# BuckConverters.net
KiCad netlist of a schematic drawn in Altium Designer
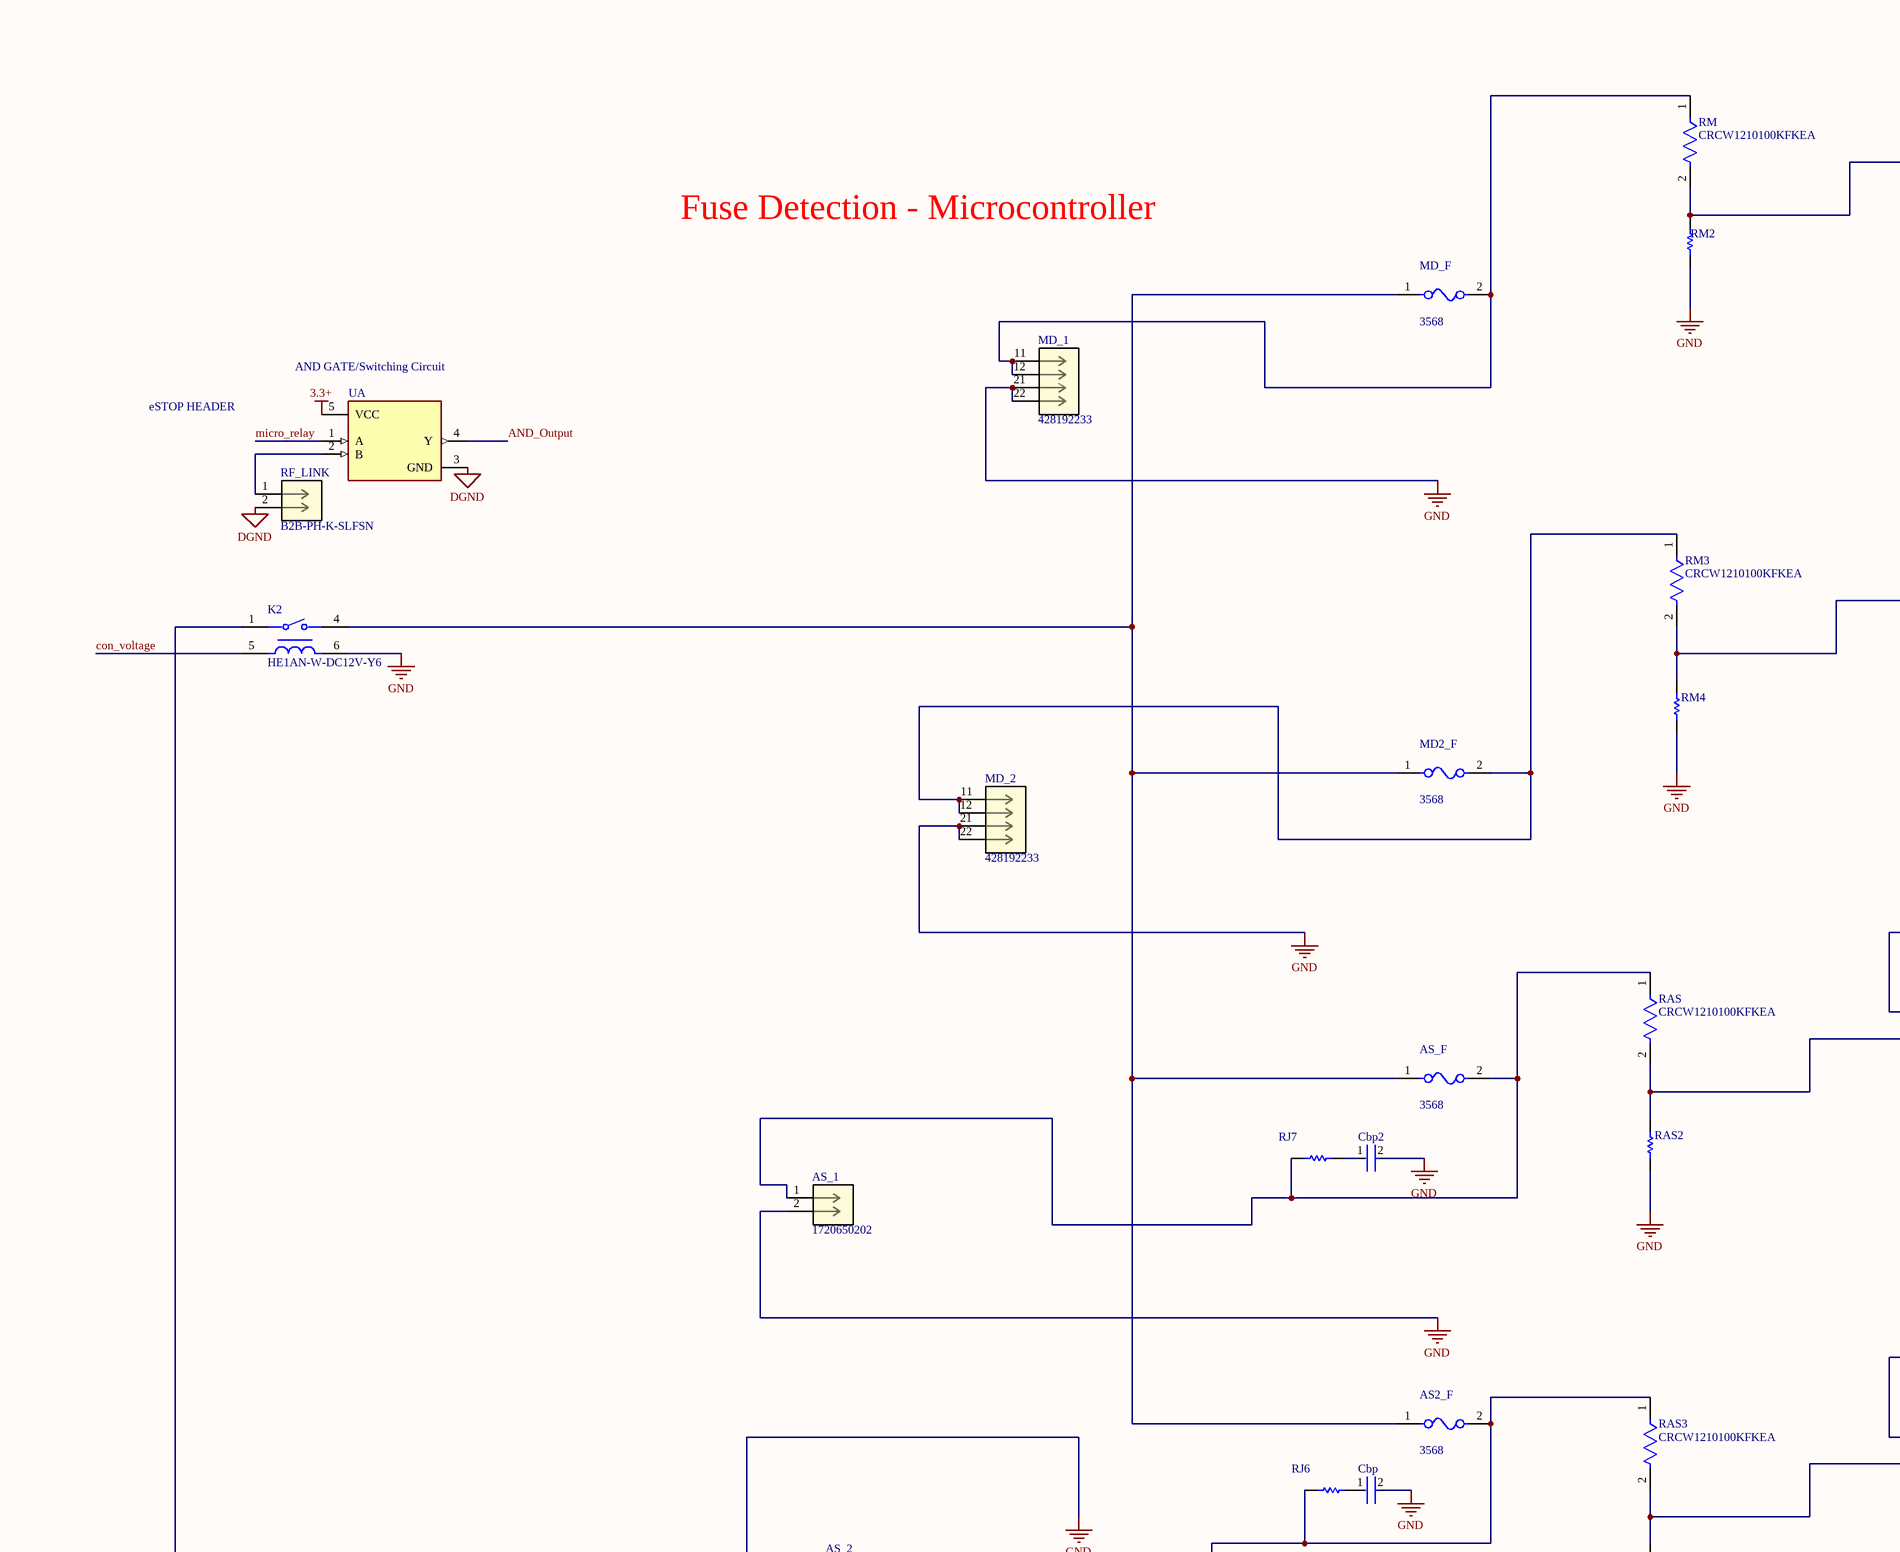
[diagram p0: BuckConverters.SchDoc, row 1 of 4 left]
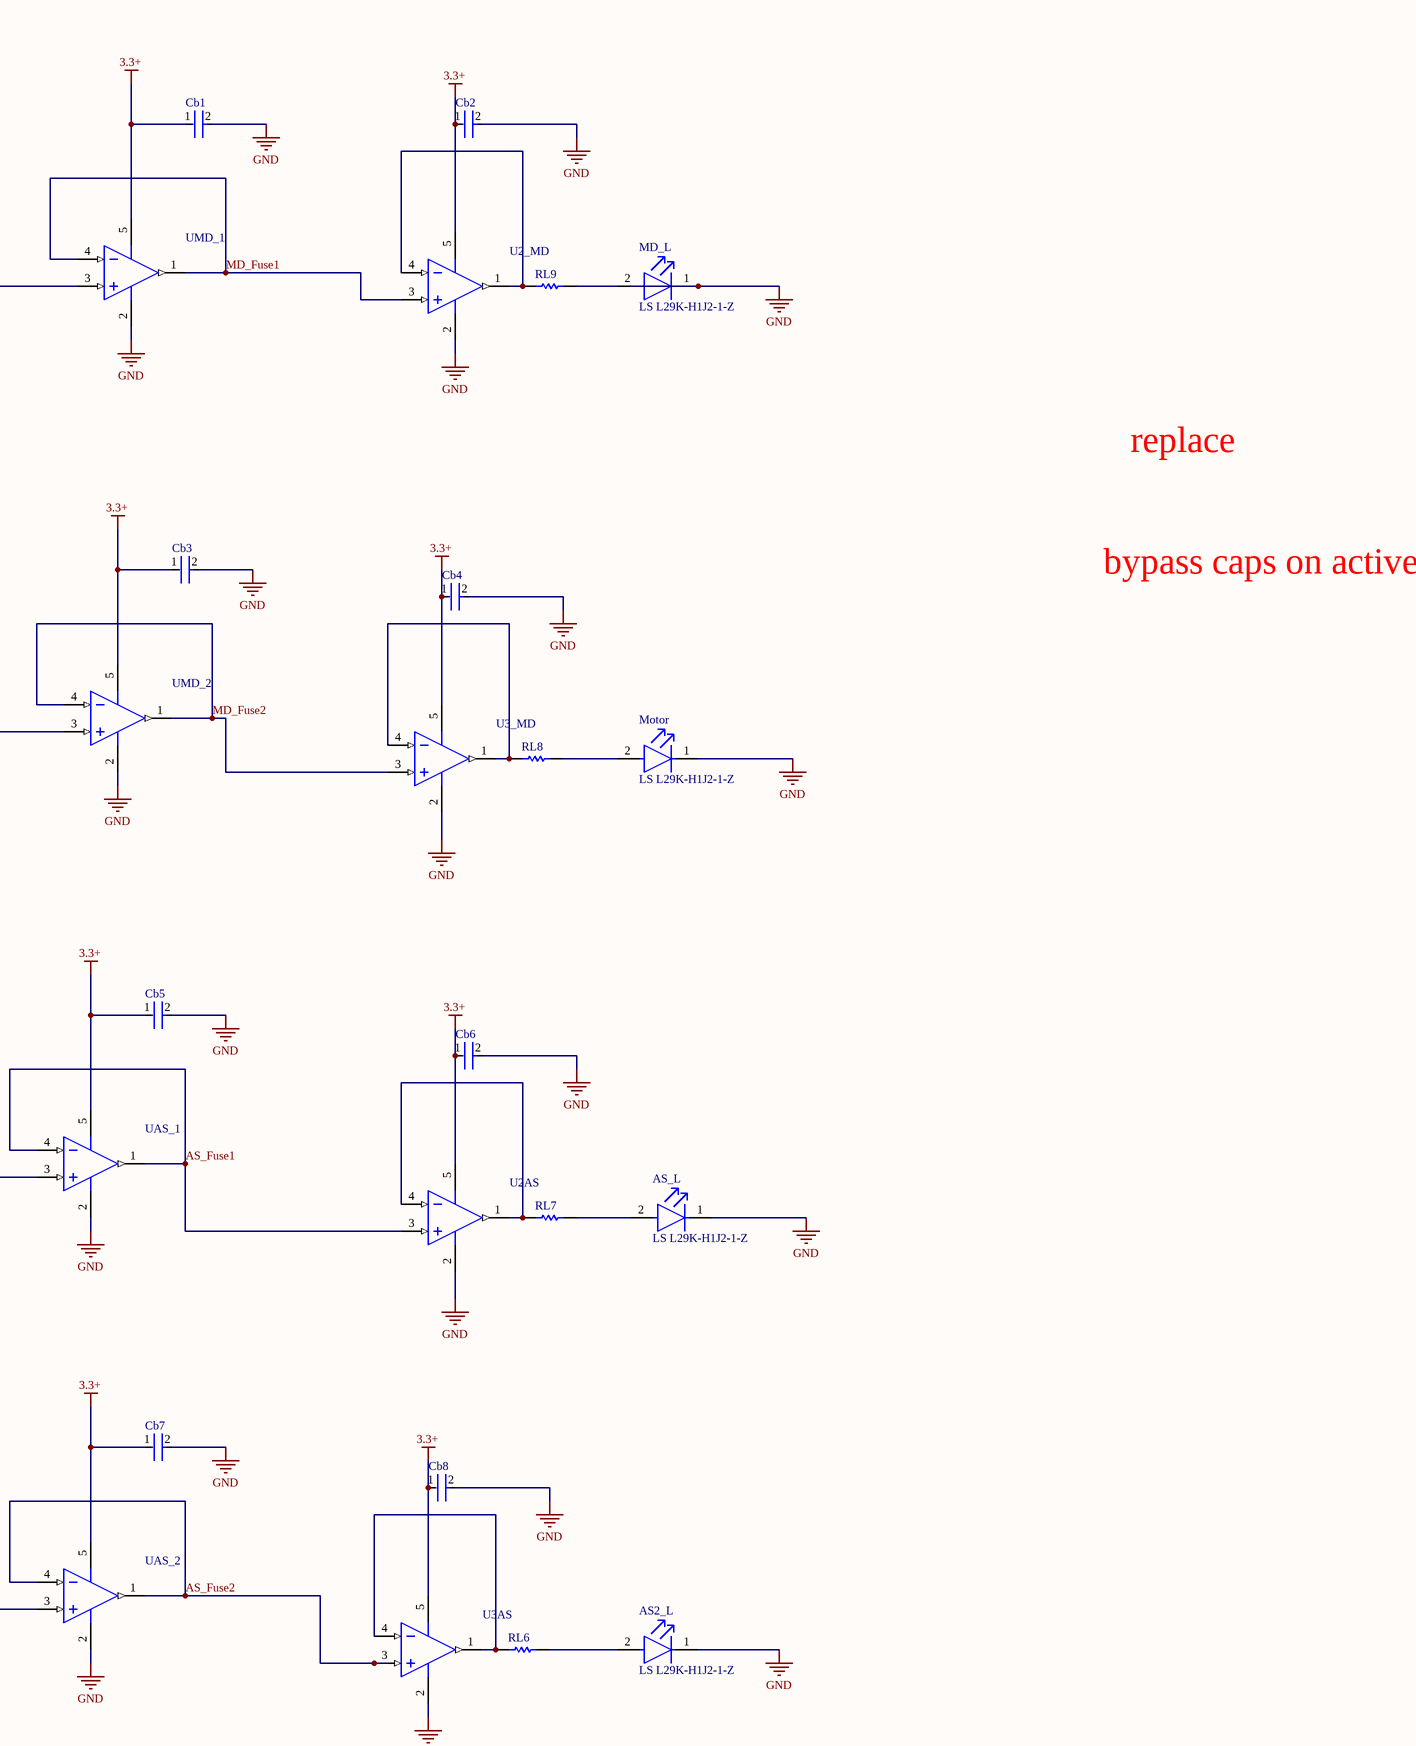
[diagram p1: BuckConverters.SchDoc, row 1 of 4 right]
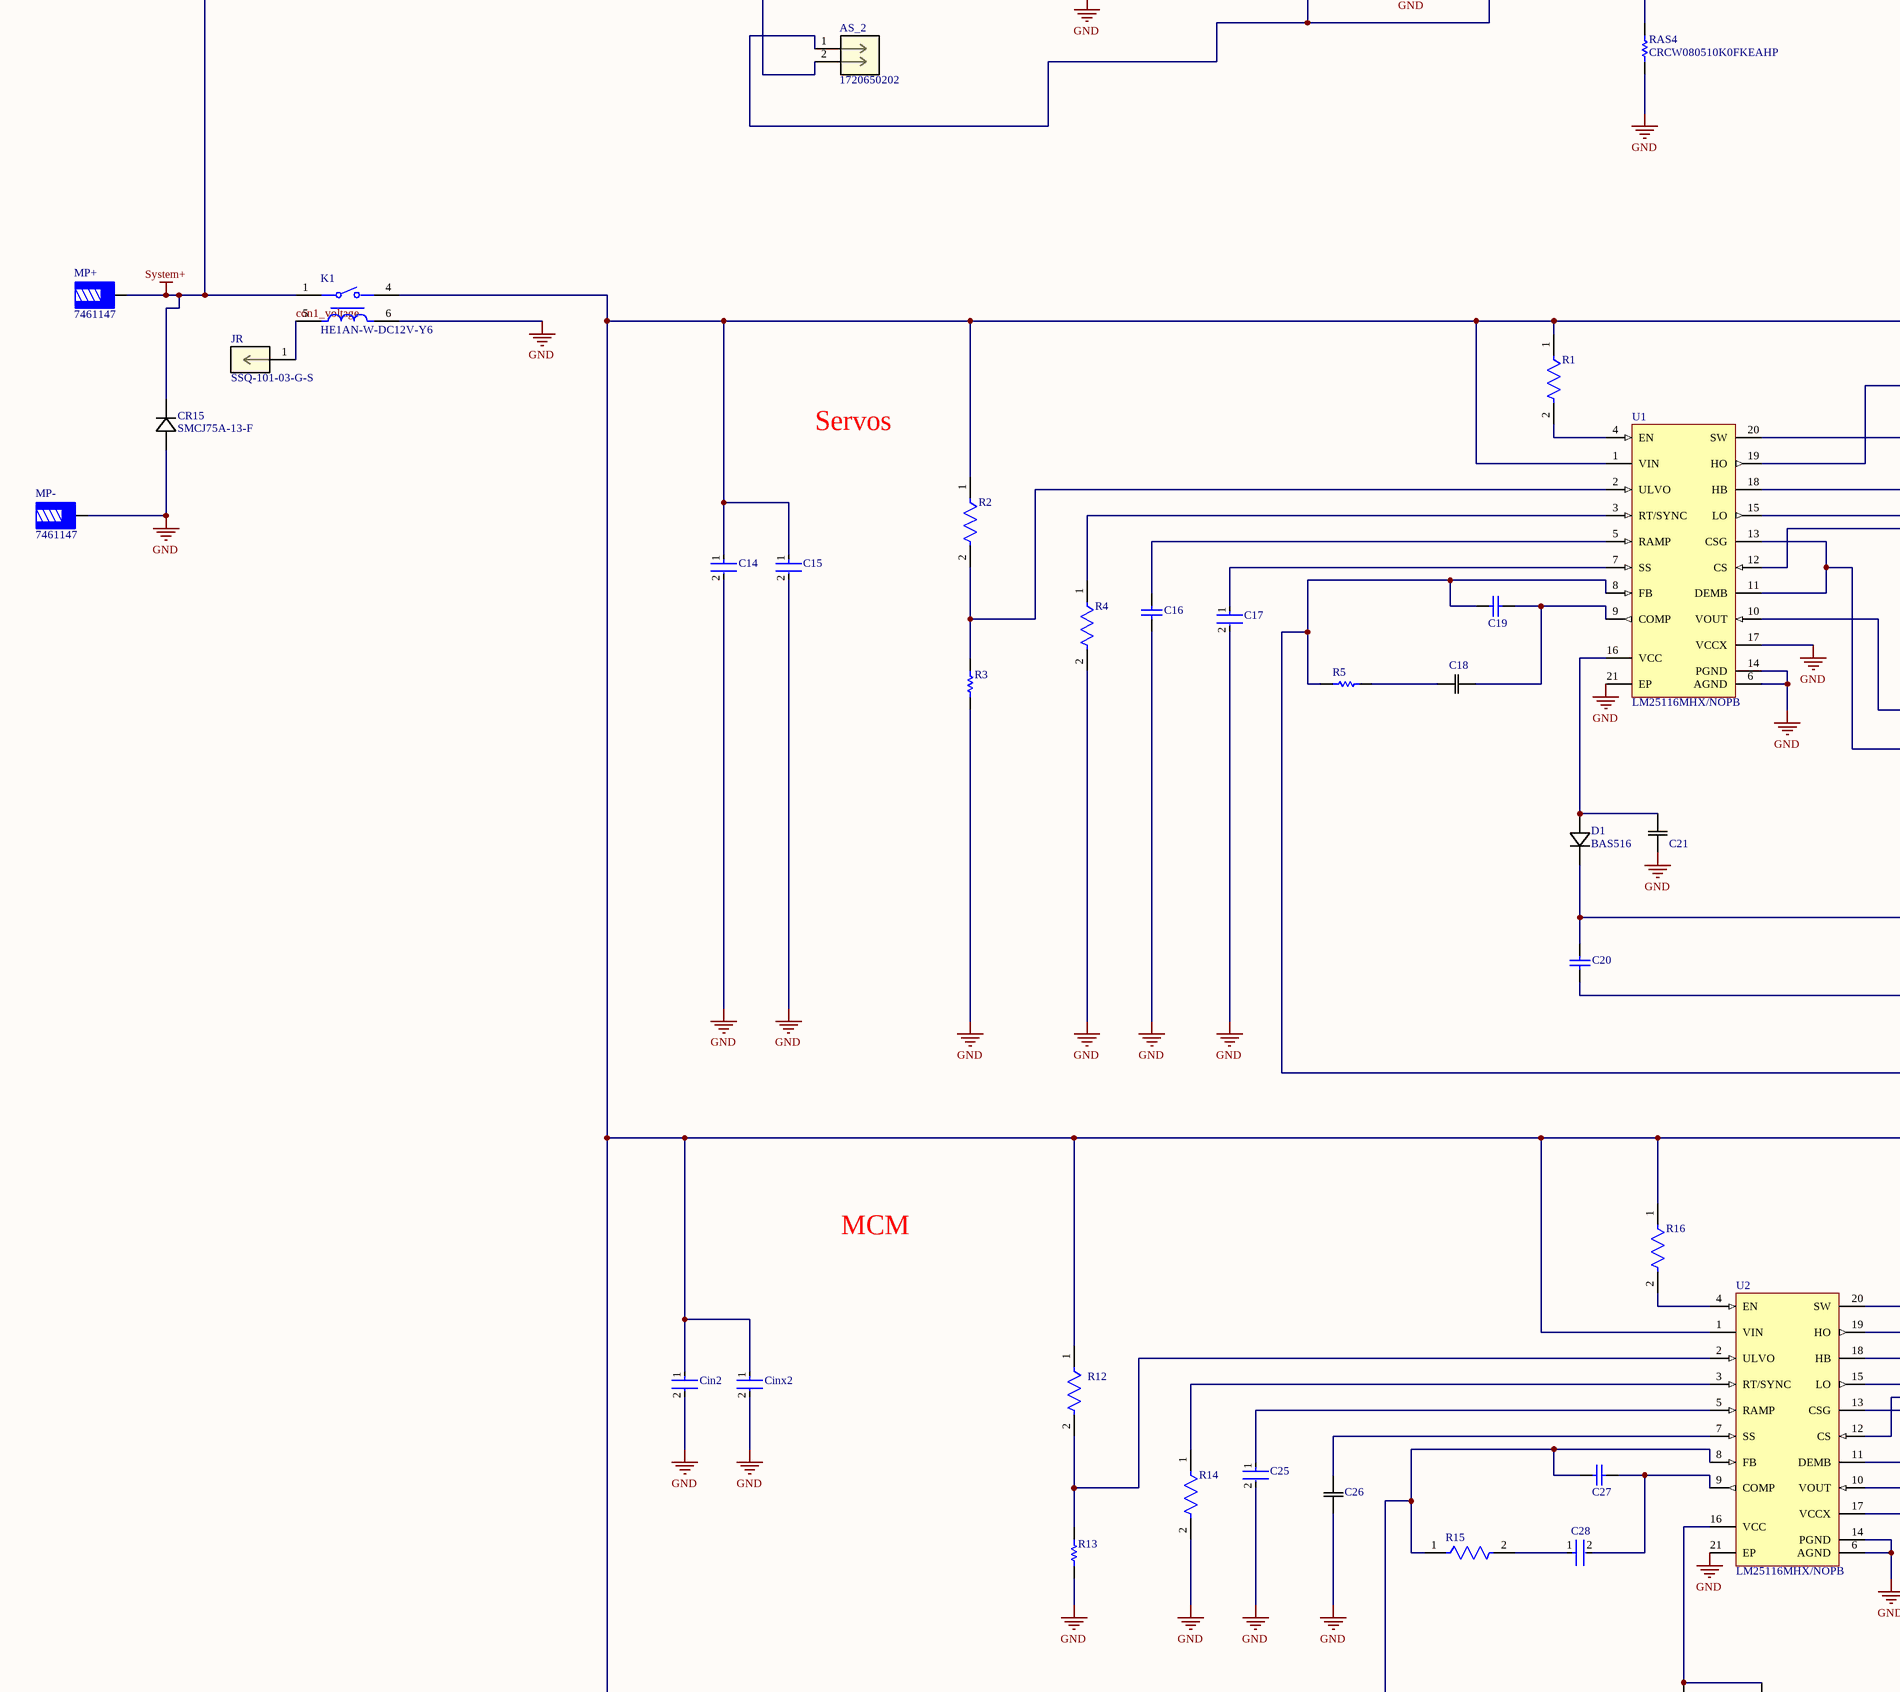
[diagram p2: BuckConverters.SchDoc, row 2 of 4 left]
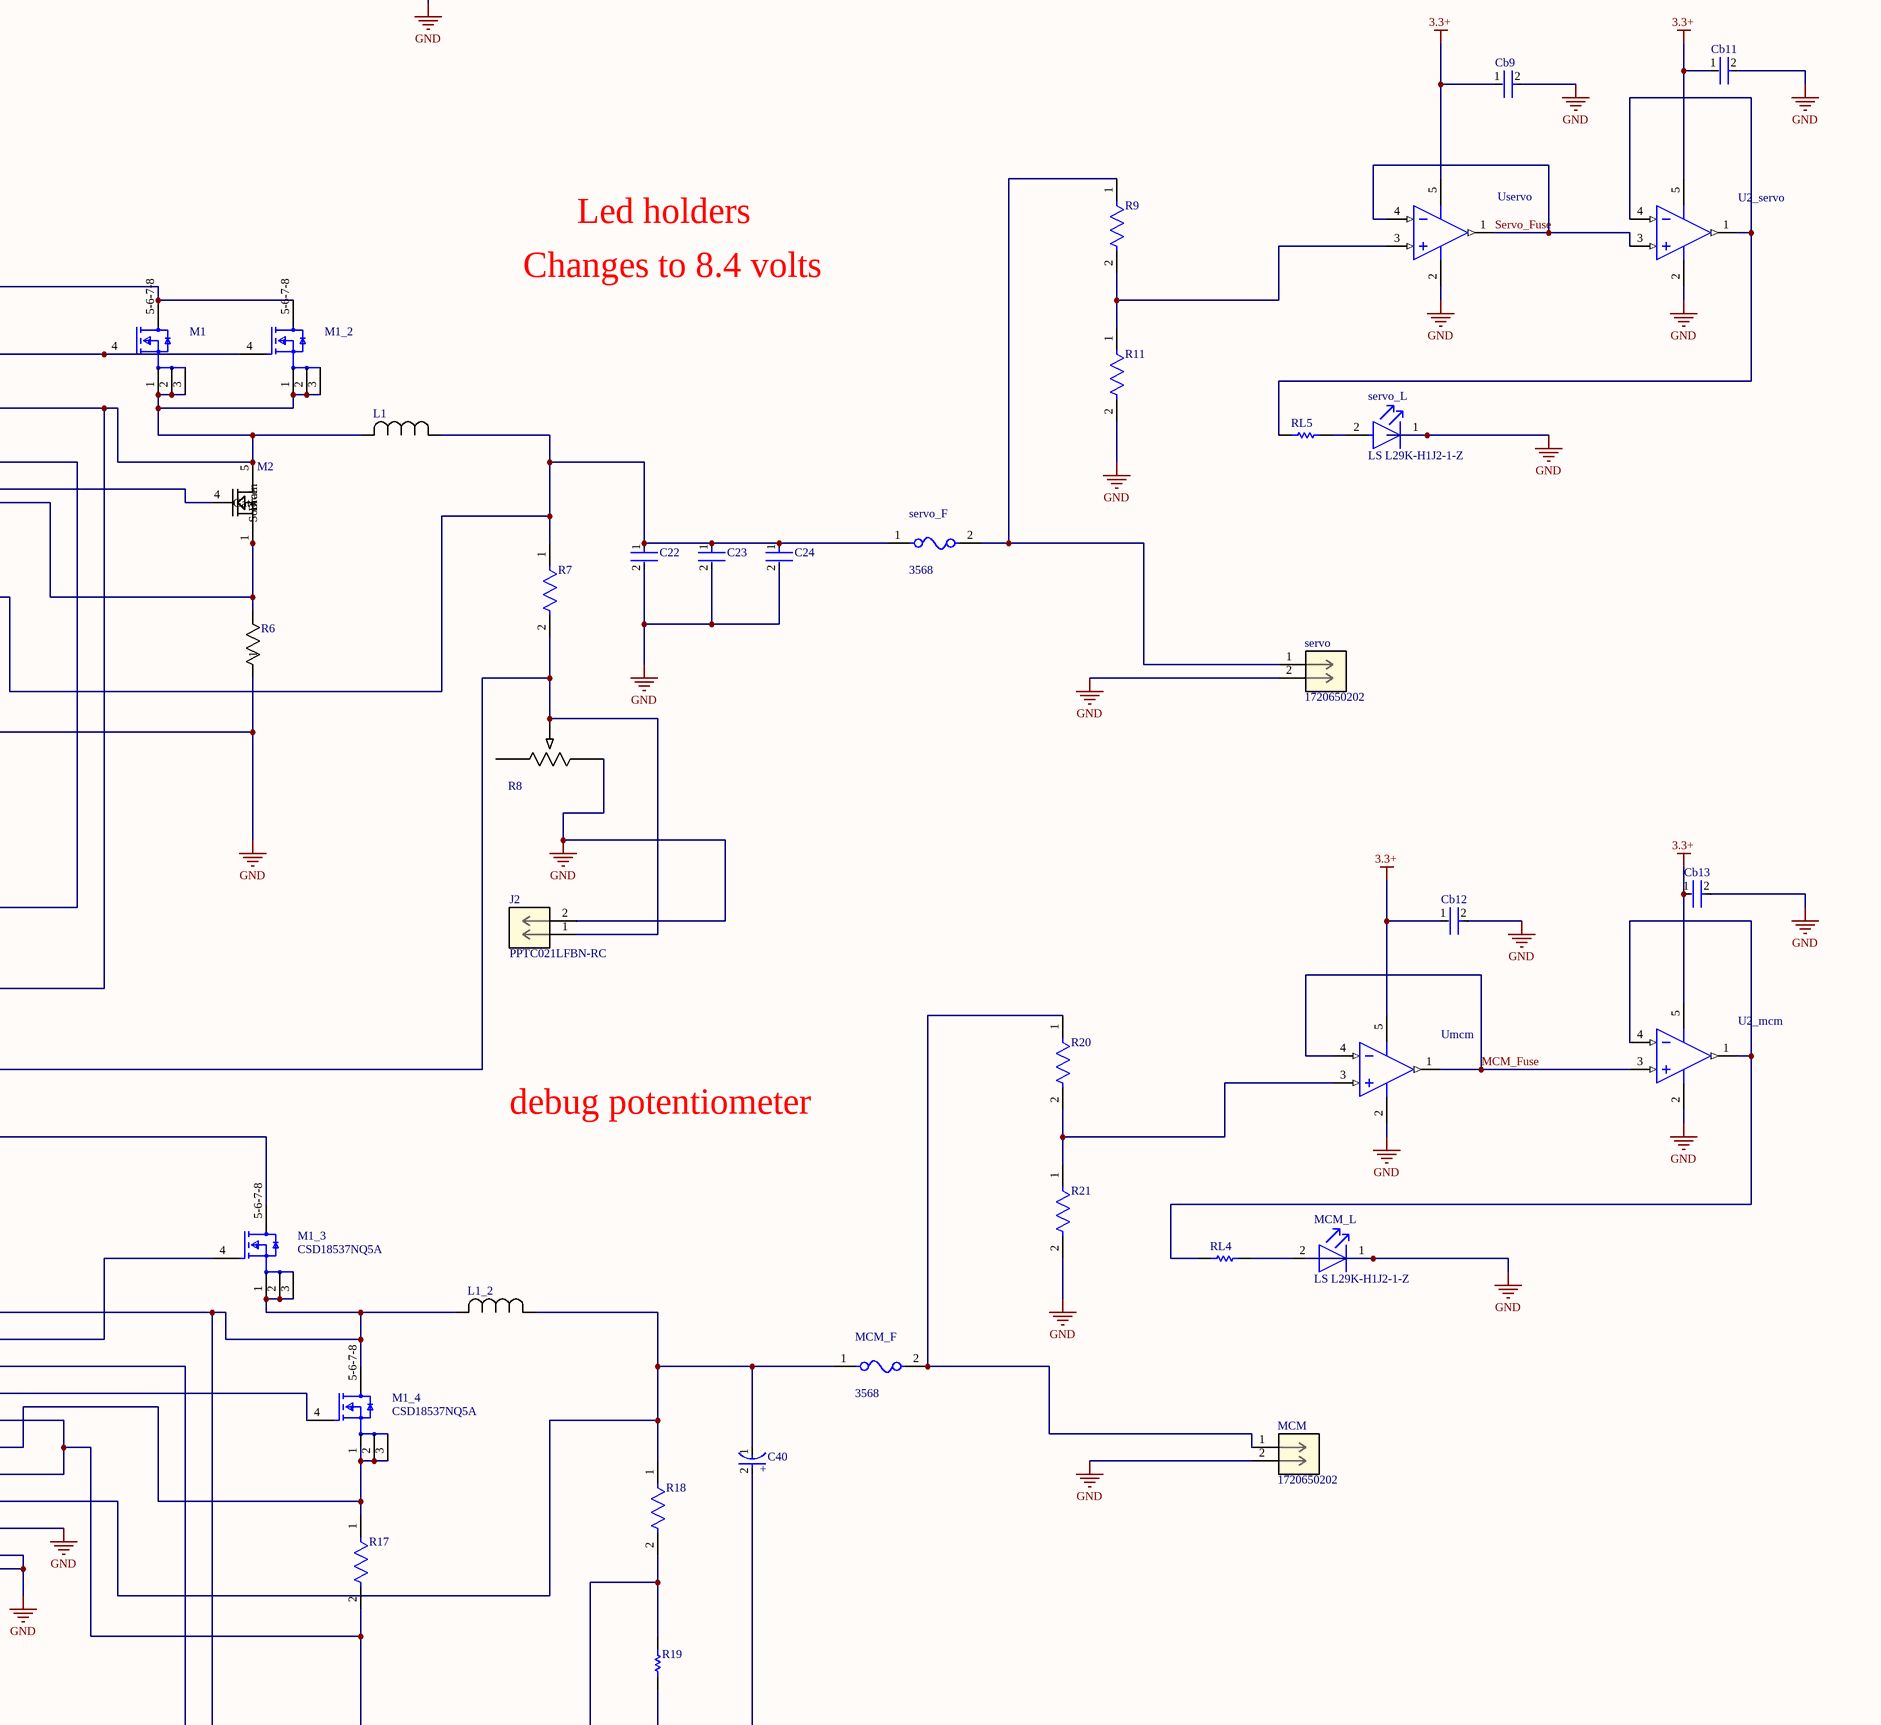
[diagram p3: BuckConverters.SchDoc, row 2 of 4 right]
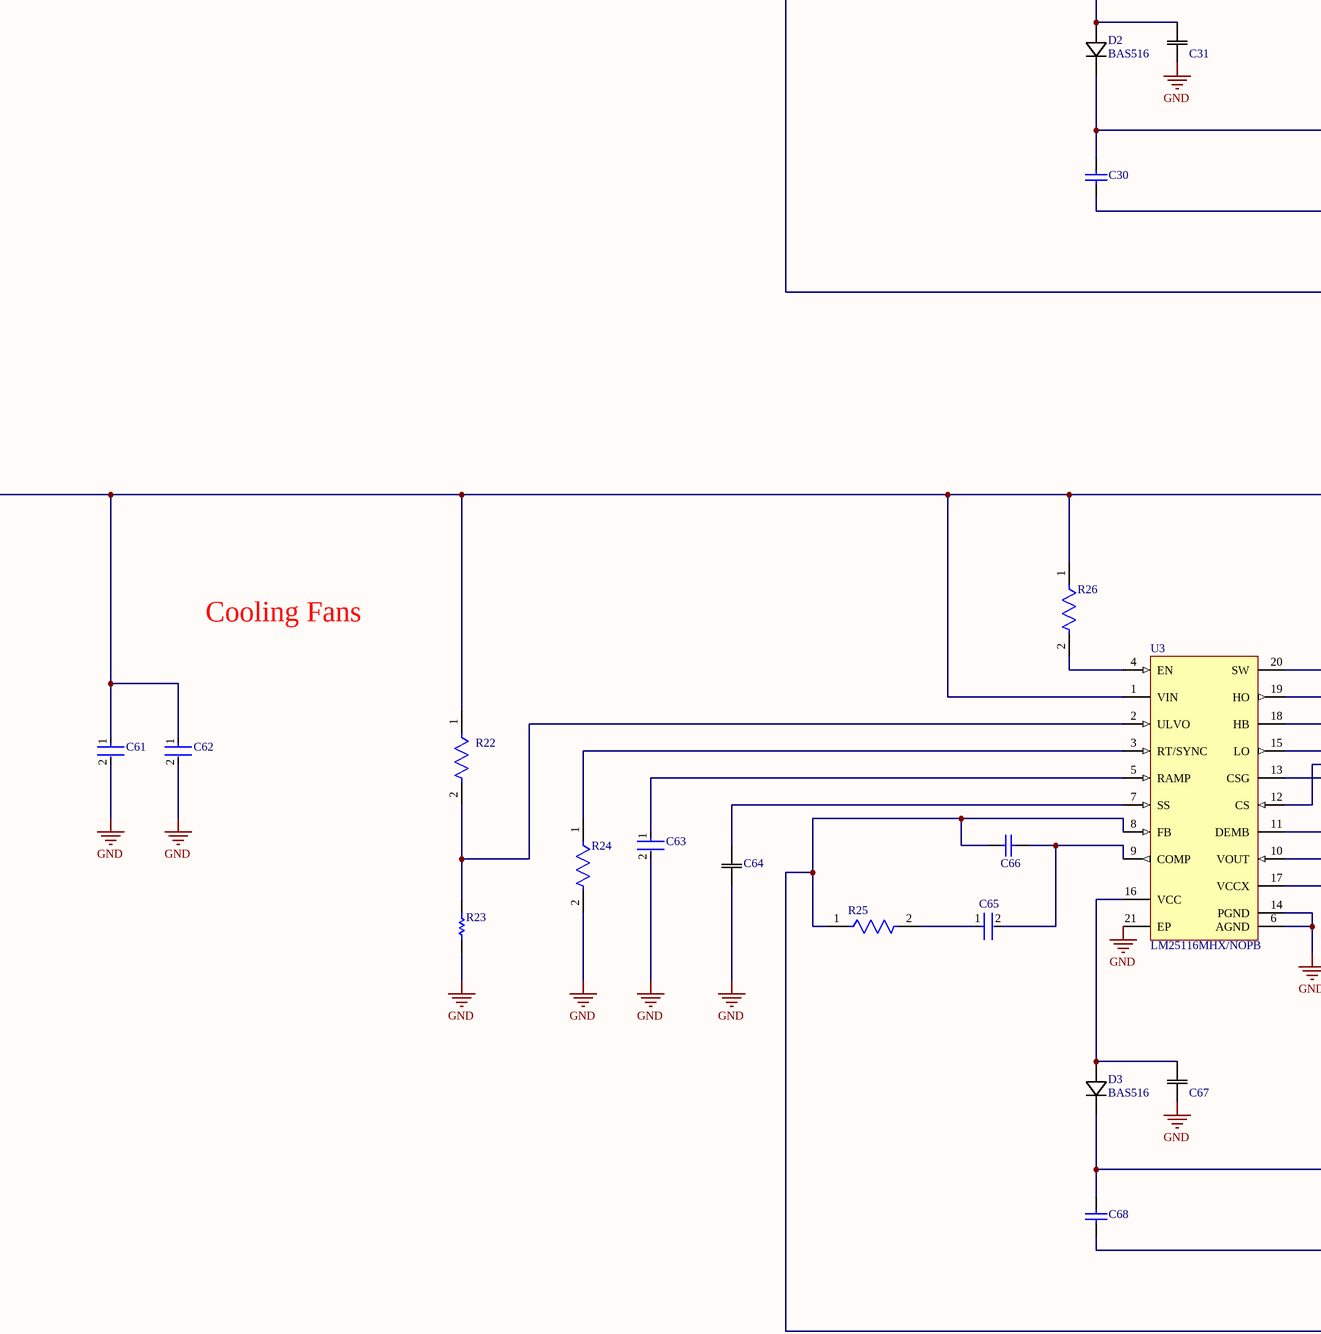
[diagram p4: BuckConverters.SchDoc, row 3 of 4 left]
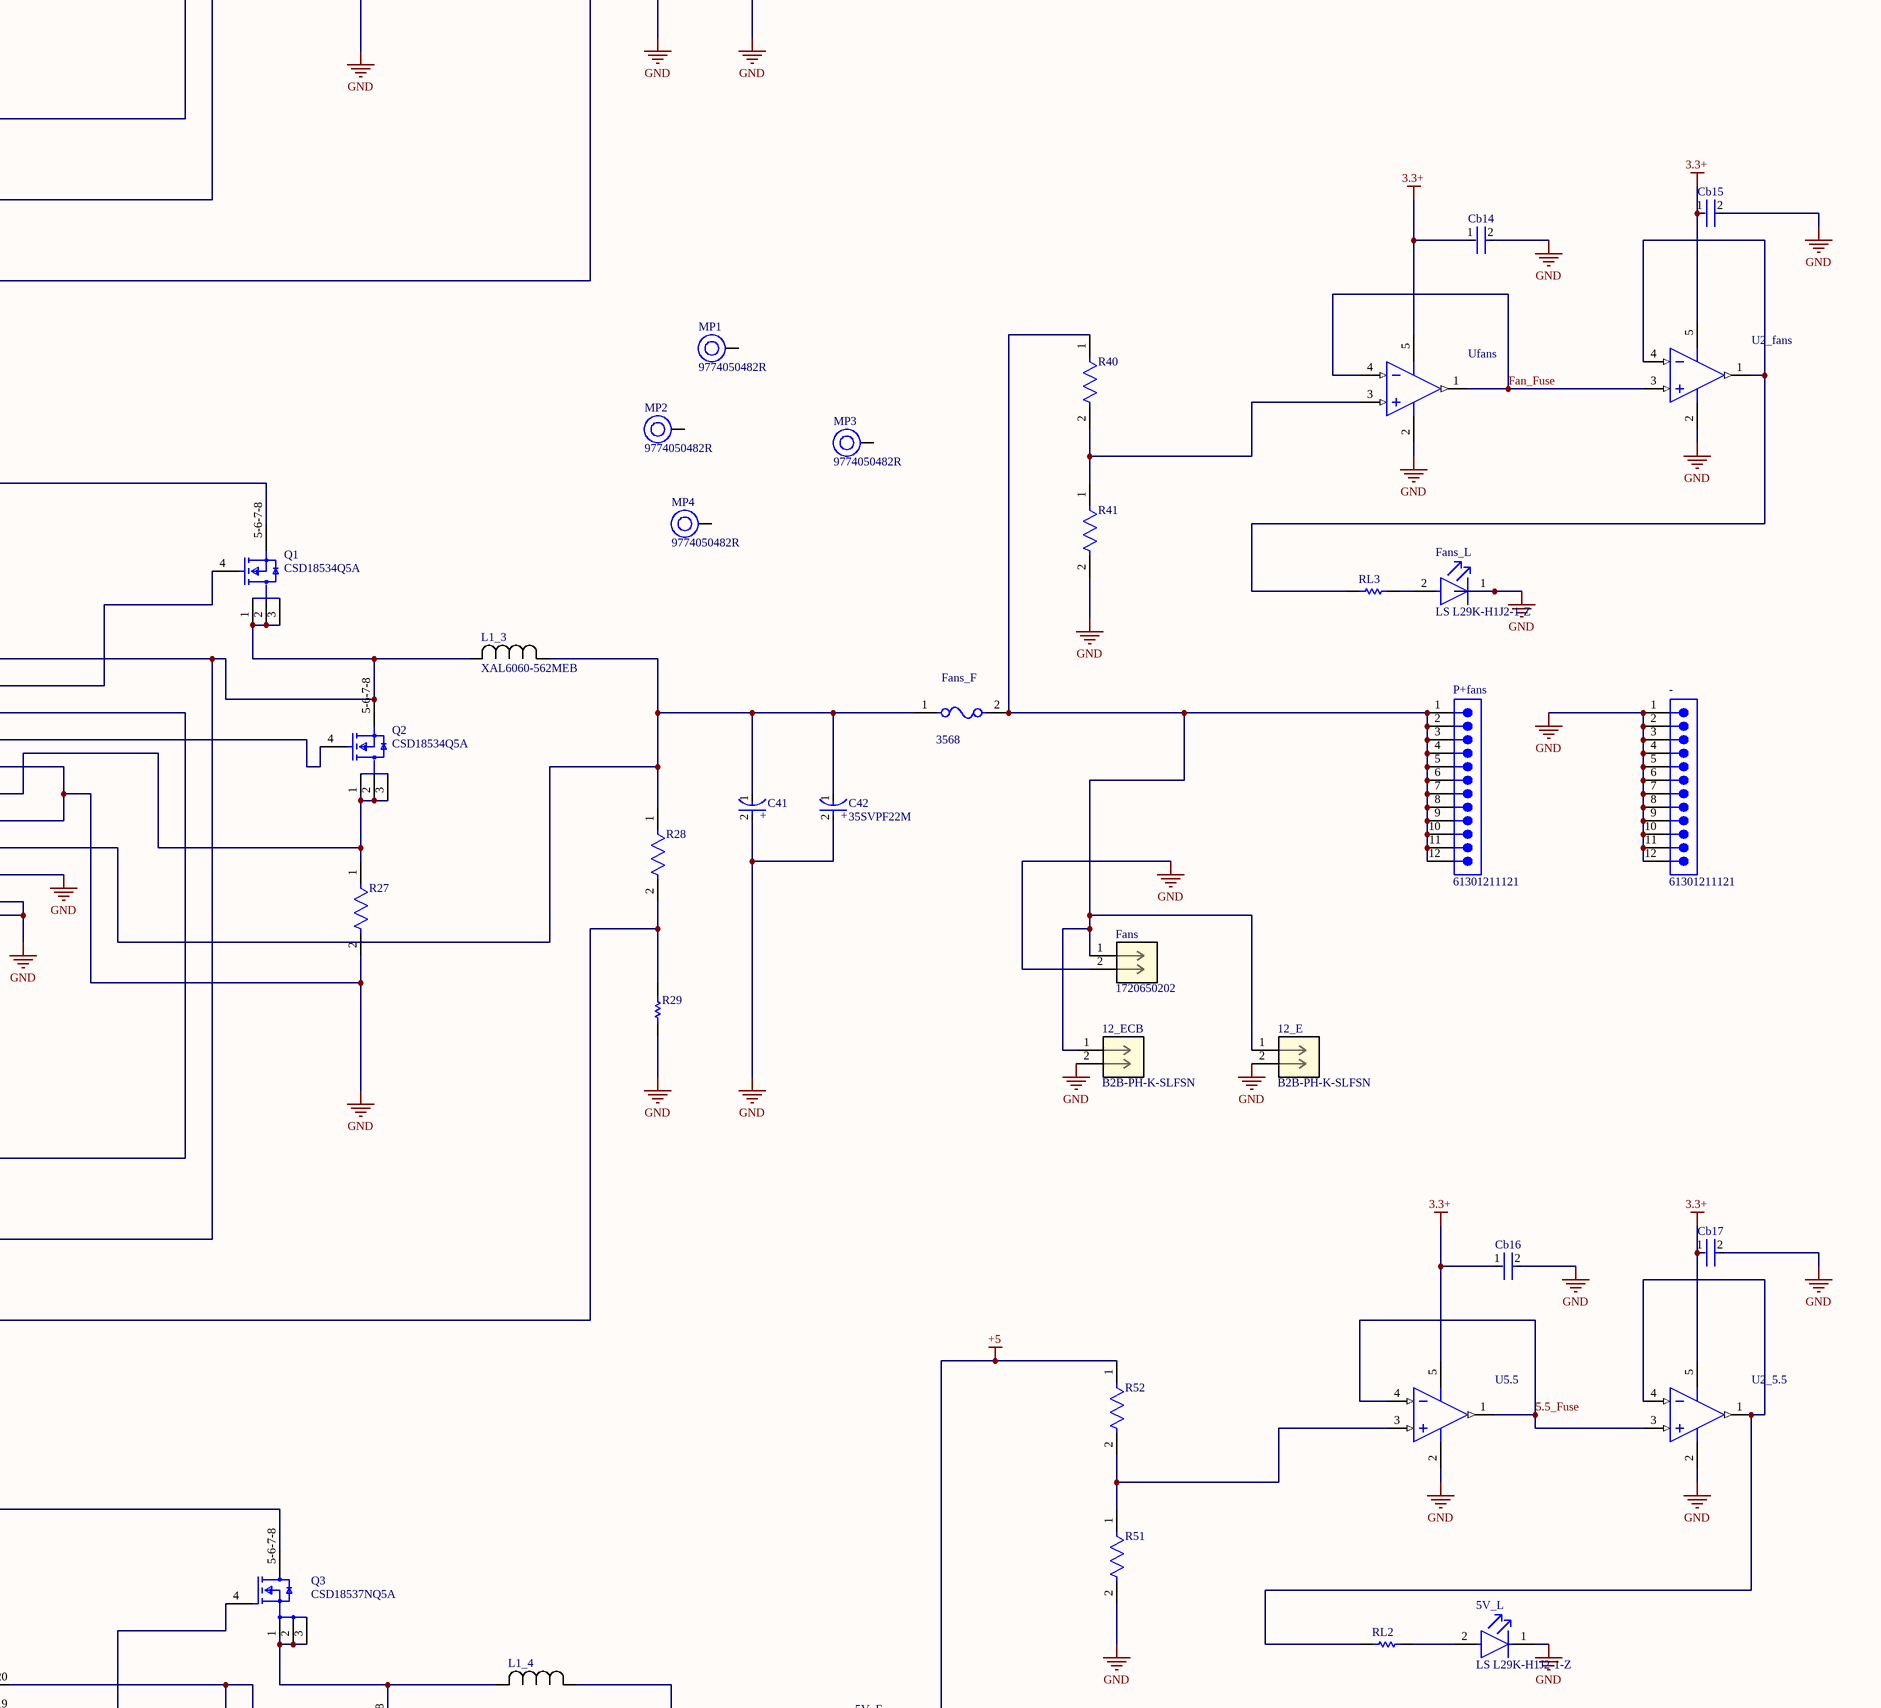
[diagram p5: BuckConverters.SchDoc, row 3 of 4 right]
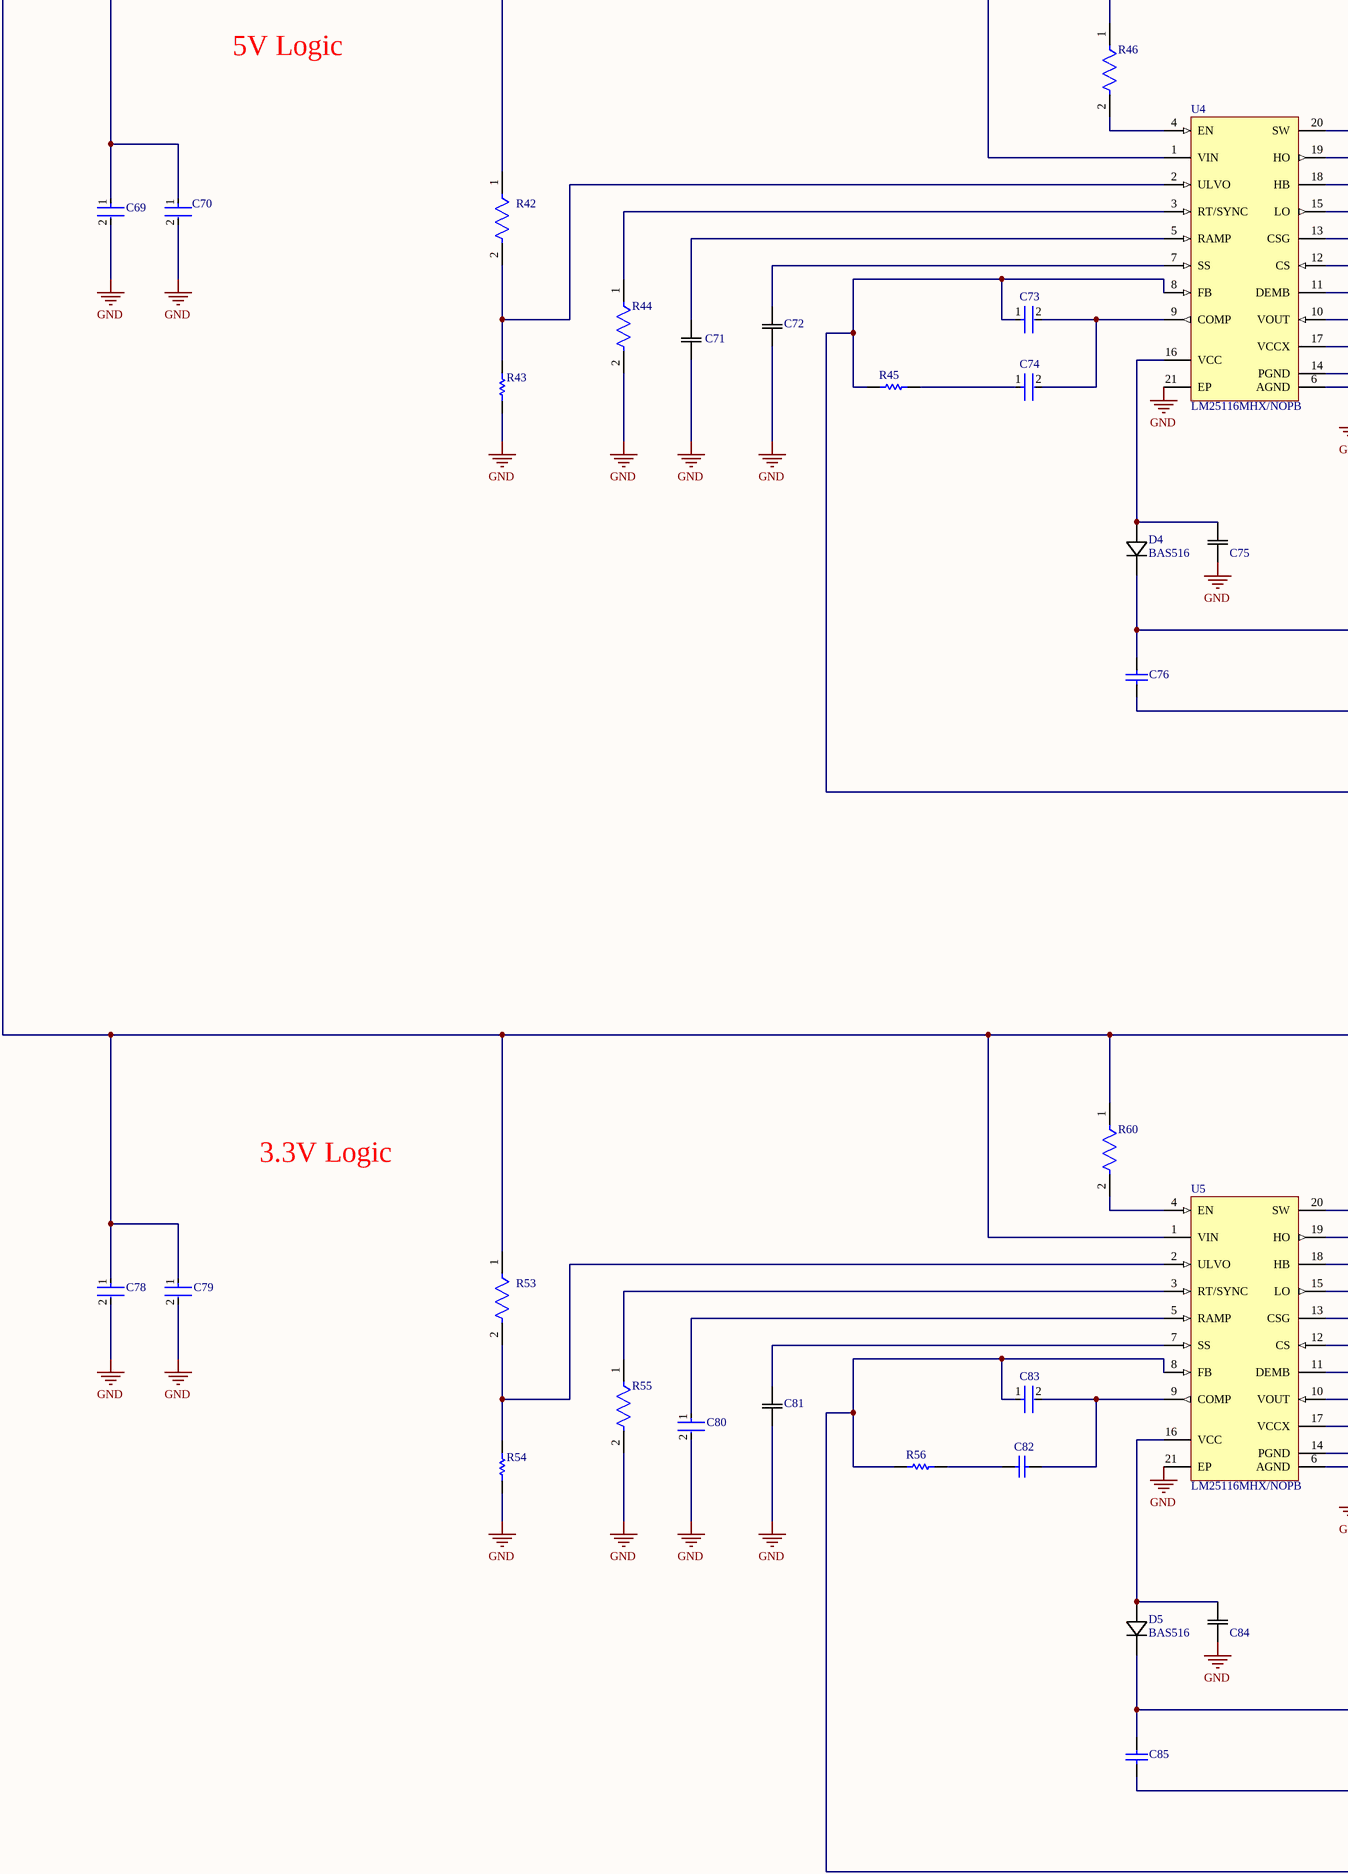
[diagram p6: BuckConverters.SchDoc, row 4 of 4 left]
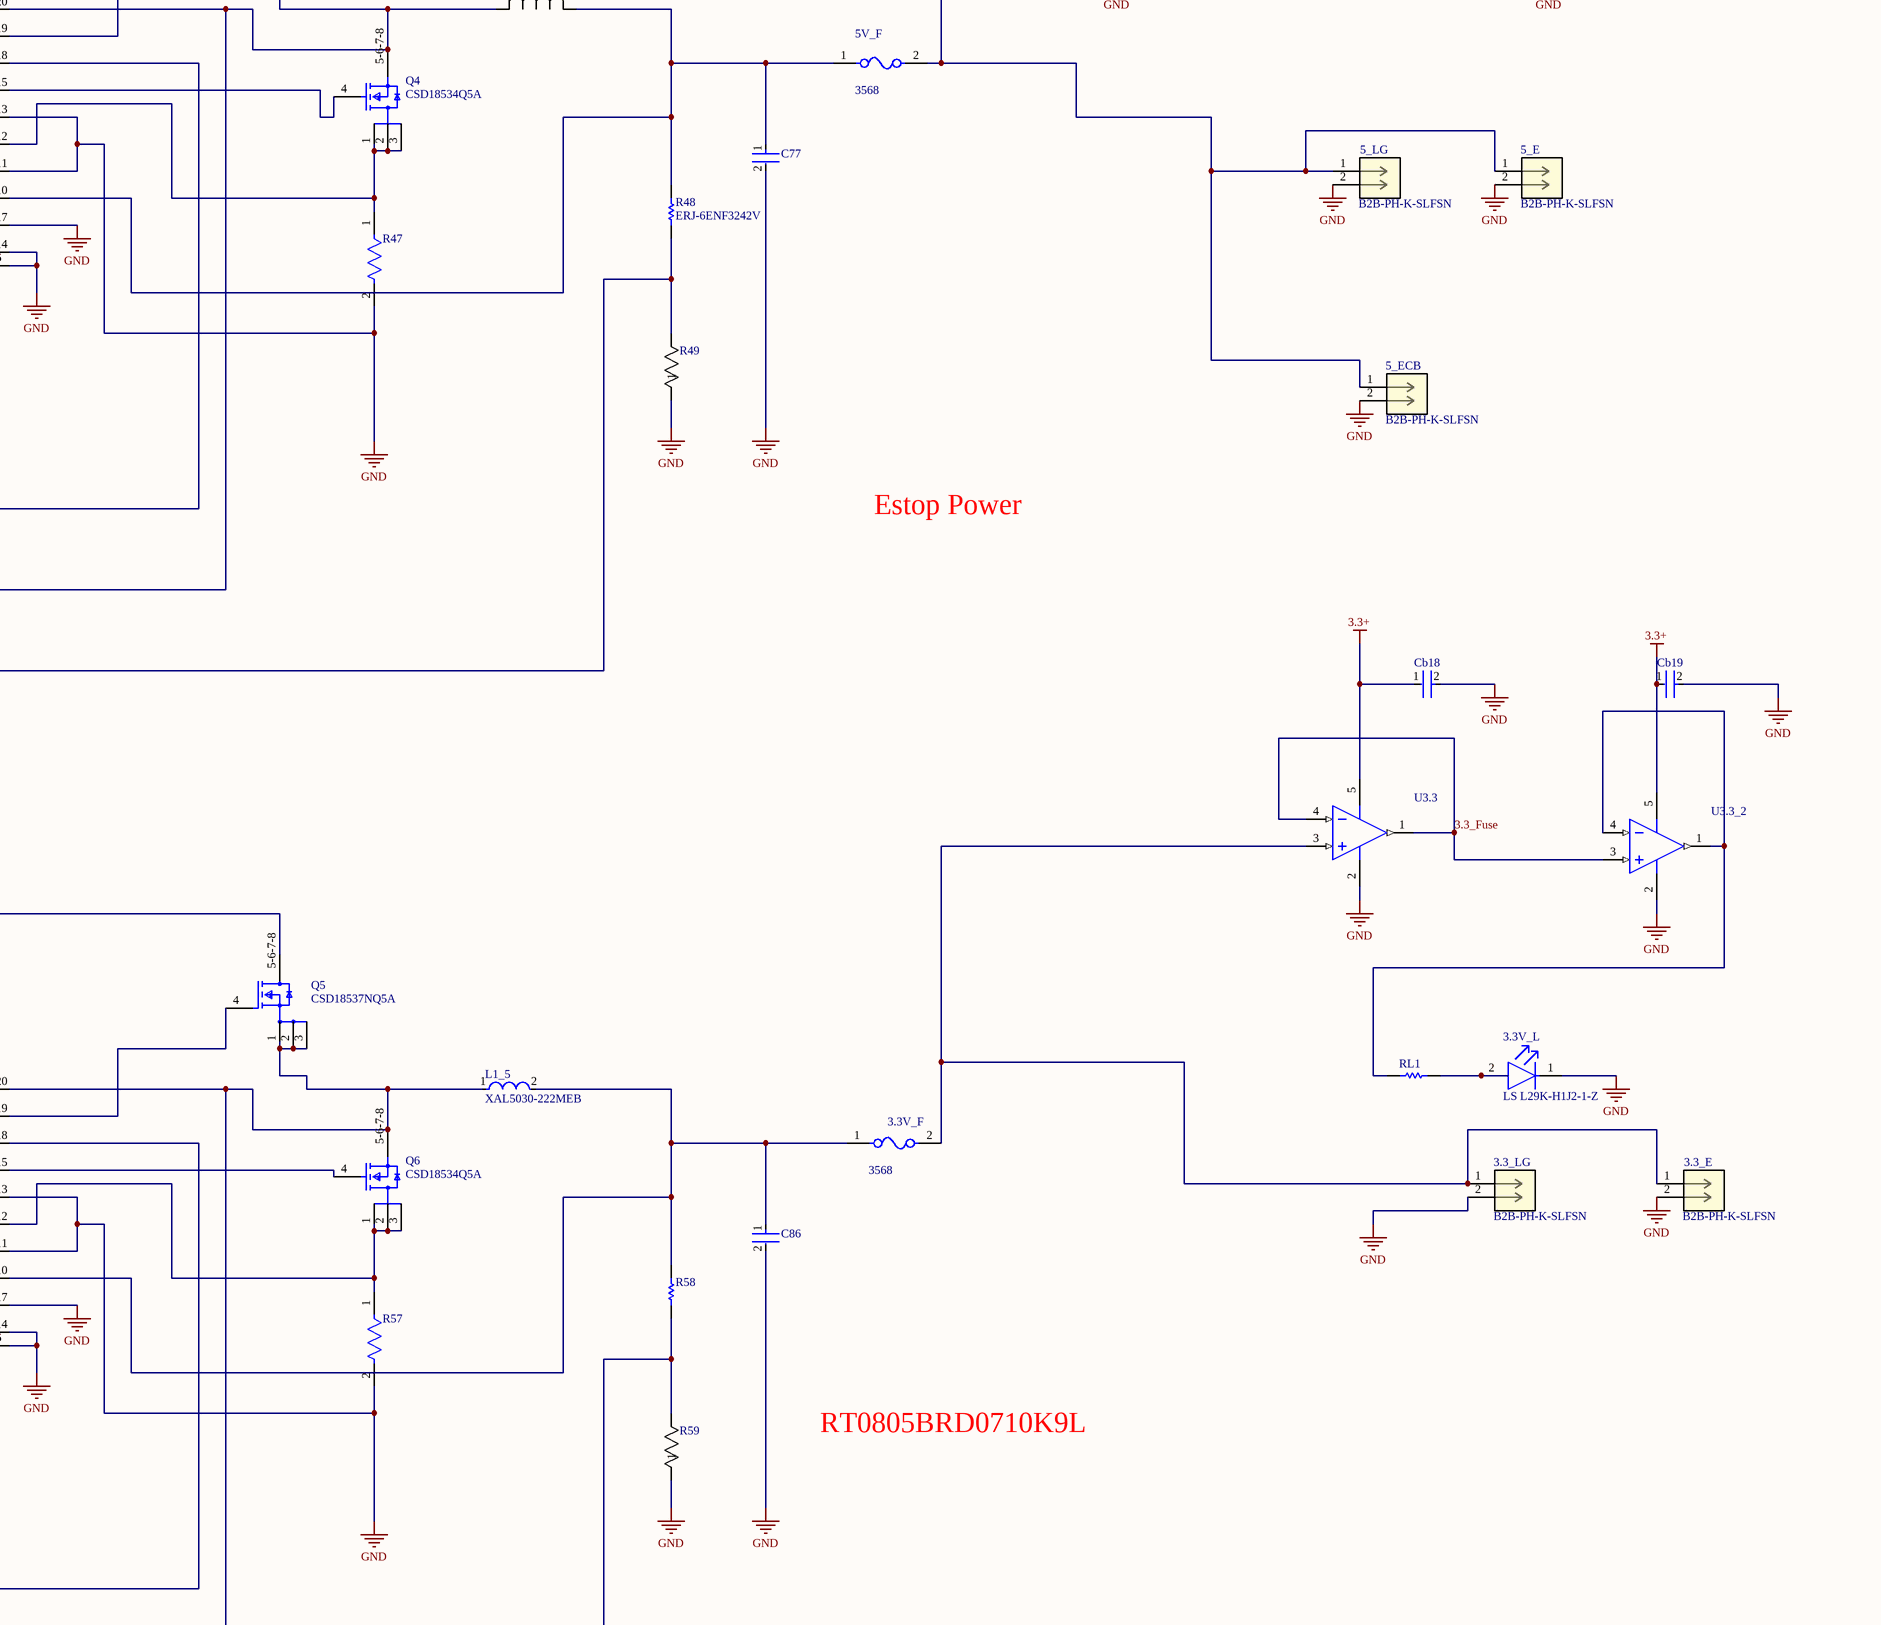
[diagram p7: BuckConverters.SchDoc, row 4 of 4 right]

(export (version "E")
  (design (tool "Eeschema 10.0.6"))
  (components
    (comp (ref "-")
      (value "61301211121")
      (footprint "61301211121")
      (libsource (lib "Altium Content Vault") (part "Header_Male_1R_12P"))
    )
    (comp (ref "3.3V_F")
      (value "3568")
      (footprint "FP-3568-MFG")
      (fields (field (name "VOLTAGE") "500V"))
      (libsource (lib "Altium Content Vault") (part "3568"))
    )
    (comp (ref "3.3V_L")
      (value "LS L29K-H1J2-1-Z")
      (footprint "FP-LS_L29K-MFG")
      (description "LED RED DIFFUSED 0603 SMD")
      (libsource (lib "Altium Content Vault") (part "8706943c75ba83719d021d2fdc84c58"))
    )
    (comp (ref "3.3_E")
      (value "B2B-PH-K-SLFSN")
      (footprint "CONN_B2B-PH-K-SLFSN_JST")
      (description "No Description Available")
      (libsource (lib "B2B-PH-K-SLFSN") (part "B2B-PH-K-SLFSN"))
    )
    (comp (ref "3.3_LG")
      (value "B2B-PH-K-SLFSN")
      (footprint "CONN_B2B-PH-K-SLFSN_JST")
      (description "No Description Available")
      (libsource (lib "B2B-PH-K-SLFSN") (part "B2B-PH-K-SLFSN"))
    )
    (comp (ref "5V_F")
      (value "3568")
      (footprint "FP-3568-MFG")
      (fields (field (name "VOLTAGE") "500V"))
      (libsource (lib "Altium Content Vault") (part "3568"))
    )
    (comp (ref "5V_L")
      (value "LS L29K-H1J2-1-Z")
      (footprint "FP-LS_L29K-MFG")
      (description "LED RED DIFFUSED 0603 SMD")
      (libsource (lib "Altium Content Vault") (part "8706943c75ba83719d021d2fdc84c58"))
    )
    (comp (ref "5_E")
      (value "B2B-PH-K-SLFSN")
      (footprint "CONN_B2B-PH-K-SLFSN_JST")
      (description "No Description Available")
      (libsource (lib "B2B-PH-K-SLFSN") (part "B2B-PH-K-SLFSN"))
    )
    (comp (ref "5_ECB")
      (value "B2B-PH-K-SLFSN")
      (footprint "CONN_B2B-PH-K-SLFSN_JST")
      (description "No Description Available")
      (libsource (lib "B2B-PH-K-SLFSN") (part "B2B-PH-K-SLFSN"))
    )
    (comp (ref "5_LG")
      (value "B2B-PH-K-SLFSN")
      (footprint "CONN_B2B-PH-K-SLFSN_JST")
      (description "No Description Available")
      (libsource (lib "B2B-PH-K-SLFSN") (part "B2B-PH-K-SLFSN"))
    )
    (comp (ref "12_E")
      (value "B2B-PH-K-SLFSN")
      (footprint "CONN_B2B-PH-K-SLFSN_JST")
      (description "No Description Available")
      (libsource (lib "B2B-PH-K-SLFSN") (part "B2B-PH-K-SLFSN"))
    )
    (comp (ref "12_ECB")
      (value "B2B-PH-K-SLFSN")
      (footprint "CONN_B2B-PH-K-SLFSN_JST")
      (description "No Description Available")
      (libsource (lib "B2B-PH-K-SLFSN") (part "B2B-PH-K-SLFSN"))
    )
    (comp (ref "AS2_F")
      (value "3568")
      (footprint "FP-3568-MFG")
      (fields (field (name "VOLTAGE") "500V"))
      (libsource (lib "Altium Content Vault") (part "3568"))
    )
    (comp (ref "AS2_L")
      (value "LS L29K-H1J2-1-Z")
      (footprint "FP-LS_L29K-MFG")
      (description "LED RED DIFFUSED 0603 SMD")
      (libsource (lib "Altium Content Vault") (part "8706943c75ba83719d021d2fdc84c58"))
    )
    (comp (ref "AS_1")
      (value "1720650202")
      (footprint "CONN_SD-768290002_02_MOL")
      (description "No Description Available")
      (libsource (lib "1720650202") (part "1720650202"))
    )
    (comp (ref "AS_2")
      (value "1720650202")
      (footprint "CONN_SD-768290002_02_MOL")
      (description "No Description Available")
      (libsource (lib "1720650202") (part "1720650202"))
    )
    (comp (ref "AS_F")
      (value "3568")
      (footprint "FP-3568-MFG")
      (fields (field (name "VOLTAGE") "500V"))
      (libsource (lib "Altium Content Vault") (part "3568"))
    )
    (comp (ref "AS_L")
      (value "LS L29K-H1J2-1-Z")
      (footprint "FP-LS_L29K-MFG")
      (description "LED RED DIFFUSED 0603 SMD")
      (libsource (lib "Altium Content Vault") (part "8706943c75ba83719d021d2fdc84c58"))
    )
    (comp (ref "C14")
      (value "GRM31CR71H475KA12L")
      (footprint "FP-GRM31C-0_2-e0_3_0_8-IPC_C")
      (description "Chip Multilayer Ceramic Capacitors for General Purpose, 1206, 4.7uF, X7R, 15%, 10%, 50V")
      (fields (field (name "VOLTAGE") "50V") (field (name "TOLERANCE") "10%"))
      (libsource (lib "Altium Content Vault") (part "02cd4be3c70576c341d710602a673aa"))
    )
    (comp (ref "C15")
      (value "C0805C104M5RACTU")
      (footprint "FP-C0805C-DN-MFG")
      (description "CAP CER 0.1UF 50V X7R 0805")
      (fields
        (field (name "TOLERANCE") "0.2")
        (field (name "OCTOPART") "https://octopart.com/c0805c104m5ractu-kemet-129379")
      )
      (libsource (lib "Altium Content Vault") (part "b4654b650e69147ec39a6b967a45e02"))
    )
    (comp (ref "C16")
      (value "GRM1555C1H301GA01D")
      (footprint "CAPC1005X55X25LL05T10")
      (fields (field (name "MANUFACTURER") "Murata"))
      (libsource (lib "Altium Content Vault") (part "CAP"))
    )
    (comp (ref "C17")
      (value "C1206C333J1GACTU")
      (footprint "FP-C1206C-EB-MFG")
      (description "C1206 33,000 pF C0G 5.00% 100 V")
      (fields
        (field (name "OCTOPART") "https://octopart.com/c1206c333j1gactu-kemet-47053096")
        (field (name "TOLERANCE") "0.05")
      )
      (libsource (lib "Altium Content Vault") (part "b4654b650e69147ec39a6b967a45e02"))
    )
    (comp (ref "C18")
      (value "UMK105CG181JV-F")
      (footprint "PcbLib1:cap_UMK105 CG080CV-F_TAY")
      (description "No Description Available")
      (libsource (lib "UMK105CG181JV-F") (part "UMK105CG181JV-F"))
    )
    (comp (ref "C19")
      (value "GRM1555C1E5R1CA01D")
      (footprint "CAPC1005X55X25LL05T10")
      (fields (field (name "MANUFACTURER") "Murata"))
      (libsource (lib "Altium Content Vault") (part "CAP"))
    )
    (comp (ref "C20")
      (value "08053C104K4T2A")
      (footprint "CAPC2013X140X50LL20T25")
      (fields (field (name "MANUFACTURER") "AVX Interconnect / Elco"))
      (libsource (lib "Altium Content Vault") (part "CAP"))
    )
    (comp (ref "C21")
      (value "TMK212BJ105KG-T")
      (footprint "CAP_TMK212BJ105KG-T_TAY")
      (description "No Description Available")
      (libsource (lib "TMK212BJ105KG-T") (part "TMK212BJ105KG-T"))
    )
    (comp (ref "C22")
      (value "CGA9N3X7R1C476M230KB")
      (footprint "FP-CGA9P-IPC_A")
      (description "Cap Ceramic 47uF 16V X7R 20% Pad SMD 2220 +125°C Automotive T/R")
      (fields (field (name "TOLERANCE") "20%"))
      (libsource (lib "Altium Content Vault") (part "b4654b650e69147ec39a6b967a45e02"))
    )
    (comp (ref "C23")
      (value "CGA9N3X7R1C476M230KB")
      (footprint "FP-CGA9P-IPC_A")
      (description "Cap Ceramic 47uF 16V X7R 20% Pad SMD 2220 +125°C Automotive T/R")
      (fields (field (name "TOLERANCE") "20%"))
      (libsource (lib "Altium Content Vault") (part "b4654b650e69147ec39a6b967a45e02"))
    )
    (comp (ref "C24")
      (value "CGA9N3X7R1C476M230KB")
      (footprint "FP-CGA9P-IPC_A")
      (description "Cap Ceramic 47uF 16V X7R 20% Pad SMD 2220 +125°C Automotive T/R")
      (fields (field (name "TOLERANCE") "20%"))
      (libsource (lib "Altium Content Vault") (part "b4654b650e69147ec39a6b967a45e02"))
    )
    (comp (ref "C25")
      (value "UMK105CG271JV-F")
      (footprint "FP-0402-L_1_0_0_05-W_0_5-IPC_B")
      (description "None")
      (fields (field (name "TOLERANCE") "5%"))
      (libsource (lib "Altium Content Vault") (part "b4654b650e69147ec39a6b967a45e02"))
    )
    (comp (ref "C26")
      (value "CGA4J2C0G1H333J125AA")
      (footprint "CAP_2012_TDK-M")
      (description "No Description Available")
      (libsource (lib "CGA4J2C0G1H333J125AA") (part "CGA4J2C0G1H333J125AA"))
    )
    (comp (ref "C27")
      (value "GRM1555C1E5R1CA01D")
      (footprint "CAPC1005X55X25LL05T10")
      (fields (field (name "MANUFACTURER") "Murata"))
      (libsource (lib "Altium Content Vault") (part "CAP"))
    )
    (comp (ref "C28")
      (value "GRM1555C1H101FA01D")
      (footprint "FP-GRM155-0_05-IPC_C")
      (description "CAP CER 100PF 50V C0G/NP0 0402")
      (fields (field (name "VOLTAGE") "50V") (field (name "TOLERANCE") "1%"))
      (libsource (lib "Altium Content Vault") (part "b4654b650e69147ec39a6b967a45e02"))
    )
    (comp (ref "C30")
      (value "08053C104K4T2A")
      (footprint "CAPC2013X140X50LL20T25")
      (fields (field (name "MANUFACTURER") "AVX Interconnect / Elco"))
      (libsource (lib "Altium Content Vault") (part "CAP"))
    )
    (comp (ref "C31")
      (value "TMK212BJ105KG-T")
      (footprint "CAP_TMK212BJ105KG-T_TAY")
      (description "No Description Available")
      (libsource (lib "TMK212BJ105KG-T") (part "TMK212BJ105KG-T"))
    )
    (comp (ref "C40")
      (value "25SVPF27MX")
      (footprint "FP-OS-CON-SMT-B6-MFG")
      (description "Conductive Polymer Aluminum Solid Capacitors (OS-CON) 27uF ±20% 25V")
      (fields (field (name "VOLTAGE") "25V") (field (name "TOLERANCE") "20%"))
      (libsource (lib "Altium Content Vault") (part "a00bbbee19879c290e62620ae7e47b1"))
    )
    (comp (ref "C41")
      (value "35SVPF22M")
      (footprint "FP-OS-CON-SMT-C6-MFG")
      (description "Conductive Polymer Aluminum Solid Capacitors (OS-CON) 22uF ±20% 35V")
      (fields (field (name "TOLERANCE") "20%") (field (name "VOLTAGE") "35V"))
      (libsource (lib "Altium Content Vault") (part "a00bbbee19879c290e62620ae7e47b1"))
    )
    (comp (ref "C42")
      (value "35SVPF22M")
      (footprint "FP-OS-CON-SMT-C6-MFG")
      (description "Conductive Polymer Aluminum Solid Capacitors (OS-CON) 22uF ±20% 35V")
      (fields (field (name "TOLERANCE") "20%") (field (name "VOLTAGE") "35V"))
      (libsource (lib "Altium Content Vault") (part "a00bbbee19879c290e62620ae7e47b1"))
    )
    (comp (ref "C61")
      (value "GRM31CR71H475KA12L")
      (footprint "FP-GRM31C-0_2-e0_3_0_8-IPC_C")
      (description "Chip Multilayer Ceramic Capacitors for General Purpose, 1206, 4.7uF, X7R, 15%, 10%, 50V")
      (fields (field (name "VOLTAGE") "50V") (field (name "TOLERANCE") "10%"))
      (libsource (lib "Altium Content Vault") (part "02cd4be3c70576c341d710602a673aa"))
    )
    (comp (ref "C62")
      (value "C0805C104M5RACTU")
      (footprint "FP-C0805C-DN-MFG")
      (description "CAP CER 0.1UF 50V X7R 0805")
      (fields
        (field (name "TOLERANCE") "0.2")
        (field (name "OCTOPART") "https://octopart.com/c0805c104m5ractu-kemet-129379")
      )
      (libsource (lib "Altium Content Vault") (part "b4654b650e69147ec39a6b967a45e02"))
    )
    (comp (ref "C63")
      (value "UMK105CG271JV-F")
      (footprint "FP-0402-L_1_0_0_05-W_0_5-IPC_B")
      (description "None")
      (fields (field (name "TOLERANCE") "5%"))
      (libsource (lib "Altium Content Vault") (part "b4654b650e69147ec39a6b967a45e02"))
    )
    (comp (ref "C64")
      (value "CGA4J2C0G1H333J125AA")
      (footprint "PcbLib1:CAP_2012_TDK-M")
      (description "No Description Available")
      (libsource (lib "CGA4J2C0G1H333J125AA") (part "CGA4J2C0G1H333J125AA"))
    )
    (comp (ref "C65")
      (value "GRM1555C1H101FA01D")
      (footprint "FP-GRM155-0_05-IPC_C")
      (description "CAP CER 100PF 50V C0G/NP0 0402")
      (fields (field (name "VOLTAGE") "50V") (field (name "TOLERANCE") "1%"))
      (libsource (lib "Altium Content Vault") (part "b4654b650e69147ec39a6b967a45e02"))
    )
    (comp (ref "C66")
      (value "GRM1555C1E5R1CA01D")
      (footprint "CAPC1005X55X25LL05T10")
      (fields (field (name "MANUFACTURER") "Murata"))
      (libsource (lib "Altium Content Vault") (part "CAP"))
    )
    (comp (ref "C67")
      (value "TMK212BJ105KG-T")
      (footprint "CAP_TMK212BJ105KG-T_TAY")
      (description "No Description Available")
      (libsource (lib "TMK212BJ105KG-T") (part "TMK212BJ105KG-T"))
    )
    (comp (ref "C68")
      (value "08053C104K4T2A")
      (footprint "CAPC2013X140X50LL20T25")
      (fields (field (name "MANUFACTURER") "AVX Interconnect / Elco"))
      (libsource (lib "Altium Content Vault") (part "CAP"))
    )
    (comp (ref "C69")
      (value "GRM31CR71H475KA12L")
      (footprint "FP-GRM31C-0_2-e0_3_0_8-IPC_C")
      (description "Chip Multilayer Ceramic Capacitors for General Purpose, 1206, 4.7uF, X7R, 15%, 10%, 50V")
      (fields (field (name "VOLTAGE") "50V") (field (name "TOLERANCE") "10%"))
      (libsource (lib "Altium Content Vault") (part "02cd4be3c70576c341d710602a673aa"))
    )
    (comp (ref "C70")
      (value "C0805C104M5RACTU")
      (footprint "FP-C0805C-DN-MFG")
      (description "CAP CER 0.1UF 50V X7R 0805")
      (fields
        (field (name "TOLERANCE") "0.2")
        (field (name "OCTOPART") "https://octopart.com/c0805c104m5ractu-kemet-129379")
      )
      (libsource (lib "Altium Content Vault") (part "b4654b650e69147ec39a6b967a45e02"))
    )
    (comp (ref "C71")
      (value "UMK105CG181JV-F")
      (footprint "PcbLib1:cap_UMK105 CG080CV-F_TAY")
      (description "No Description Available")
      (libsource (lib "UMK105CG181JV-F") (part "UMK105CG181JV-F"))
    )
    (comp (ref "C72")
      (value "CGA4J2C0G1H333J125AA")
      (footprint "CAP_2012_TDK-M")
      (description "No Description Available")
      (libsource (lib "CGA4J2C0G1H333J125AA") (part "CGA4J2C0G1H333J125AA"))
    )
    (comp (ref "C73")
      (value "C0805C100M4GACTU")
      (footprint "FP-C0805C-DN-MFG")
      (description "CAP CER 10PF 16V 20% NP0 0805")
      (fields
        (field (name "OCTOPART") "https://octopart.com/c0805c100m4gactu-kemet-16430157")
        (field (name "TOLERANCE") "0.2")
      )
      (libsource (lib "Altium Content Vault") (part "b4654b650e69147ec39a6b967a45e02"))
    )
    (comp (ref "C74")
      (value "UMK105CG271JV-F")
      (footprint "FP-0402-L_1_0_0_05-W_0_5-IPC_B")
      (description "None")
      (fields (field (name "TOLERANCE") "5%"))
      (libsource (lib "Altium Content Vault") (part "b4654b650e69147ec39a6b967a45e02"))
    )
    (comp (ref "C75")
      (value "TMK212BJ105KG-T")
      (footprint "CAP_TMK212BJ105KG-T_TAY")
      (description "No Description Available")
      (libsource (lib "TMK212BJ105KG-T") (part "TMK212BJ105KG-T"))
    )
    (comp (ref "C76")
      (value "08053C104K4T2A")
      (footprint "CAPC2013X140X50LL20T25")
      (fields (field (name "MANUFACTURER") "AVX Interconnect / Elco"))
      (libsource (lib "Altium Content Vault") (part "CAP"))
    )
    (comp (ref "C77")
      (value "GRM32ER61C476KE15L")
      (footprint "FP-GRM32E-0_3-0_2-IPC_C")
      (description "CAP CER 47UF 16V X5R 1210")
      (fields (field (name "VOLTAGE") "16V") (field (name "TOLERANCE") "10%"))
      (libsource (lib "Altium Content Vault") (part "b4654b650e69147ec39a6b967a45e02"))
    )
    (comp (ref "C78")
      (value "GRM31CR71H475KA12L")
      (footprint "FP-GRM31C-0_2-e0_3_0_8-IPC_C")
      (description "Chip Multilayer Ceramic Capacitors for General Purpose, 1206, 4.7uF, X7R, 15%, 10%, 50V")
      (fields (field (name "VOLTAGE") "50V") (field (name "TOLERANCE") "10%"))
      (libsource (lib "Altium Content Vault") (part "02cd4be3c70576c341d710602a673aa"))
    )
    (comp (ref "C79")
      (value "C0805C104M5RACTU")
      (footprint "FP-C0805C-DN-MFG")
      (description "CAP CER 0.1UF 50V X7R 0805")
      (fields
        (field (name "TOLERANCE") "0.2")
        (field (name "OCTOPART") "https://octopart.com/c0805c104m5ractu-kemet-129379")
      )
      (libsource (lib "Altium Content Vault") (part "b4654b650e69147ec39a6b967a45e02"))
    )
    (comp (ref "C80")
      (value "GRM1555C1H101FA01D")
      (footprint "FP-GRM155-0_05-IPC_C")
      (description "CAP CER 100PF 50V C0G/NP0 0402")
      (fields (field (name "VOLTAGE") "50V") (field (name "TOLERANCE") "1%"))
      (libsource (lib "Altium Content Vault") (part "b4654b650e69147ec39a6b967a45e02"))
    )
    (comp (ref "C81")
      (value "CGA4J2C0G1H333J125AA")
      (footprint "CAP_2012_TDK-M")
      (description "No Description Available")
      (libsource (lib "CGA4J2C0G1H333J125AA") (part "CGA4J2C0G1H333J125AA"))
    )
    (comp (ref "C82")
      (value "GRM1555C1E120JA01D")
      (footprint "CAPC1005X55X25LL05T10")
      (fields (field (name "MANUFACTURER") "Murata"))
      (libsource (lib "Altium Content Vault") (part "CAP"))
    )
    (comp (ref "C83")
      (value "GRM1555C1H391JA01J")
      (footprint "FP-GRM155-0_05-IPC_A")
      (description "Chip Multilayer Ceramic Capacitors for General Purpose, 0402, 390pF, C0G, 30ppm/°C, 5%, 50V")
      (fields (field (name "VOLTAGE") "50V") (field (name "TOLERANCE") "5%"))
      (libsource (lib "Altium Content Vault") (part "02cd4be3c70576c341d710602a673aa"))
    )
    (comp (ref "C84")
      (value "TMK212BJ105KG-T")
      (footprint "CAP_TMK212BJ105KG-T_TAY")
      (description "No Description Available")
      (libsource (lib "TMK212BJ105KG-T") (part "TMK212BJ105KG-T"))
    )
    (comp (ref "C85")
      (value "08053C104K4T2A")
      (footprint "CAPC2013X140X50LL20T25")
      (fields (field (name "MANUFACTURER") "AVX Interconnect / Elco"))
      (libsource (lib "Altium Content Vault") (part "CAP"))
    )
    (comp (ref "C86")
      (value "GRM32ER61C476KE15L")
      (footprint "FP-GRM32E-0_3-0_2-IPC_C")
      (description "CAP CER 47UF 16V X5R 1210")
      (fields (field (name "VOLTAGE") "16V") (field (name "TOLERANCE") "10%"))
      (libsource (lib "Altium Content Vault") (part "b4654b650e69147ec39a6b967a45e02"))
    )
    (comp (ref "Cb1")
      (value "GCJ188R72A104KA01D")
      (footprint "FP-GCJ188-0_2-IPC_A")
      (description "Cap Ceramic 0.1uF 100V X7R 10% Pad SMD 0603 Soft Termination +125°C Automotive T/R")
      (fields (field (name "TOLERANCE") "10%"))
      (libsource (lib "Altium Content Vault") (part "f23184f103b6ebe33a8c269c53dcba6"))
    )
    (comp (ref "Cb2")
      (value "GCJ188R72A104KA01D")
      (footprint "FP-GCJ188-0_2-IPC_A")
      (description "Cap Ceramic 0.1uF 100V X7R 10% Pad SMD 0603 Soft Termination +125°C Automotive T/R")
      (fields (field (name "TOLERANCE") "10%"))
      (libsource (lib "Altium Content Vault") (part "f23184f103b6ebe33a8c269c53dcba6"))
    )
    (comp (ref "Cb3")
      (value "GCJ188R72A104KA01D")
      (footprint "FP-GCJ188-0_2-IPC_A")
      (description "Cap Ceramic 0.1uF 100V X7R 10% Pad SMD 0603 Soft Termination +125°C Automotive T/R")
      (fields (field (name "TOLERANCE") "10%"))
      (libsource (lib "Altium Content Vault") (part "f23184f103b6ebe33a8c269c53dcba6"))
    )
    (comp (ref "Cb4")
      (value "GCJ188R72A104KA01D")
      (footprint "FP-GCJ188-0_2-IPC_A")
      (description "Cap Ceramic 0.1uF 100V X7R 10% Pad SMD 0603 Soft Termination +125°C Automotive T/R")
      (fields (field (name "TOLERANCE") "10%"))
      (libsource (lib "Altium Content Vault") (part "f23184f103b6ebe33a8c269c53dcba6"))
    )
    (comp (ref "Cb5")
      (value "GCJ188R72A104KA01D")
      (footprint "FP-GCJ188-0_2-IPC_A")
      (description "Cap Ceramic 0.1uF 100V X7R 10% Pad SMD 0603 Soft Termination +125°C Automotive T/R")
      (fields (field (name "TOLERANCE") "10%"))
      (libsource (lib "Altium Content Vault") (part "f23184f103b6ebe33a8c269c53dcba6"))
    )
    (comp (ref "Cb6")
      (value "GCJ188R72A104KA01D")
      (footprint "FP-GCJ188-0_2-IPC_A")
      (description "Cap Ceramic 0.1uF 100V X7R 10% Pad SMD 0603 Soft Termination +125°C Automotive T/R")
      (fields (field (name "TOLERANCE") "10%"))
      (libsource (lib "Altium Content Vault") (part "f23184f103b6ebe33a8c269c53dcba6"))
    )
    (comp (ref "Cb7")
      (value "GCJ188R72A104KA01D")
      (footprint "FP-GCJ188-0_2-IPC_A")
      (description "Cap Ceramic 0.1uF 100V X7R 10% Pad SMD 0603 Soft Termination +125°C Automotive T/R")
      (fields (field (name "TOLERANCE") "10%"))
      (libsource (lib "Altium Content Vault") (part "f23184f103b6ebe33a8c269c53dcba6"))
    )
    (comp (ref "Cb8")
      (value "GCJ188R72A104KA01D")
      (footprint "FP-GCJ188-0_2-IPC_A")
      (description "Cap Ceramic 0.1uF 100V X7R 10% Pad SMD 0603 Soft Termination +125°C Automotive T/R")
      (fields (field (name "TOLERANCE") "10%"))
      (libsource (lib "Altium Content Vault") (part "f23184f103b6ebe33a8c269c53dcba6"))
    )
    (comp (ref "Cb9")
      (value "GCJ188R72A104KA01D")
      (footprint "FP-GCJ188-0_2-IPC_A")
      (description "Cap Ceramic 0.1uF 100V X7R 10% Pad SMD 0603 Soft Termination +125°C Automotive T/R")
      (fields (field (name "TOLERANCE") "10%"))
      (libsource (lib "Altium Content Vault") (part "f23184f103b6ebe33a8c269c53dcba6"))
    )
    (comp (ref "Cb11")
      (value "GCJ188R72A104KA01D")
      (footprint "FP-GCJ188-0_2-IPC_A")
      (description "Cap Ceramic 0.1uF 100V X7R 10% Pad SMD 0603 Soft Termination +125°C Automotive T/R")
      (fields (field (name "TOLERANCE") "10%"))
      (libsource (lib "Altium Content Vault") (part "f23184f103b6ebe33a8c269c53dcba6"))
    )
    (comp (ref "Cb12")
      (value "GCJ188R72A104KA01D")
      (footprint "FP-GCJ188-0_2-IPC_A")
      (description "Cap Ceramic 0.1uF 100V X7R 10% Pad SMD 0603 Soft Termination +125°C Automotive T/R")
      (fields (field (name "TOLERANCE") "10%"))
      (libsource (lib "Altium Content Vault") (part "f23184f103b6ebe33a8c269c53dcba6"))
    )
    (comp (ref "Cb13")
      (value "GCJ188R72A104KA01D")
      (footprint "FP-GCJ188-0_2-IPC_A")
      (description "Cap Ceramic 0.1uF 100V X7R 10% Pad SMD 0603 Soft Termination +125°C Automotive T/R")
      (fields (field (name "TOLERANCE") "10%"))
      (libsource (lib "Altium Content Vault") (part "f23184f103b6ebe33a8c269c53dcba6"))
    )
    (comp (ref "Cb14")
      (value "GCJ188R72A104KA01D")
      (footprint "FP-GCJ188-0_2-IPC_A")
      (description "Cap Ceramic 0.1uF 100V X7R 10% Pad SMD 0603 Soft Termination +125°C Automotive T/R")
      (fields (field (name "TOLERANCE") "10%"))
      (libsource (lib "Altium Content Vault") (part "f23184f103b6ebe33a8c269c53dcba6"))
    )
    (comp (ref "Cb15")
      (value "GCJ188R72A104KA01D")
      (footprint "FP-GCJ188-0_2-IPC_A")
      (description "Cap Ceramic 0.1uF 100V X7R 10% Pad SMD 0603 Soft Termination +125°C Automotive T/R")
      (fields (field (name "TOLERANCE") "10%"))
      (libsource (lib "Altium Content Vault") (part "f23184f103b6ebe33a8c269c53dcba6"))
    )
    (comp (ref "Cb16")
      (value "GCJ188R72A104KA01D")
      (footprint "FP-GCJ188-0_2-IPC_A")
      (description "Cap Ceramic 0.1uF 100V X7R 10% Pad SMD 0603 Soft Termination +125°C Automotive T/R")
      (fields (field (name "TOLERANCE") "10%"))
      (libsource (lib "Altium Content Vault") (part "f23184f103b6ebe33a8c269c53dcba6"))
    )
    (comp (ref "Cb17")
      (value "GCJ188R72A104KA01D")
      (footprint "FP-GCJ188-0_2-IPC_A")
      (description "Cap Ceramic 0.1uF 100V X7R 10% Pad SMD 0603 Soft Termination +125°C Automotive T/R")
      (fields (field (name "TOLERANCE") "10%"))
      (libsource (lib "Altium Content Vault") (part "f23184f103b6ebe33a8c269c53dcba6"))
    )
    (comp (ref "Cb18")
      (value "GCJ188R72A104KA01D")
      (footprint "FP-GCJ188-0_2-IPC_A")
      (description "Cap Ceramic 0.1uF 100V X7R 10% Pad SMD 0603 Soft Termination +125°C Automotive T/R")
      (fields (field (name "TOLERANCE") "10%"))
      (libsource (lib "Altium Content Vault") (part "f23184f103b6ebe33a8c269c53dcba6"))
    )
    (comp (ref "Cb19")
      (value "GCJ188R72A104KA01D")
      (footprint "FP-GCJ188-0_2-IPC_A")
      (description "Cap Ceramic 0.1uF 100V X7R 10% Pad SMD 0603 Soft Termination +125°C Automotive T/R")
      (fields (field (name "TOLERANCE") "10%"))
      (libsource (lib "Altium Content Vault") (part "f23184f103b6ebe33a8c269c53dcba6"))
    )
    (comp (ref "Cbp")
      (value "GCJ188R72A104KA01D")
      (footprint "FP-GCJ188-0_2-IPC_A")
      (description "Cap Ceramic 0.1uF 100V X7R 10% Pad SMD 0603 Soft Termination +125°C Automotive T/R")
      (fields (field (name "TOLERANCE") "10%"))
      (libsource (lib "Altium Content Vault") (part "f23184f103b6ebe33a8c269c53dcba6"))
    )
    (comp (ref "Cbp2")
      (value "GCJ188R72A104KA01D")
      (footprint "FP-GCJ188-0_2-IPC_A")
      (description "Cap Ceramic 0.1uF 100V X7R 10% Pad SMD 0603 Soft Termination +125°C Automotive T/R")
      (fields (field (name "TOLERANCE") "10%"))
      (libsource (lib "Altium Content Vault") (part "f23184f103b6ebe33a8c269c53dcba6"))
    )
    (comp (ref "Cin2")
      (value "GRM31CR71H475KA12L")
      (footprint "FP-GRM31C-0_2-e0_3_0_8-IPC_C")
      (description "Chip Multilayer Ceramic Capacitors for General Purpose, 1206, 4.7uF, X7R, 15%, 10%, 50V")
      (fields (field (name "VOLTAGE") "50V") (field (name "TOLERANCE") "10%"))
      (libsource (lib "Altium Content Vault") (part "02cd4be3c70576c341d710602a673aa"))
    )
    (comp (ref "Cinx2")
      (value "C0805C104M5RACTU")
      (footprint "FP-C0805C-DN-MFG")
      (description "CAP CER 0.1UF 50V X7R 0805")
      (fields
        (field (name "TOLERANCE") "0.2")
        (field (name "OCTOPART") "https://octopart.com/c0805c104m5ractu-kemet-129379")
      )
      (libsource (lib "Altium Content Vault") (part "b4654b650e69147ec39a6b967a45e02"))
    )
    (comp (ref "CR15")
      (value "SMCJ75A-13-F")
      (footprint "SMC_DIO")
      (description "No Description Available")
      (libsource (lib "SMCJ75A-13-F") (part "SMCJ75A-13-F"))
    )
    (comp (ref "D1")
      (value "BAS516")
      (footprint "SOD523_NEX")
      (description "No Description Available")
      (libsource (lib "BAS516") (part "BAS516"))
    )
    (comp (ref "D2")
      (value "BAS516")
      (footprint "SOD523_NEX")
      (description "No Description Available")
      (libsource (lib "BAS516") (part "BAS516"))
    )
    (comp (ref "D3")
      (value "BAS516")
      (footprint "SOD523_NEX")
      (description "No Description Available")
      (libsource (lib "BAS516") (part "BAS516"))
    )
    (comp (ref "D4")
      (value "BAS516")
      (footprint "SOD523_NEX")
      (description "No Description Available")
      (libsource (lib "BAS516") (part "BAS516"))
    )
    (comp (ref "D5")
      (value "BAS516")
      (footprint "SOD523_NEX")
      (description "No Description Available")
      (libsource (lib "BAS516") (part "BAS516"))
    )
    (comp (ref "Fans")
      (value "1720650202")
      (footprint "CONN_SD-768290002_02_MOL")
      (description "No Description Available")
      (libsource (lib "1720650202") (part "1720650202"))
    )
    (comp (ref "Fans_F")
      (value "3568")
      (footprint "FP-3568-MFG")
      (fields (field (name "VOLTAGE") "500V"))
      (libsource (lib "Altium Content Vault") (part "3568"))
    )
    (comp (ref "Fans_L")
      (value "LS L29K-H1J2-1-Z")
      (footprint "FP-LS_L29K-MFG")
      (description "LED RED DIFFUSED 0603 SMD")
      (libsource (lib "Altium Content Vault") (part "8706943c75ba83719d021d2fdc84c58"))
    )
    (comp (ref "J2")
      (value "PPTC021LFBN-RC")
      (footprint "CONN2_LFBN-RC_SUL - duplicate")
      (description "No Description Available")
      (libsource (lib "PPTC021LFBN-RC") (part "PPTC021LFBN-RC"))
    )
    (comp (ref "JR")
      (value "SSQ-101-03-G-S")
      (footprint "CON1_1X1_TU_SSQ")
      (description "No Description Available")
      (libsource (lib "SSQ-101-03-G-S") (part "SSQ-101-03-G-S"))
    )
    (comp (ref "K1")
      (value "HE1AN-W-DC12V-Y6")
      (footprint "FP-HE1AN-W-DC12V-Y6-MFG")
      (description "HE1AN-W-DC12V-Y6 HE Series SPST 12 V 90 A PV Type Solar Inverter General Purpose Power Relay")
      (libsource (lib "Altium Content Vault") (part "f9dd24d2cbaee63af32e9eefbadd5b8"))
    )
    (comp (ref "K2")
      (value "HE1AN-W-DC12V-Y6")
      (footprint "FP-HE1AN-W-DC12V-Y6-MFG")
      (description "HE1AN-W-DC12V-Y6 HE Series SPST 12 V 90 A PV Type Solar Inverter General Purpose Power Relay")
      (libsource (lib "Altium Content Vault") (part "f9dd24d2cbaee63af32e9eefbadd5b8"))
    )
    (comp (ref "L1")
      (value "IHLP5050FDER1R8M01")
      (footprint "IND_IHLP_5050_FD_VIS")
      (description "No Description Available")
      (libsource (lib "IHLP5050FDER1R8M01") (part "IHLP5050FDER1R8M01"))
    )
    (comp (ref "L1_2")
      (value "MSS1038-123MLB")
      (footprint "IND_MSS1038_COC")
      (description "No Description Available")
      (libsource (lib "MSS1038-123MLB") (part "MSS1038-123MLB"))
    )
    (comp (ref "L1_3")
      (value "XAL6060-562MEB")
      (footprint "IND_XAL6060_COC")
      (description "No Description Available")
      (libsource (lib "XAL6060-562MEB") (part "XAL6060-562MEB"))
    )
    (comp (ref "L1_4")
      (value "SER1052-402MLB")
      (footprint "IND_SER1052_COC")
      (description "No Description Available")
      (libsource (lib "SER1052-402MLB") (part "SER1052-402MLB"))
    )
    (comp (ref "L1_5")
      (value "XAL5030-222MEB")
      (footprint "FP-XAL5030-222MEB-MFG")
      (description "Fixed Inductors 2.2uH 20% 9.7A 14.5mOhms")
      (fields (field (name "TOLERANCE") "20%"))
      (libsource (lib "Altium Content Vault") (part "725321dda6339637d4d059423bc1c3c"))
    )
    (comp (ref "M1")
      (value "CSD18537NQ5A")
      (footprint "FP-DQJ0008A-MFG")
      (description "MOSFET N-CH 60V 50A 8SON")
      (libsource (lib "Altium Content Vault") (part "7382af88e928fdc71488234cfaaf11c"))
    )
    (comp (ref "M1_2")
      (value "CSD18537NQ5A")
      (footprint "FP-DQJ0008A-MFG")
      (description "MOSFET N-CH 60V 50A 8SON")
      (libsource (lib "Altium Content Vault") (part "7382af88e928fdc71488234cfaaf11c"))
    )
    (comp (ref "M1_3")
      (value "CSD18537NQ5A")
      (footprint "FP-DQJ0008A-MFG")
      (description "MOSFET N-CH 60V 50A 8SON")
      (libsource (lib "Altium Content Vault") (part "7382af88e928fdc71488234cfaaf11c"))
    )
    (comp (ref "M1_4")
      (value "CSD18537NQ5A")
      (footprint "FP-DQJ0008A-MFG")
      (description "MOSFET N-CH 60V 50A 8SON")
      (libsource (lib "Altium Content Vault") (part "7382af88e928fdc71488234cfaaf11c"))
    )
    (comp (ref "M2")
      (value "CSD16556Q5B")
      (footprint "DNK0008A")
      (description "No Description Available")
      (libsource (lib "CSD16556Q5B") (part "CSD16556Q5B"))
    )
    (comp (ref "MCM")
      (value "1720650202")
      (footprint "CONN_SD-768290002_02_MOL")
      (description "No Description Available")
      (libsource (lib "1720650202") (part "1720650202"))
    )
    (comp (ref "MCM_F")
      (value "3568")
      (footprint "FP-3568-MFG")
      (fields (field (name "VOLTAGE") "500V"))
      (libsource (lib "Altium Content Vault") (part "3568"))
    )
    (comp (ref "MCM_L")
      (value "LS L29K-H1J2-1-Z")
      (footprint "FP-LS_L29K-MFG")
      (description "LED RED DIFFUSED 0603 SMD")
      (libsource (lib "Altium Content Vault") (part "8706943c75ba83719d021d2fdc84c58"))
    )
    (comp (ref "MD2_F")
      (value "3568")
      (footprint "FP-3568-MFG")
      (fields (field (name "VOLTAGE") "500V"))
      (libsource (lib "Altium Content Vault") (part "3568"))
    )
    (comp (ref "MD_1")
      (value "428192233")
      (footprint "CON_428192233")
      (description "No Description Available")
      (libsource (lib "428192233") (part "428192233"))
    )
    (comp (ref "MD_2")
      (value "428192233")
      (footprint "CON_428192233")
      (description "No Description Available")
      (libsource (lib "428192233") (part "428192233"))
    )
    (comp (ref "MD_F")
      (value "3568")
      (footprint "FP-3568-MFG")
      (fields (field (name "VOLTAGE") "500V"))
      (libsource (lib "Altium Content Vault") (part "3568"))
    )
    (comp (ref "MD_L")
      (value "LS L29K-H1J2-1-Z")
      (footprint "FP-LS_L29K-MFG")
      (description "LED RED DIFFUSED 0603 SMD")
      (libsource (lib "Altium Content Vault") (part "8706943c75ba83719d021d2fdc84c58"))
    )
    (comp (ref "Motor")
      (value "LS L29K-H1J2-1-Z")
      (footprint "FP-LS_L29K-MFG")
      (description "LED RED DIFFUSED 0603 SMD")
      (libsource (lib "Altium Content Vault") (part "8706943c75ba83719d021d2fdc84c58"))
    )
    (comp (ref "MP+")
      (value "7461147")
      (footprint "7461147_chemical surface")
      (description "7461147 REDCUBE Power Element Poles, 180A, Press-Fit, M5 Internal Thread, Vertical, WP-BUFU")
      (libsource (lib "BMS_FETs") (part "7461147"))
    )
    (comp (ref "MP-")
      (value "7461147")
      (footprint "7461147_chemical surface")
      (description "7461147 REDCUBE Power Element Poles, 180A, Press-Fit, M5 Internal Thread, Vertical, WP-BUFU")
      (libsource (lib "BMS_FETs") (part "7461147"))
    )
    (comp (ref "MP1")
      (value "9774050482R")
      (footprint "9774050482")
      (description "9774050482R WA-SMSI SMT Steel Spacer, M4 Internal non Stop")
      (libsource (lib "Altium Content Vault") (part "Spacer"))
    )
    (comp (ref "MP2")
      (value "9774050482R")
      (footprint "9774050482")
      (description "9774050482R WA-SMSI SMT Steel Spacer, M4 Internal non Stop")
      (libsource (lib "Altium Content Vault") (part "Spacer"))
    )
    (comp (ref "MP3")
      (value "9774050482R")
      (footprint "9774050482")
      (description "9774050482R WA-SMSI SMT Steel Spacer, M4 Internal non Stop")
      (libsource (lib "Altium Content Vault") (part "Spacer"))
    )
    (comp (ref "MP4")
      (value "9774050482R")
      (footprint "9774050482")
      (description "9774050482R WA-SMSI SMT Steel Spacer, M4 Internal non Stop")
      (libsource (lib "Altium Content Vault") (part "Spacer"))
    )
    (comp (ref "P+fans")
      (value "61301211121")
      (footprint "61301211121")
      (libsource (lib "Altium Content Vault") (part "Header_Male_1R_12P"))
    )
    (comp (ref "Q1")
      (value "CSD18534Q5A")
      (footprint "FP-DQJ0008A-MFG")
      (description "MOSFET N-CH 60V 8SON")
      (fields
        (field (name "OCTOPART") "https://octopart.com/csd18534q5a-texas+instruments-22791040")
        (field (name "MANUFACTURER") "Texas Instruments")
      )
      (libsource (lib "Altium Content Vault") (part "2b493a92fcdc54dddf28a3aa2503ef1"))
    )
    (comp (ref "Q2")
      (value "CSD18534Q5A")
      (footprint "FP-DQJ0008A-MFG")
      (description "MOSFET N-CH 60V 8SON")
      (fields
        (field (name "OCTOPART") "https://octopart.com/csd18534q5a-texas+instruments-22791040")
        (field (name "MANUFACTURER") "Texas Instruments")
      )
      (libsource (lib "Altium Content Vault") (part "2b493a92fcdc54dddf28a3aa2503ef1"))
    )
    (comp (ref "Q3")
      (value "CSD18537NQ5A")
      (footprint "FP-DQJ0008A-MFG")
      (description "MOSFET N-CH 60V 50A 8SON")
      (libsource (lib "Altium Content Vault") (part "7382af88e928fdc71488234cfaaf11c"))
    )
    (comp (ref "Q4")
      (value "CSD18534Q5A")
      (footprint "FP-DQJ0008A-MFG")
      (description "MOSFET N-CH 60V 8SON")
      (fields
        (field (name "OCTOPART") "https://octopart.com/csd18534q5a-texas+instruments-22791040")
        (field (name "MANUFACTURER") "Texas Instruments")
      )
      (libsource (lib "Altium Content Vault") (part "2b493a92fcdc54dddf28a3aa2503ef1"))
    )
    (comp (ref "Q5")
      (value "CSD18537NQ5A")
      (footprint "FP-DQJ0008A-MFG")
      (description "MOSFET N-CH 60V 50A 8SON")
      (libsource (lib "Altium Content Vault") (part "7382af88e928fdc71488234cfaaf11c"))
    )
    (comp (ref "Q6")
      (value "CSD18534Q5A")
      (footprint "FP-DQJ0008A-MFG")
      (description "MOSFET N-CH 60V 8SON")
      (fields
        (field (name "OCTOPART") "https://octopart.com/csd18534q5a-texas+instruments-22791040")
        (field (name "MANUFACTURER") "Texas Instruments")
      )
      (libsource (lib "Altium Content Vault") (part "2b493a92fcdc54dddf28a3aa2503ef1"))
    )
    (comp (ref "R1")
      (value "CRCW04021M00FKED")
      (footprint "FP-CRCW0402-e3-MFG")
      (description "RES Thick Film, 1MΩ, 1%, 0.063W, 100ppm/°C, 0402")
      (fields (field (name "TOLERANCE") "1%"))
      (libsource (lib "Altium Content Vault") (part "1029c3af85768c4190bb7ad29bc67b5"))
    )
    (comp (ref "R2")
      (value "CRCW080541K2FKEA")
      (footprint "Vishay_CRCW0805-e3_MFG")
      (fields (field (name "TOLERANCE") "1%"))
      (libsource (lib "Altium Content Vault") (part "CRCW080541K2FKEA"))
    )
    (comp (ref "R3")
      (value "ERJ-6ENF2491V")
      (footprint "RESC2013X70X40LL20T20")
      (fields (field (name "MANUFACTURER") "Panasonic"))
      (libsource (lib "Altium Content Vault") (part "RES"))
    )
    (comp (ref "R4")
      (value "CRCW04025K23FKED")
      (footprint "FP-CRCW0402-e3-IPC_C")
      (description "RES Thick Film, 5.23kΩ, 1%, 0.063W, 100ppm/°C, 0402")
      (fields (field (name "TOLERANCE") "1%"))
      (libsource (lib "Altium Content Vault") (part "1029c3af85768c4190bb7ad29bc67b5"))
    )
    (comp (ref "R5")
      (value "CRCW0402102KFKED")
      (footprint "RESC1005X40X25ML05T05")
      (fields (field (name "MANUFACTURER") "Vishay Dale"))
      (libsource (lib "Altium Content Vault") (part "RES"))
    )
    (comp (ref "R6")
      (value "CSNL1206FT3L00")
      (footprint "STA_CSNL1206_STP")
      (description "No Description Available")
      (libsource (lib "CSNL1206FT3L00") (part "CSNL1206FT3L00"))
    )
    (comp (ref "R7")
      (value "CRCW120656K0FKEA")
      (footprint "FP-CRCW1206-e3-IPC_C")
      (description "RES Thick Film, 56kΩ, 1%, 0.25W, 100ppm/°C, 1206")
      (fields (field (name "TOLERANCE") "1%"))
      (libsource (lib "Altium Content Vault") (part "1029c3af85768c4190bb7ad29bc67b5"))
    )
    (comp (ref "R8")
      (value "3296X-1-102LF")
      (footprint "PcbLib1:POT_3296X")
      (description "No Description Available")
      (libsource (lib "3296X-1-102LF") (part "3296X-1-102LF"))
    )
    (comp (ref "R9")
      (value "RC0603FR-0710KL")
      (footprint "FP-RC0603-0_55-IPC_C")
      (description "RES 10K OHM 1% 1/10W 0603")
      (fields (field (name "TOLERANCE") "1%"))
      (libsource (lib "Altium Content Vault") (part "1029c3af85768c4190bb7ad29bc67b5"))
    )
    (comp (ref "R11")
      (value "CRCW06035K10FKEA")
      (footprint "FP-CRCW0603-e3-IPC_C")
      (description "RES Thick Film, 5.1kΩ, 1%, 0.1W, 100ppm/°C, 0603")
      (fields (field (name "TOLERANCE") "1%"))
      (libsource (lib "Altium Content Vault") (part "1029c3af85768c4190bb7ad29bc67b5"))
    )
    (comp (ref "R12")
      (value "CRCW080541K2FKEA")
      (footprint "Vishay_CRCW0805-e3_MFG")
      (fields (field (name "TOLERANCE") "1%"))
      (libsource (lib "Altium Content Vault") (part "CRCW080541K2FKEA"))
    )
    (comp (ref "R13")
      (value "ERJ-6ENF2491V")
      (footprint "RESC2013X70X40LL20T20")
      (fields (field (name "MANUFACTURER") "Panasonic"))
      (libsource (lib "Altium Content Vault") (part "RES"))
    )
    (comp (ref "R14")
      (value "CRCW04025K23FKED")
      (footprint "FP-CRCW0402-e3-IPC_C")
      (description "RES Thick Film, 5.23kΩ, 1%, 0.063W, 100ppm/°C, 0402")
      (fields (field (name "TOLERANCE") "1%"))
      (libsource (lib "Altium Content Vault") (part "1029c3af85768c4190bb7ad29bc67b5"))
    )
    (comp (ref "R15")
      (value "CRCW0402191KFKED")
      (footprint "FP-CRCW0402-e3-IPC_C")
      (description "RES Thick Film, 191kΩ, 1%, 0.063W, 100ppm/°C, 0402")
      (fields (field (name "TOLERANCE") "1%"))
      (libsource (lib "Altium Content Vault") (part "1029c3af85768c4190bb7ad29bc67b5"))
    )
    (comp (ref "R16")
      (value "CRCW04021M00FKED")
      (footprint "FP-CRCW0402-e3-MFG")
      (description "RES Thick Film, 1MΩ, 1%, 0.063W, 100ppm/°C, 0402")
      (fields (field (name "TOLERANCE") "1%"))
      (libsource (lib "Altium Content Vault") (part "1029c3af85768c4190bb7ad29bc67b5"))
    )
    (comp (ref "R17")
      (value "CSR1206FK15L0")
      (footprint "FP-CSR1206-IPC_B")
      (description "General Purpose Thick Film Chip Resistor, 1206, 15mΩ, 1%, 0.5W")
      (fields (field (name "TOLERANCE") "1%"))
      (libsource (lib "Altium Content Vault") (part "1029c3af85768c4190bb7ad29bc67b5"))
    )
    (comp (ref "R18")
      (value "AC0402FR-0786K6L")
      (footprint "FP-AC0402-IPC_B")
      (description "RES 86.6kΩ ±1% 0.063W 0402")
      (fields (field (name "TOLERANCE") "1%"))
      (libsource (lib "Altium Content Vault") (part "1029c3af85768c4190bb7ad29bc67b5"))
    )
    (comp (ref "R19")
      (value "ERJ-6ENF9761V")
      (footprint "RESC2013X70X40ML20T20")
      (fields (field (name "MANUFACTURER") "Panasonic"))
      (libsource (lib "Altium Content Vault") (part "RES"))
    )
    (comp (ref "R20")
      (value "RC0603FR-0710KL")
      (footprint "FP-RC0603-0_55-IPC_C")
      (description "RES 10K OHM 1% 1/10W 0603")
      (fields (field (name "TOLERANCE") "1%"))
      (libsource (lib "Altium Content Vault") (part "1029c3af85768c4190bb7ad29bc67b5"))
    )
    (comp (ref "R21")
      (value "RC0603FR-073K3L")
      (footprint "FP-RC0603-0_55-MFG")
      (fields (field (name "TOLERANCE") "1%"))
      (libsource (lib "Altium Content Vault") (part "1029c3af85768c4190bb7ad29bc67b5"))
    )
    (comp (ref "R22")
      (value "CRCW080541K2FKEA")
      (footprint "Vishay_CRCW0805-e3_MFG")
      (fields (field (name "TOLERANCE") "1%"))
      (libsource (lib "Altium Content Vault") (part "CRCW080541K2FKEA"))
    )
    (comp (ref "R23")
      (value "ERJ-6ENF2491V")
      (footprint "RESC2013X70X40LL20T20")
      (fields (field (name "MANUFACTURER") "Panasonic"))
      (libsource (lib "Altium Content Vault") (part "RES"))
    )
    (comp (ref "R24")
      (value "CRCW04025K23FKED")
      (footprint "FP-CRCW0402-e3-IPC_C")
      (description "RES Thick Film, 5.23kΩ, 1%, 0.063W, 100ppm/°C, 0402")
      (fields (field (name "TOLERANCE") "1%"))
      (libsource (lib "Altium Content Vault") (part "1029c3af85768c4190bb7ad29bc67b5"))
    )
    (comp (ref "R25")
      (value "CRCW0402143KFKED")
      (footprint "FP-CRCW0402-e3-IPC_A")
      (description "RES Thick Film, 143kΩ, 1%, 0.063W, 100ppm/°C, 0402")
      (fields (field (name "TOLERANCE") "1%"))
      (libsource (lib "Altium Content Vault") (part "1029c3af85768c4190bb7ad29bc67b5"))
    )
    (comp (ref "R26")
      (value "CRCW04021M00FKED")
      (footprint "FP-CRCW0402-e3-MFG")
      (description "RES Thick Film, 1MΩ, 1%, 0.063W, 100ppm/°C, 0402")
      (fields (field (name "TOLERANCE") "1%"))
      (libsource (lib "Altium Content Vault") (part "1029c3af85768c4190bb7ad29bc67b5"))
    )
    (comp (ref "R27")
      (value "PRL1632-R007-F-T1")
      (footprint "FP-PRL1632-IPC_C")
      (description "7 mOhms ±1% 1W Chip Resistor Wide 0612 (1632 Metric), Current Sense Thin Film")
      (fields (field (name "TOLERANCE") "1%"))
      (libsource (lib "Altium Content Vault") (part "1029c3af85768c4190bb7ad29bc67b5"))
    )
    (comp (ref "R28")
      (value "AC0402FR-0786K6L")
      (footprint "FP-AC0402-IPC_B")
      (description "RES 86.6kΩ ±1% 0.063W 0402")
      (fields (field (name "TOLERANCE") "1%"))
      (libsource (lib "Altium Content Vault") (part "1029c3af85768c4190bb7ad29bc67b5"))
    )
    (comp (ref "R29")
      (value "ERJ-6ENF9761V")
      (footprint "RESC2013X70X40ML20T20")
      (fields (field (name "MANUFACTURER") "Panasonic"))
      (libsource (lib "Altium Content Vault") (part "RES"))
    )
    (comp (ref "R40")
      (value "RC0603FR-0710KL")
      (footprint "FP-RC0603-0_55-IPC_C")
      (description "RES 10K OHM 1% 1/10W 0603")
      (fields (field (name "TOLERANCE") "1%"))
      (libsource (lib "Altium Content Vault") (part "1029c3af85768c4190bb7ad29bc67b5"))
    )
    (comp (ref "R41")
      (value "RC0603FR-073K3L")
      (footprint "FP-RC0603-0_55-MFG")
      (fields (field (name "TOLERANCE") "1%"))
      (libsource (lib "Altium Content Vault") (part "1029c3af85768c4190bb7ad29bc67b5"))
    )
    (comp (ref "R42")
      (value "CRCW080541K2FKEA")
      (footprint "Vishay_CRCW0805-e3_MFG")
      (fields (field (name "TOLERANCE") "1%"))
      (libsource (lib "Altium Content Vault") (part "CRCW080541K2FKEA"))
    )
    (comp (ref "R43")
      (value "ERJ-6ENF2491V")
      (footprint "RESC2013X70X40LL20T20")
      (fields (field (name "MANUFACTURER") "Panasonic"))
      (libsource (lib "Altium Content Vault") (part "RES"))
    )
    (comp (ref "R44")
      (value "CRCW04025K23FKED")
      (footprint "FP-CRCW0402-e3-IPC_C")
      (description "RES Thick Film, 5.23kΩ, 1%, 0.063W, 100ppm/°C, 0402")
      (fields (field (name "TOLERANCE") "1%"))
      (libsource (lib "Altium Content Vault") (part "1029c3af85768c4190bb7ad29bc67b5"))
    )
    (comp (ref "R45")
      (value "CRCW040266K5FKED")
      (footprint "RESC1005X40X25ML05T05")
      (fields (field (name "MANUFACTURER") "Vishay Dale"))
      (libsource (lib "Altium Content Vault") (part "RES"))
    )
    (comp (ref "R46")
      (value "CRCW04021M00FKED")
      (footprint "FP-CRCW0402-e3-MFG")
      (description "RES Thick Film, 1MΩ, 1%, 0.063W, 100ppm/°C, 0402")
      (fields (field (name "TOLERANCE") "1%"))
      (libsource (lib "Altium Content Vault") (part "1029c3af85768c4190bb7ad29bc67b5"))
    )
    (comp (ref "R47")
      (value "CSR1206FK12L0")
      (footprint "FP-CSR1206-IPC_B")
      (description "General Purpose Thick Film Chip Resistor, 1206, 12mΩ, 1%, 0.5W")
      (fields (field (name "TOLERANCE") "1%"))
      (libsource (lib "Altium Content Vault") (part "1029c3af85768c4190bb7ad29bc67b5"))
    )
    (comp (ref "R48")
      (value "ERJ-6ENF3242V")
      (footprint "RESC2013X70X40ML20T20")
      (fields (field (name "MANUFACTURER") "Panasonic"))
      (libsource (lib "Altium Content Vault") (part "RES"))
    )
    (comp (ref "R49")
      (value "RNCF0805BTE10K4")
      (footprint "RES_RNCF0805_STP")
      (description "No Description Available")
      (libsource (lib "RNCF0805BTE10K4") (part "RNCF0805BTE10K4"))
    )
    (comp (ref "R51")
      (value "RC0603FR-0720KL")
      (footprint "FP-RC0603-0_55-IPC_C")
      (description "RES 20K OHM 1% 1/10W 0603")
      (fields (field (name "TOLERANCE") "1%"))
      (libsource (lib "Altium Content Vault") (part "1029c3af85768c4190bb7ad29bc67b5"))
    )
    (comp (ref "R52")
      (value "RC0603FR-0710KL")
      (footprint "FP-RC0603-0_55-IPC_C")
      (description "RES 10K OHM 1% 1/10W 0603")
      (fields (field (name "TOLERANCE") "1%"))
      (libsource (lib "Altium Content Vault") (part "1029c3af85768c4190bb7ad29bc67b5"))
    )
    (comp (ref "R53")
      (value "CRCW080541K2FKEA")
      (footprint "Vishay_CRCW0805-e3_MFG")
      (fields (field (name "TOLERANCE") "1%"))
      (libsource (lib "Altium Content Vault") (part "CRCW080541K2FKEA"))
    )
    (comp (ref "R54")
      (value "ERJ-6ENF2491V")
      (footprint "RESC2013X70X40LL20T20")
      (fields (field (name "MANUFACTURER") "Panasonic"))
      (libsource (lib "Altium Content Vault") (part "RES"))
    )
    (comp (ref "R55")
      (value "CRCW04025K23FKED")
      (footprint "FP-CRCW0402-e3-IPC_C")
      (description "RES Thick Film, 5.23kΩ, 1%, 0.063W, 100ppm/°C, 0402")
      (fields (field (name "TOLERANCE") "1%"))
      (libsource (lib "Altium Content Vault") (part "1029c3af85768c4190bb7ad29bc67b5"))
    )
    (comp (ref "R56")
      (value "CRCW040247K5FKED")
      (footprint "RESC1005X40X25ML05T05")
      (fields (field (name "MANUFACTURER") "Vishay Dale"))
      (libsource (lib "Altium Content Vault") (part "RES"))
    )
    (comp (ref "R57")
      (value "CSR1206FK12L0")
      (footprint "FP-CSR1206-IPC_B")
      (description "General Purpose Thick Film Chip Resistor, 1206, 12mΩ, 1%, 0.5W")
      (fields (field (name "TOLERANCE") "1%"))
      (libsource (lib "Altium Content Vault") (part "1029c3af85768c4190bb7ad29bc67b5"))
    )
    (comp (ref "R58")
      (value "ERJ-6ENF1872V")
      (footprint "RESC2013X70X40LL20T20")
      (fields (field (name "MANUFACTURER") "Panasonic"))
      (libsource (lib "Altium Content Vault") (part "RES"))
    )
    (comp (ref "R59")
      (value "RNCF0805BTE10K4")
      (footprint "RES_RNCF0805_STP")
      (description "No Description Available")
      (libsource (lib "RNCF0805BTE10K4") (part "RNCF0805BTE10K4"))
    )
    (comp (ref "R60")
      (value "CRCW04021M00FKED")
      (footprint "FP-CRCW0402-e3-MFG")
      (description "RES Thick Film, 1MΩ, 1%, 0.063W, 100ppm/°C, 0402")
      (fields (field (name "TOLERANCE") "1%"))
      (libsource (lib "Altium Content Vault") (part "1029c3af85768c4190bb7ad29bc67b5"))
    )
    (comp (ref "RAS")
      (value "CRCW1210100KFKEA")
      (footprint "FP-CRCW1210-e3-IPC_C")
      (description "RES SMD 205K OHM 1% 1/2W 1770")
      (fields (field (name "TOLERANCE") "1%"))
      (libsource (lib "Altium Content Vault") (part "1029c3af85768c4190bb7ad29bc67b5"))
    )
    (comp (ref "RAS2")
      (value "CRCW080510K0FKEAHP")
      (footprint "RESC2013X60X40NL15T20")
      (fields (field (name "MANUFACTURER") "Vishay Dale"))
      (libsource (lib "Altium Content Vault") (part "RES"))
    )
    (comp (ref "RAS3")
      (value "CRCW1210100KFKEA")
      (footprint "FP-CRCW1210-e3-IPC_C")
      (description "RES SMD 205K OHM 1% 1/2W 1770")
      (fields (field (name "TOLERANCE") "1%"))
      (libsource (lib "Altium Content Vault") (part "1029c3af85768c4190bb7ad29bc67b5"))
    )
    (comp (ref "RAS4")
      (value "CRCW080510K0FKEAHP")
      (footprint "RESC2013X60X40NL15T20")
      (fields (field (name "MANUFACTURER") "Vishay Dale"))
      (libsource (lib "Altium Content Vault") (part "RES"))
    )
    (comp (ref "RF_LINK")
      (value "B2B-PH-K-SLFSN")
      (footprint "CONN_B2B-PH-K-SLFSN_JST")
      (description "No Description Available")
      (libsource (lib "B2B-PH-K-SLFSN") (part "B2B-PH-K-SLFSN"))
    )
    (comp (ref "RJ6")
      (value "CRCW08050000Z0EA")
      (footprint "RESC2013X50X30LL20T20")
      (fields (field (name "MANUFACTURER") "Vishay Dale"))
      (libsource (lib "Altium Content Vault") (part "RES"))
    )
    (comp (ref "RJ7")
      (value "CRCW08050000Z0EA")
      (footprint "RESC2013X50X30LL20T20")
      (fields (field (name "MANUFACTURER") "Vishay Dale"))
      (libsource (lib "Altium Content Vault") (part "RES"))
    )
    (comp (ref "RL1")
      (value "CRCW0805750RFKEA")
      (footprint "RESC2013X50X30NL20T20")
      (fields (field (name "MANUFACTURER") "Vishay Dale"))
      (libsource (lib "Altium Content Vault") (part "RES"))
    )
    (comp (ref "RL2")
      (value "CRCW0805750RFKEA")
      (footprint "RESC2013X50X30NL20T20")
      (fields (field (name "MANUFACTURER") "Vishay Dale"))
      (libsource (lib "Altium Content Vault") (part "RES"))
    )
    (comp (ref "RL3")
      (value "CRCW0805750RFKEA")
      (footprint "RESC2013X50X30NL20T20")
      (fields (field (name "MANUFACTURER") "Vishay Dale"))
      (libsource (lib "Altium Content Vault") (part "RES"))
    )
    (comp (ref "RL4")
      (value "CRCW0805750RFKEA")
      (footprint "RESC2013X50X30NL20T20")
      (fields (field (name "MANUFACTURER") "Vishay Dale"))
      (libsource (lib "Altium Content Vault") (part "RES"))
    )
    (comp (ref "RL5")
      (value "CRCW0805750RFKEA")
      (footprint "RESC2013X50X30NL20T20")
      (fields (field (name "MANUFACTURER") "Vishay Dale"))
      (libsource (lib "Altium Content Vault") (part "RES"))
    )
    (comp (ref "RL6")
      (value "CRCW0805750RFKEA")
      (footprint "RESC2013X50X30NL20T20")
      (fields (field (name "MANUFACTURER") "Vishay Dale"))
      (libsource (lib "Altium Content Vault") (part "RES"))
    )
    (comp (ref "RL7")
      (value "CRCW0805750RFKEA")
      (footprint "RESC2013X50X30NL20T20")
      (fields (field (name "MANUFACTURER") "Vishay Dale"))
      (libsource (lib "Altium Content Vault") (part "RES"))
    )
    (comp (ref "RL8")
      (value "CRCW0805750RFKEA")
      (footprint "RESC2013X50X30NL20T20")
      (fields (field (name "MANUFACTURER") "Vishay Dale"))
      (libsource (lib "Altium Content Vault") (part "RES"))
    )
    (comp (ref "RL9")
      (value "CRCW0805750RFKEA")
      (footprint "RESC2013X50X30NL20T20")
      (fields (field (name "MANUFACTURER") "Vishay Dale"))
      (libsource (lib "Altium Content Vault") (part "RES"))
    )
    (comp (ref "RM")
      (value "CRCW1210100KFKEA")
      (footprint "FP-CRCW1210-e3-IPC_C")
      (description "RES SMD 205K OHM 1% 1/2W 1770")
      (fields (field (name "TOLERANCE") "1%"))
      (libsource (lib "Altium Content Vault") (part "1029c3af85768c4190bb7ad29bc67b5"))
    )
    (comp (ref "RM2")
      (value "CRCW080510K0FKEAHP")
      (footprint "RESC2013X60X40NL15T20")
      (fields (field (name "MANUFACTURER") "Vishay Dale"))
      (libsource (lib "Altium Content Vault") (part "RES"))
    )
    (comp (ref "RM3")
      (value "CRCW1210100KFKEA")
      (footprint "FP-CRCW1210-e3-IPC_C")
      (description "RES SMD 205K OHM 1% 1/2W 1770")
      (fields (field (name "TOLERANCE") "1%"))
      (libsource (lib "Altium Content Vault") (part "1029c3af85768c4190bb7ad29bc67b5"))
    )
    (comp (ref "RM4")
      (value "CRCW080510K0FKEAHP")
      (footprint "RESC2013X60X40NL15T20")
      (fields (field (name "MANUFACTURER") "Vishay Dale"))
      (libsource (lib "Altium Content Vault") (part "RES"))
    )
    (comp (ref "servo")
      (value "1720650202")
      (footprint "CONN_SD-768290002_02_MOL")
      (description "No Description Available")
      (libsource (lib "1720650202") (part "1720650202"))
    )
    (comp (ref "servo_F")
      (value "3568")
      (footprint "FP-3568-MFG")
      (fields (field (name "VOLTAGE") "500V"))
      (libsource (lib "Altium Content Vault") (part "3568"))
    )
    (comp (ref "servo_L")
      (value "LS L29K-H1J2-1-Z")
      (footprint "FP-LS_L29K-MFG")
      (description "LED RED DIFFUSED 0603 SMD")
      (libsource (lib "Altium Content Vault") (part "8706943c75ba83719d021d2fdc84c58"))
    )
    (comp (ref "U1")
      (value "LM25116MHX/NOPB")
      (footprint "PWP0020A_N")
      (description "Wide Range Synchronous Buck Controller, 20-pin TSSOP-EP, Pb-Free")
      (fields (field (name "MANUFACTURER") "Texas Instruments"))
      (libsource (lib "Altium Content Vault") (part "PM-REG-LM25116MH-21"))
    )
    (comp (ref "U2")
      (value "LM25116MHX/NOPB")
      (footprint "PWP0020A_N")
      (description "Wide Range Synchronous Buck Controller, 20-pin TSSOP-EP, Pb-Free")
      (fields (field (name "MANUFACTURER") "Texas Instruments"))
      (libsource (lib "Altium Content Vault") (part "PM-REG-LM25116MH-21"))
    )
    (comp (ref "U2AS")
      (value "TLV271IDBVR")
      (footprint "DBV0005A_M")
      (fields (field (name "MANUFACTURER") "Texas Instruments"))
      (libsource (lib "Altium Content Vault") (part "TI-TLV2XX1DBV5"))
    )
    (comp (ref "U2_5.5")
      (value "TLV271IDBVR")
      (footprint "DBV0005A_M")
      (fields (field (name "MANUFACTURER") "Texas Instruments"))
      (libsource (lib "Altium Content Vault") (part "TI-TLV2XX1DBV5"))
    )
    (comp (ref "U2_fans")
      (value "TLV271IDBVR")
      (footprint "DBV0005A_M")
      (fields (field (name "MANUFACTURER") "Texas Instruments"))
      (libsource (lib "Altium Content Vault") (part "TI-TLV2XX1DBV5"))
    )
    (comp (ref "U2_mcm")
      (value "TLV271IDBVR")
      (footprint "DBV0005A_M")
      (fields (field (name "MANUFACTURER") "Texas Instruments"))
      (libsource (lib "Altium Content Vault") (part "TI-TLV2XX1DBV5"))
    )
    (comp (ref "U2_MD")
      (value "TLV271IDBVR")
      (footprint "DBV0005A_M")
      (fields (field (name "MANUFACTURER") "Texas Instruments"))
      (libsource (lib "Altium Content Vault") (part "TI-TLV2XX1DBV5"))
    )
    (comp (ref "U2_servo")
      (value "TLV271IDBVR")
      (footprint "DBV0005A_M")
      (fields (field (name "MANUFACTURER") "Texas Instruments"))
      (libsource (lib "Altium Content Vault") (part "TI-TLV2XX1DBV5"))
    )
    (comp (ref "U3")
      (value "LM25116MHX/NOPB")
      (footprint "PWP0020A_N")
      (description "Wide Range Synchronous Buck Controller, 20-pin TSSOP-EP, Pb-Free")
      (fields (field (name "MANUFACTURER") "Texas Instruments"))
      (libsource (lib "Altium Content Vault") (part "PM-REG-LM25116MH-21"))
    )
    (comp (ref "U3.3")
      (value "TLV271IDBVR")
      (footprint "DBV0005A_M")
      (fields (field (name "MANUFACTURER") "Texas Instruments"))
      (libsource (lib "Altium Content Vault") (part "TI-TLV2XX1DBV5"))
    )
    (comp (ref "U3.3_2")
      (value "TLV271IDBVR")
      (footprint "DBV0005A_M")
      (fields (field (name "MANUFACTURER") "Texas Instruments"))
      (libsource (lib "Altium Content Vault") (part "TI-TLV2XX1DBV5"))
    )
    (comp (ref "U3AS")
      (value "TLV271IDBVR")
      (footprint "DBV0005A_M")
      (fields (field (name "MANUFACTURER") "Texas Instruments"))
      (libsource (lib "Altium Content Vault") (part "TI-TLV2XX1DBV5"))
    )
    (comp (ref "U3_MD")
      (value "TLV271IDBVR")
      (footprint "DBV0005A_M")
      (fields (field (name "MANUFACTURER") "Texas Instruments"))
      (libsource (lib "Altium Content Vault") (part "TI-TLV2XX1DBV5"))
    )
    (comp (ref "U4")
      (value "LM25116MHX/NOPB")
      (footprint "PWP0020A_N")
      (description "Wide Range Synchronous Buck Controller, 20-pin TSSOP-EP, Pb-Free")
      (fields (field (name "MANUFACTURER") "Texas Instruments"))
      (libsource (lib "Altium Content Vault") (part "PM-REG-LM25116MH-21"))
    )
    (comp (ref "U5")
      (value "LM25116MHX/NOPB")
      (footprint "PWP0020A_N")
      (description "Wide Range Synchronous Buck Controller, 20-pin TSSOP-EP, Pb-Free")
      (fields (field (name "MANUFACTURER") "Texas Instruments"))
      (libsource (lib "Altium Content Vault") (part "PM-REG-LM25116MH-21"))
    )
    (comp (ref "U5.5")
      (value "TLV271IDBVR")
      (footprint "DBV0005A_M")
      (fields (field (name "MANUFACTURER") "Texas Instruments"))
      (libsource (lib "Altium Content Vault") (part "TI-TLV2XX1DBV5"))
    )
    (comp (ref "UA")
      (value "SN74LVC1G08DBVRG4")
      (footprint "FP-DBV0005A-IPC_A")
      (description "IC GATE AND 1CH 2-INP SOT23-5")
      (libsource (lib "Altium Content Vault") (part "01e3b9c82a35461297afe00c4ca9311"))
    )
    (comp (ref "UAS_1")
      (value "TLV271IDBVR")
      (footprint "DBV0005A_M")
      (fields (field (name "MANUFACTURER") "Texas Instruments"))
      (libsource (lib "Altium Content Vault") (part "TI-TLV2XX1DBV5"))
    )
    (comp (ref "UAS_2")
      (value "TLV271IDBVR")
      (footprint "DBV0005A_M")
      (fields (field (name "MANUFACTURER") "Texas Instruments"))
      (libsource (lib "Altium Content Vault") (part "TI-TLV2XX1DBV5"))
    )
    (comp (ref "Ufans")
      (value "TLV271IDBVR")
      (footprint "DBV0005A_M")
      (fields (field (name "MANUFACTURER") "Texas Instruments"))
      (libsource (lib "Altium Content Vault") (part "TI-TLV2XX1DBV5"))
    )
    (comp (ref "Umcm")
      (value "TLV271IDBVR")
      (footprint "DBV0005A_M")
      (fields (field (name "MANUFACTURER") "Texas Instruments"))
      (libsource (lib "Altium Content Vault") (part "TI-TLV2XX1DBV5"))
    )
    (comp (ref "UMD_1")
      (value "TLV271IDBVR")
      (footprint "DBV0005A_M")
      (fields (field (name "MANUFACTURER") "Texas Instruments"))
      (libsource (lib "Altium Content Vault") (part "TI-TLV2XX1DBV5"))
    )
    (comp (ref "UMD_2")
      (value "TLV271IDBVR")
      (footprint "DBV0005A_M")
      (fields (field (name "MANUFACTURER") "Texas Instruments"))
      (libsource (lib "Altium Content Vault") (part "TI-TLV2XX1DBV5"))
    )
    (comp (ref "Uservo")
      (value "TLV271IDBVR")
      (footprint "DBV0005A_M")
      (fields (field (name "MANUFACTURER") "Texas Instruments"))
      (libsource (lib "Altium Content Vault") (part "TI-TLV2XX1DBV5"))
    )
  )
  (nets
    (net (code "1") (name "+5") (class "Default")
      (node (ref "5V_F") (pin "2") (pinfunction "2_2") (pintype "passive"))
      (node (ref "5_E") (pin "1") (pinfunction "1_1") (pintype "passive"))
      (node (ref "5_ECB") (pin "1") (pinfunction "1_1") (pintype "passive"))
      (node (ref "5_LG") (pin "1") (pinfunction "1_1") (pintype "passive"))
      (node (ref "R52") (pin "1") (pinfunction "1_1") (pintype "passive"))
    )
    (net (code "2") (name "/3.3_Fuse") (class "Default")
      (node (ref "U3.3") (pin "1") (pinfunction "OUT_1") (pintype "output"))
      (node (ref "U3.3") (pin "4") (pinfunction "IN-_4") (pintype "input"))
      (node (ref "U3.3_2") (pin "3") (pinfunction "IN+_3") (pintype "input"))
    )
    (net (code "3") (name "/5.5_Fuse") (class "Default")
      (node (ref "U2_5.5") (pin "3") (pinfunction "IN+_3") (pintype "input"))
      (node (ref "U5.5") (pin "1") (pinfunction "OUT_1") (pintype "output"))
      (node (ref "U5.5") (pin "4") (pinfunction "IN-_4") (pintype "input"))
    )
    (net (code "4") (name "/AND_Output") (class "Default")
      (node (ref "UA") (pin "4") (pinfunction "Y_4") (pintype "output"))
    )
    (net (code "5") (name "/AS_Fuse1") (class "Default")
      (node (ref "U2AS") (pin "3") (pinfunction "IN+_3") (pintype "input"))
      (node (ref "UAS_1") (pin "1") (pinfunction "OUT_1") (pintype "output"))
      (node (ref "UAS_1") (pin "4") (pinfunction "IN-_4") (pintype "input"))
    )
    (net (code "6") (name "/AS_Fuse2") (class "Default")
      (node (ref "U3AS") (pin "3") (pinfunction "IN+_3") (pintype "input"))
      (node (ref "UAS_2") (pin "1") (pinfunction "OUT_1") (pintype "output"))
      (node (ref "UAS_2") (pin "4") (pinfunction "IN-_4") (pintype "input"))
    )
    (net (code "7") (name "/Fan_Fuse") (class "Default")
      (node (ref "U2_fans") (pin "3") (pinfunction "IN+_3") (pintype "input"))
      (node (ref "Ufans") (pin "1") (pinfunction "OUT_1") (pintype "output"))
      (node (ref "Ufans") (pin "4") (pinfunction "IN-_4") (pintype "input"))
    )
    (net (code "8") (name "/MCM_Fuse") (class "Default")
      (node (ref "U2_mcm") (pin "3") (pinfunction "IN+_3") (pintype "input"))
      (node (ref "Umcm") (pin "1") (pinfunction "OUT_1") (pintype "output"))
      (node (ref "Umcm") (pin "4") (pinfunction "IN-_4") (pintype "input"))
    )
    (net (code "9") (name "/MD_Fuse1") (class "Default")
      (node (ref "U2_MD") (pin "3") (pinfunction "IN+_3") (pintype "input"))
      (node (ref "UMD_1") (pin "1") (pinfunction "OUT_1") (pintype "output"))
      (node (ref "UMD_1") (pin "4") (pinfunction "IN-_4") (pintype "input"))
    )
    (net (code "10") (name "/MD_Fuse2") (class "Default")
      (node (ref "U3_MD") (pin "3") (pinfunction "IN+_3") (pintype "input"))
      (node (ref "UMD_2") (pin "1") (pinfunction "OUT_1") (pintype "output"))
      (node (ref "UMD_2") (pin "4") (pinfunction "IN-_4") (pintype "input"))
    )
    (net (code "11") (name "/Servo_Fuse") (class "Default")
      (node (ref "U2_servo") (pin "3") (pinfunction "IN+_3") (pintype "input"))
      (node (ref "Uservo") (pin "1") (pinfunction "OUT_1") (pintype "output"))
      (node (ref "Uservo") (pin "4") (pinfunction "IN-_4") (pintype "input"))
    )
    (net (code "12") (name "/con1_voltage") (class "Default")
      (node (ref "JR") (pin "1") (pinfunction "1_1") (pintype "passive"))
      (node (ref "K1") (pin "5") (pinfunction "5_5") (pintype "passive"))
    )
    (net (code "13") (name "/con_voltage") (class "Default")
      (node (ref "K2") (pin "5") (pinfunction "5_5") (pintype "passive"))
    )
    (net (code "14") (name "/micro_relay") (class "Default")
      (node (ref "UA") (pin "1") (pinfunction "A_1") (pintype "input"))
    )
    (net (code "15") (name "3.3+") (class "Default")
      (node (ref "Cb1") (pin "1") (pinfunction "1_1") (pintype "passive"))
      (node (ref "Cb11") (pin "1") (pinfunction "1_1") (pintype "passive"))
      (node (ref "Cb12") (pin "1") (pinfunction "1_1") (pintype "passive"))
      (node (ref "Cb13") (pin "1") (pinfunction "1_1") (pintype "passive"))
      (node (ref "Cb14") (pin "1") (pinfunction "1_1") (pintype "passive"))
      (node (ref "Cb15") (pin "1") (pinfunction "1_1") (pintype "passive"))
      (node (ref "Cb16") (pin "1") (pinfunction "1_1") (pintype "passive"))
      (node (ref "Cb17") (pin "1") (pinfunction "1_1") (pintype "passive"))
      (node (ref "Cb18") (pin "1") (pinfunction "1_1") (pintype "passive"))
      (node (ref "Cb19") (pin "1") (pinfunction "1_1") (pintype "passive"))
      (node (ref "Cb2") (pin "1") (pinfunction "1_1") (pintype "passive"))
      (node (ref "Cb3") (pin "1") (pinfunction "1_1") (pintype "passive"))
      (node (ref "Cb4") (pin "1") (pinfunction "1_1") (pintype "passive"))
      (node (ref "Cb5") (pin "1") (pinfunction "1_1") (pintype "passive"))
      (node (ref "Cb6") (pin "1") (pinfunction "1_1") (pintype "passive"))
      (node (ref "Cb7") (pin "1") (pinfunction "1_1") (pintype "passive"))
      (node (ref "Cb8") (pin "1") (pinfunction "1_1") (pintype "passive"))
      (node (ref "Cb9") (pin "1") (pinfunction "1_1") (pintype "passive"))
      (node (ref "U2AS") (pin "5") (pinfunction "VDD_5") (pintype "power_in"))
      (node (ref "U2_5.5") (pin "5") (pinfunction "VDD_5") (pintype "power_in"))
      (node (ref "U2_MD") (pin "5") (pinfunction "VDD_5") (pintype "power_in"))
      (node (ref "U2_fans") (pin "5") (pinfunction "VDD_5") (pintype "power_in"))
      (node (ref "U2_mcm") (pin "5") (pinfunction "VDD_5") (pintype "power_in"))
      (node (ref "U2_servo") (pin "5") (pinfunction "VDD_5") (pintype "power_in"))
      (node (ref "U3.3") (pin "5") (pinfunction "VDD_5") (pintype "power_in"))
      (node (ref "U3.3_2") (pin "5") (pinfunction "VDD_5") (pintype "power_in"))
      (node (ref "U3AS") (pin "5") (pinfunction "VDD_5") (pintype "power_in"))
      (node (ref "U3_MD") (pin "5") (pinfunction "VDD_5") (pintype "power_in"))
      (node (ref "U5.5") (pin "5") (pinfunction "VDD_5") (pintype "power_in"))
      (node (ref "UA") (pin "5") (pinfunction "VCC_5") (pintype "power_in"))
      (node (ref "UAS_1") (pin "5") (pinfunction "VDD_5") (pintype "power_in"))
      (node (ref "UAS_2") (pin "5") (pinfunction "VDD_5") (pintype "power_in"))
      (node (ref "UMD_1") (pin "5") (pinfunction "VDD_5") (pintype "power_in"))
      (node (ref "UMD_2") (pin "5") (pinfunction "VDD_5") (pintype "power_in"))
      (node (ref "Ufans") (pin "5") (pinfunction "VDD_5") (pintype "power_in"))
      (node (ref "Umcm") (pin "5") (pinfunction "VDD_5") (pintype "power_in"))
      (node (ref "Uservo") (pin "5") (pinfunction "VDD_5") (pintype "power_in"))
    )
    (net (code "16") (name "DGND") (class "Default")
      (node (ref "RF_LINK") (pin "2") (pinfunction "2_2") (pintype "passive"))
      (node (ref "UA") (pin "3") (pinfunction "GND_3") (pintype "power_in"))
    )
    (net (code "17") (name "GND") (class "Default")
      (node (ref "-") (pin "1") (pinfunction "1_1") (pintype "passive"))
      (node (ref "-") (pin "10") (pinfunction "10_10") (pintype "passive"))
      (node (ref "-") (pin "11") (pinfunction "11_11") (pintype "passive"))
      (node (ref "-") (pin "12") (pinfunction "12_12") (pintype "passive"))
      (node (ref "-") (pin "2") (pinfunction "2_2") (pintype "passive"))
      (node (ref "-") (pin "3") (pinfunction "3_3") (pintype "passive"))
      (node (ref "-") (pin "4") (pinfunction "4_4") (pintype "passive"))
      (node (ref "-") (pin "5") (pinfunction "5_5") (pintype "passive"))
      (node (ref "-") (pin "6") (pinfunction "6_6") (pintype "passive"))
      (node (ref "-") (pin "7") (pinfunction "7_7") (pintype "passive"))
      (node (ref "-") (pin "8") (pinfunction "8_8") (pintype "passive"))
      (node (ref "-") (pin "9") (pinfunction "9_9") (pintype "passive"))
      (node (ref "12_E") (pin "2") (pinfunction "2_2") (pintype "passive"))
      (node (ref "12_ECB") (pin "2") (pinfunction "2_2") (pintype "passive"))
      (node (ref "3.3V_L") (pin "1") (pinfunction "C_1") (pintype "passive"))
      (node (ref "3.3_E") (pin "2") (pinfunction "2_2") (pintype "passive"))
      (node (ref "3.3_LG") (pin "2") (pinfunction "2_2") (pintype "passive"))
      (node (ref "5V_L") (pin "1") (pinfunction "C_1") (pintype "passive"))
      (node (ref "5_E") (pin "2") (pinfunction "2_2") (pintype "passive"))
      (node (ref "5_ECB") (pin "2") (pinfunction "2_2") (pintype "passive"))
      (node (ref "5_LG") (pin "2") (pinfunction "2_2") (pintype "passive"))
      (node (ref "AS2_L") (pin "1") (pinfunction "C_1") (pintype "passive"))
      (node (ref "AS_1") (pin "2") (pinfunction "2_2") (pintype "passive"))
      (node (ref "AS_2") (pin "2") (pinfunction "2_2") (pintype "passive"))
      (node (ref "AS_L") (pin "1") (pinfunction "C_1") (pintype "passive"))
      (node (ref "C14") (pin "2") (pinfunction "2_2") (pintype "passive"))
      (node (ref "C15") (pin "2") (pinfunction "2_2") (pintype "passive"))
      (node (ref "C16") (pin "1") (pinfunction "1_1") (pintype "passive"))
      (node (ref "C17") (pin "2") (pinfunction "2_2") (pintype "passive"))
      (node (ref "C21") (pin "1") (pinfunction "1_1") (pintype "passive"))
      (node (ref "C22") (pin "2") (pinfunction "2_2") (pintype "passive"))
      (node (ref "C23") (pin "2") (pinfunction "2_2") (pintype "passive"))
      (node (ref "C24") (pin "2") (pinfunction "2_2") (pintype "passive"))
      (node (ref "C25") (pin "2") (pinfunction "2_2") (pintype "passive"))
      (node (ref "C26") (pin "1") (pinfunction "1_1") (pintype "passive"))
      (node (ref "C31") (pin "1") (pinfunction "1_1") (pintype "passive"))
      (node (ref "C40") (pin "2") (pinfunction "A_2") (pintype "passive"))
      (node (ref "C41") (pin "2") (pinfunction "A_2") (pintype "passive"))
      (node (ref "C42") (pin "2") (pinfunction "A_2") (pintype "passive"))
      (node (ref "C61") (pin "2") (pinfunction "2_2") (pintype "passive"))
      (node (ref "C62") (pin "2") (pinfunction "2_2") (pintype "passive"))
      (node (ref "C63") (pin "2") (pinfunction "2_2") (pintype "passive"))
      (node (ref "C64") (pin "1") (pinfunction "1_1") (pintype "passive"))
      (node (ref "C67") (pin "1") (pinfunction "1_1") (pintype "passive"))
      (node (ref "C69") (pin "2") (pinfunction "2_2") (pintype "passive"))
      (node (ref "C70") (pin "2") (pinfunction "2_2") (pintype "passive"))
      (node (ref "C71") (pin "1") (pinfunction "1_1") (pintype "passive"))
      (node (ref "C72") (pin "1") (pinfunction "1_1") (pintype "passive"))
      (node (ref "C75") (pin "1") (pinfunction "1_1") (pintype "passive"))
      (node (ref "C77") (pin "2") (pinfunction "2_2") (pintype "passive"))
      (node (ref "C78") (pin "2") (pinfunction "2_2") (pintype "passive"))
      (node (ref "C79") (pin "2") (pinfunction "2_2") (pintype "passive"))
      (node (ref "C80") (pin "2") (pinfunction "2_2") (pintype "passive"))
      (node (ref "C81") (pin "1") (pinfunction "1_1") (pintype "passive"))
      (node (ref "C84") (pin "1") (pinfunction "1_1") (pintype "passive"))
      (node (ref "C86") (pin "2") (pinfunction "2_2") (pintype "passive"))
      (node (ref "CR15") (pin "2") (pinfunction "2_2") (pintype "passive"))
      (node (ref "Cb1") (pin "2") (pinfunction "2_2") (pintype "passive"))
      (node (ref "Cb11") (pin "2") (pinfunction "2_2") (pintype "passive"))
      (node (ref "Cb12") (pin "2") (pinfunction "2_2") (pintype "passive"))
      (node (ref "Cb13") (pin "2") (pinfunction "2_2") (pintype "passive"))
      (node (ref "Cb14") (pin "2") (pinfunction "2_2") (pintype "passive"))
      (node (ref "Cb15") (pin "2") (pinfunction "2_2") (pintype "passive"))
      (node (ref "Cb16") (pin "2") (pinfunction "2_2") (pintype "passive"))
      (node (ref "Cb17") (pin "2") (pinfunction "2_2") (pintype "passive"))
      (node (ref "Cb18") (pin "2") (pinfunction "2_2") (pintype "passive"))
      (node (ref "Cb19") (pin "2") (pinfunction "2_2") (pintype "passive"))
      (node (ref "Cb2") (pin "2") (pinfunction "2_2") (pintype "passive"))
      (node (ref "Cb3") (pin "2") (pinfunction "2_2") (pintype "passive"))
      (node (ref "Cb4") (pin "2") (pinfunction "2_2") (pintype "passive"))
      (node (ref "Cb5") (pin "2") (pinfunction "2_2") (pintype "passive"))
      (node (ref "Cb6") (pin "2") (pinfunction "2_2") (pintype "passive"))
      (node (ref "Cb7") (pin "2") (pinfunction "2_2") (pintype "passive"))
      (node (ref "Cb8") (pin "2") (pinfunction "2_2") (pintype "passive"))
      (node (ref "Cb9") (pin "2") (pinfunction "2_2") (pintype "passive"))
      (node (ref "Cbp") (pin "2") (pinfunction "2_2") (pintype "passive"))
      (node (ref "Cbp2") (pin "2") (pinfunction "2_2") (pintype "passive"))
      (node (ref "Cin2") (pin "2") (pinfunction "2_2") (pintype "passive"))
      (node (ref "Cinx2") (pin "2") (pinfunction "2_2") (pintype "passive"))
      (node (ref "Fans") (pin "2") (pinfunction "2_2") (pintype "passive"))
      (node (ref "Fans_L") (pin "1") (pinfunction "C_1") (pintype "passive"))
      (node (ref "J2") (pin "2") (pinfunction "2_2") (pintype "passive"))
      (node (ref "K1") (pin "6") (pinfunction "6_6") (pintype "passive"))
      (node (ref "K2") (pin "6") (pinfunction "6_6") (pintype "passive"))
      (node (ref "MCM") (pin "2") (pinfunction "2_2") (pintype "passive"))
      (node (ref "MCM_L") (pin "1") (pinfunction "C_1") (pintype "passive"))
      (node (ref "MD_1") (pin "21") (pinfunction "21_21") (pintype "passive"))
      (node (ref "MD_1") (pin "22") (pinfunction "22_22") (pintype "passive"))
      (node (ref "MD_2") (pin "21") (pinfunction "21_21") (pintype "passive"))
      (node (ref "MD_2") (pin "22") (pinfunction "22_22") (pintype "passive"))
      (node (ref "MD_L") (pin "1") (pinfunction "C_1") (pintype "passive"))
      (node (ref "MP-") (pin "1") (pinfunction "1_1") (pintype "passive"))
      (node (ref "Motor") (pin "1") (pinfunction "C_1") (pintype "passive"))
      (node (ref "R11") (pin "2") (pinfunction "2_2") (pintype "passive"))
      (node (ref "R13") (pin "1") (pinfunction "1_1") (pintype "passive"))
      (node (ref "R14") (pin "2") (pinfunction "2_2") (pintype "passive"))
      (node (ref "R17") (pin "2") (pinfunction "2_2") (pintype "passive"))
      (node (ref "R19") (pin "1") (pinfunction "1_1") (pintype "passive"))
      (node (ref "R21") (pin "2") (pinfunction "2_2") (pintype "passive"))
      (node (ref "R23") (pin "1") (pinfunction "1_1") (pintype "passive"))
      (node (ref "R24") (pin "2") (pinfunction "2_2") (pintype "passive"))
      (node (ref "R27") (pin "2") (pinfunction "2_2") (pintype "passive"))
      (node (ref "R29") (pin "1") (pinfunction "1_1") (pintype "passive"))
      (node (ref "R3") (pin "1") (pinfunction "1_1") (pintype "passive"))
      (node (ref "R4") (pin "2") (pinfunction "2_2") (pintype "passive"))
      (node (ref "R41") (pin "2") (pinfunction "2_2") (pintype "passive"))
      (node (ref "R43") (pin "1") (pinfunction "1_1") (pintype "passive"))
      (node (ref "R44") (pin "2") (pinfunction "2_2") (pintype "passive"))
      (node (ref "R47") (pin "2") (pinfunction "2_2") (pintype "passive"))
      (node (ref "R49") (pin "1") (pinfunction "1_1") (pintype "passive"))
      (node (ref "R51") (pin "2") (pinfunction "2_2") (pintype "passive"))
      (node (ref "R54") (pin "1") (pinfunction "1_1") (pintype "passive"))
      (node (ref "R55") (pin "2") (pinfunction "2_2") (pintype "passive"))
      (node (ref "R57") (pin "2") (pinfunction "2_2") (pintype "passive"))
      (node (ref "R59") (pin "1") (pinfunction "1_1") (pintype "passive"))
      (node (ref "R6") (pin "1") (pinfunction "1_1") (pintype "passive"))
      (node (ref "R8") (pin "3") (pinfunction "3_3") (pintype "passive"))
      (node (ref "RAS2") (pin "1") (pinfunction "1_1") (pintype "passive"))
      (node (ref "RAS4") (pin "1") (pinfunction "1_1") (pintype "passive"))
      (node (ref "RM2") (pin "1") (pinfunction "1_1") (pintype "passive"))
      (node (ref "RM4") (pin "1") (pinfunction "1_1") (pintype "passive"))
      (node (ref "U1") (pin "11") (pinfunction "DEMB_11") (pintype "passive"))
      (node (ref "U1") (pin "13") (pinfunction "CSG_13") (pintype "passive"))
      (node (ref "U1") (pin "14") (pinfunction "PGND_14") (pintype "power_in"))
      (node (ref "U1") (pin "17") (pinfunction "VCCX_17") (pintype "power_in"))
      (node (ref "U1") (pin "21") (pinfunction "EP_21") (pintype "power_in"))
      (node (ref "U1") (pin "6") (pinfunction "AGND_6") (pintype "power_in"))
      (node (ref "U2") (pin "11") (pinfunction "DEMB_11") (pintype "passive"))
      (node (ref "U2") (pin "13") (pinfunction "CSG_13") (pintype "passive"))
      (node (ref "U2") (pin "14") (pinfunction "PGND_14") (pintype "power_in"))
      (node (ref "U2") (pin "17") (pinfunction "VCCX_17") (pintype "power_in"))
      (node (ref "U2") (pin "21") (pinfunction "EP_21") (pintype "power_in"))
      (node (ref "U2") (pin "6") (pinfunction "AGND_6") (pintype "power_in"))
      (node (ref "U2AS") (pin "2") (pinfunction "GND_2") (pintype "power_in"))
      (node (ref "U2_5.5") (pin "2") (pinfunction "GND_2") (pintype "power_in"))
      (node (ref "U2_MD") (pin "2") (pinfunction "GND_2") (pintype "power_in"))
      (node (ref "U2_fans") (pin "2") (pinfunction "GND_2") (pintype "power_in"))
      (node (ref "U2_mcm") (pin "2") (pinfunction "GND_2") (pintype "power_in"))
      (node (ref "U2_servo") (pin "2") (pinfunction "GND_2") (pintype "power_in"))
      (node (ref "U3") (pin "11") (pinfunction "DEMB_11") (pintype "passive"))
      (node (ref "U3") (pin "13") (pinfunction "CSG_13") (pintype "passive"))
      (node (ref "U3") (pin "14") (pinfunction "PGND_14") (pintype "power_in"))
      (node (ref "U3") (pin "17") (pinfunction "VCCX_17") (pintype "power_in"))
      (node (ref "U3") (pin "21") (pinfunction "EP_21") (pintype "power_in"))
      (node (ref "U3") (pin "6") (pinfunction "AGND_6") (pintype "power_in"))
      (node (ref "U3.3") (pin "2") (pinfunction "GND_2") (pintype "power_in"))
      (node (ref "U3.3_2") (pin "2") (pinfunction "GND_2") (pintype "power_in"))
      (node (ref "U3AS") (pin "2") (pinfunction "GND_2") (pintype "power_in"))
      (node (ref "U3_MD") (pin "2") (pinfunction "GND_2") (pintype "power_in"))
      (node (ref "U4") (pin "11") (pinfunction "DEMB_11") (pintype "passive"))
      (node (ref "U4") (pin "13") (pinfunction "CSG_13") (pintype "passive"))
      (node (ref "U4") (pin "14") (pinfunction "PGND_14") (pintype "power_in"))
      (node (ref "U4") (pin "17") (pinfunction "VCCX_17") (pintype "power_in"))
      (node (ref "U4") (pin "21") (pinfunction "EP_21") (pintype "power_in"))
      (node (ref "U4") (pin "6") (pinfunction "AGND_6") (pintype "power_in"))
      (node (ref "U5") (pin "11") (pinfunction "DEMB_11") (pintype "passive"))
      (node (ref "U5") (pin "13") (pinfunction "CSG_13") (pintype "passive"))
      (node (ref "U5") (pin "14") (pinfunction "PGND_14") (pintype "power_in"))
      (node (ref "U5") (pin "17") (pinfunction "VCCX_17") (pintype "power_in"))
      (node (ref "U5") (pin "21") (pinfunction "EP_21") (pintype "power_in"))
      (node (ref "U5") (pin "6") (pinfunction "AGND_6") (pintype "power_in"))
      (node (ref "U5.5") (pin "2") (pinfunction "GND_2") (pintype "power_in"))
      (node (ref "UAS_1") (pin "2") (pinfunction "GND_2") (pintype "power_in"))
      (node (ref "UAS_2") (pin "2") (pinfunction "GND_2") (pintype "power_in"))
      (node (ref "UMD_1") (pin "2") (pinfunction "GND_2") (pintype "power_in"))
      (node (ref "UMD_2") (pin "2") (pinfunction "GND_2") (pintype "power_in"))
      (node (ref "Ufans") (pin "2") (pinfunction "GND_2") (pintype "power_in"))
      (node (ref "Umcm") (pin "2") (pinfunction "GND_2") (pintype "power_in"))
      (node (ref "Uservo") (pin "2") (pinfunction "GND_2") (pintype "power_in"))
      (node (ref "servo") (pin "2") (pinfunction "2_2") (pintype "passive"))
      (node (ref "servo_L") (pin "1") (pinfunction "C_1") (pintype "passive"))
    )
    (net (code "18") (name "Net-(3.3V_L-A)") (class "Default")
      (node (ref "3.3V_L") (pin "2") (pinfunction "A_2") (pintype "passive"))
      (node (ref "RL1") (pin "2") (pinfunction "2_2") (pintype "passive"))
    )
    (net (code "19") (name "Net-(5V_L-A)") (class "Default")
      (node (ref "5V_L") (pin "2") (pinfunction "A_2") (pintype "passive"))
      (node (ref "RL2") (pin "2") (pinfunction "2_2") (pintype "passive"))
    )
    (net (code "20") (name "Net-(12_E-Pad1)") (class "Default")
      (node (ref "12_E") (pin "1") (pinfunction "1_1") (pintype "passive"))
      (node (ref "12_ECB") (pin "1") (pinfunction "1_1") (pintype "passive"))
      (node (ref "Fans") (pin "1") (pinfunction "1_1") (pintype "passive"))
      (node (ref "Fans_F") (pin "2") (pinfunction "2_2") (pintype "passive"))
      (node (ref "P+fans") (pin "1") (pinfunction "1_1") (pintype "passive"))
      (node (ref "P+fans") (pin "10") (pinfunction "10_10") (pintype "passive"))
      (node (ref "P+fans") (pin "11") (pinfunction "11_11") (pintype "passive"))
      (node (ref "P+fans") (pin "12") (pinfunction "12_12") (pintype "passive"))
      (node (ref "P+fans") (pin "2") (pinfunction "2_2") (pintype "passive"))
      (node (ref "P+fans") (pin "3") (pinfunction "3_3") (pintype "passive"))
      (node (ref "P+fans") (pin "4") (pinfunction "4_4") (pintype "passive"))
      (node (ref "P+fans") (pin "5") (pinfunction "5_5") (pintype "passive"))
      (node (ref "P+fans") (pin "6") (pinfunction "6_6") (pintype "passive"))
      (node (ref "P+fans") (pin "7") (pinfunction "7_7") (pintype "passive"))
      (node (ref "P+fans") (pin "8") (pinfunction "8_8") (pintype "passive"))
      (node (ref "P+fans") (pin "9") (pinfunction "9_9") (pintype "passive"))
      (node (ref "R40") (pin "1") (pinfunction "1_1") (pintype "passive"))
    )
    (net (code "21") (name "Net-(AS2_F-Pad1)") (class "Default")
      (node (ref "AS2_F") (pin "1") (pinfunction "1_1") (pintype "passive"))
      (node (ref "AS_F") (pin "1") (pinfunction "1_1") (pintype "passive"))
      (node (ref "K2") (pin "4") (pinfunction "4_4") (pintype "passive"))
      (node (ref "MD2_F") (pin "1") (pinfunction "1_1") (pintype "passive"))
      (node (ref "MD_F") (pin "1") (pinfunction "1_1") (pintype "passive"))
    )
    (net (code "22") (name "Net-(AS2_F-Pad2)") (class "Default")
      (node (ref "AS2_F") (pin "2") (pinfunction "2_2") (pintype "passive"))
      (node (ref "AS_2") (pin "1") (pinfunction "1_1") (pintype "passive"))
      (node (ref "RAS3") (pin "1") (pinfunction "1_1") (pintype "passive"))
      (node (ref "RJ6") (pin "1") (pinfunction "1_1") (pintype "passive"))
    )
    (net (code "23") (name "Net-(AS2_L-A)") (class "Default")
      (node (ref "AS2_L") (pin "2") (pinfunction "A_2") (pintype "passive"))
      (node (ref "RL6") (pin "2") (pinfunction "2_2") (pintype "passive"))
    )
    (net (code "24") (name "Net-(AS_1-Pad1)") (class "Default")
      (node (ref "AS_1") (pin "1") (pinfunction "1_1") (pintype "passive"))
      (node (ref "AS_F") (pin "2") (pinfunction "2_2") (pintype "passive"))
      (node (ref "RAS") (pin "1") (pinfunction "1_1") (pintype "passive"))
      (node (ref "RJ7") (pin "1") (pinfunction "1_1") (pintype "passive"))
    )
    (net (code "25") (name "Net-(AS_L-A)") (class "Default")
      (node (ref "AS_L") (pin "2") (pinfunction "A_2") (pintype "passive"))
      (node (ref "RL7") (pin "2") (pinfunction "2_2") (pintype "passive"))
    )
    (net (code "26") (name "Net-(C18-Pad1)") (class "Default")
      (node (ref "C18") (pin "1") (pinfunction "1_1") (pintype "passive"))
      (node (ref "R5") (pin "2") (pinfunction "2_2") (pintype "passive"))
    )
    (net (code "27") (name "Net-(C28-Pad1)") (class "Default")
      (node (ref "C28") (pin "1") (pinfunction "1_1") (pintype "passive"))
      (node (ref "R15") (pin "2") (pinfunction "2_2") (pintype "passive"))
    )
    (net (code "28") (name "Net-(C40-C)") (class "Default")
      (node (ref "C40") (pin "1") (pinfunction "C_1") (pintype "passive"))
      (node (ref "L1_2") (pin "1") (pinfunction "1_1") (pintype "passive"))
      (node (ref "MCM_F") (pin "1") (pinfunction "1_1") (pintype "passive"))
      (node (ref "R18") (pin "1") (pinfunction "1_1") (pintype "passive"))
      (node (ref "U2") (pin "10") (pinfunction "VOUT_10") (pintype "input"))
    )
    (net (code "29") (name "Net-(C41-C)") (class "Default")
      (node (ref "C41") (pin "1") (pinfunction "C_1") (pintype "passive"))
      (node (ref "C42") (pin "1") (pinfunction "C_1") (pintype "passive"))
      (node (ref "Fans_F") (pin "1") (pinfunction "1_1") (pintype "passive"))
      (node (ref "L1_3") (pin "1") (pinfunction "1_1") (pintype "passive"))
      (node (ref "R28") (pin "1") (pinfunction "1_1") (pintype "passive"))
      (node (ref "U3") (pin "10") (pinfunction "VOUT_10") (pintype "input"))
    )
    (net (code "30") (name "Net-(C65-Pad1)") (class "Default")
      (node (ref "C65") (pin "1") (pinfunction "1_1") (pintype "passive"))
      (node (ref "R25") (pin "2") (pinfunction "2_2") (pintype "passive"))
    )
    (net (code "31") (name "Net-(C74-Pad1)") (class "Default")
      (node (ref "C74") (pin "1") (pinfunction "1_1") (pintype "passive"))
      (node (ref "R45") (pin "2") (pinfunction "2_2") (pintype "passive"))
    )
    (net (code "32") (name "Net-(C82-Pad1)") (class "Default")
      (node (ref "C82") (pin "1") (pinfunction "1_1") (pintype "passive"))
      (node (ref "R56") (pin "2") (pinfunction "2_2") (pintype "passive"))
    )
    (net (code "33") (name "Net-(Cbp-Pad1)") (class "Default")
      (node (ref "Cbp") (pin "1") (pinfunction "1_1") (pintype "passive"))
      (node (ref "RJ6") (pin "2") (pinfunction "2_2") (pintype "passive"))
    )
    (net (code "34") (name "Net-(Cbp2-Pad1)") (class "Default")
      (node (ref "Cbp2") (pin "1") (pinfunction "1_1") (pintype "passive"))
      (node (ref "RJ7") (pin "2") (pinfunction "2_2") (pintype "passive"))
    )
    (net (code "35") (name "Net-(Fans_L-A)") (class "Default")
      (node (ref "Fans_L") (pin "2") (pinfunction "A_2") (pintype "passive"))
      (node (ref "RL3") (pin "2") (pinfunction "2_2") (pintype "passive"))
    )
    (net (code "36") (name "Net-(M1-D)") (class "Default")
      (node (ref "C14") (pin "1") (pinfunction "1_1") (pintype "passive"))
      (node (ref "C15") (pin "1") (pinfunction "1_1") (pintype "passive"))
      (node (ref "C61") (pin "1") (pinfunction "1_1") (pintype "passive"))
      (node (ref "C62") (pin "1") (pinfunction "1_1") (pintype "passive"))
      (node (ref "C69") (pin "1") (pinfunction "1_1") (pintype "passive"))
      (node (ref "C70") (pin "1") (pinfunction "1_1") (pintype "passive"))
      (node (ref "C78") (pin "1") (pinfunction "1_1") (pintype "passive"))
      (node (ref "C79") (pin "1") (pinfunction "1_1") (pintype "passive"))
      (node (ref "Cin2") (pin "1") (pinfunction "1_1") (pintype "passive"))
      (node (ref "Cinx2") (pin "1") (pinfunction "1_1") (pintype "passive"))
      (node (ref "K1") (pin "4") (pinfunction "4_4") (pintype "passive"))
      (node (ref "M1") (pin "5-6-7-8") (pinfunction "D_5-6-7-8") (pintype "passive"))
      (node (ref "M1_2") (pin "5-6-7-8") (pinfunction "D_5-6-7-8") (pintype "passive"))
      (node (ref "M1_3") (pin "5-6-7-8") (pinfunction "D_5-6-7-8") (pintype "passive"))
      (node (ref "Q1") (pin "5-6-7-8") (pinfunction "D_5-6-7-8") (pintype "passive"))
      (node (ref "Q3") (pin "5-6-7-8") (pinfunction "D_5-6-7-8") (pintype "passive"))
      (node (ref "Q5") (pin "5-6-7-8") (pinfunction "D_5-6-7-8") (pintype "passive"))
      (node (ref "R1") (pin "1") (pinfunction "1_1") (pintype "passive"))
      (node (ref "R12") (pin "1") (pinfunction "1_1") (pintype "passive"))
      (node (ref "R16") (pin "1") (pinfunction "1_1") (pintype "passive"))
      (node (ref "R2") (pin "1") (pinfunction "1_1") (pintype "passive"))
      (node (ref "R22") (pin "1") (pinfunction "1_1") (pintype "passive"))
      (node (ref "R26") (pin "1") (pinfunction "1_1") (pintype "passive"))
      (node (ref "R42") (pin "1") (pinfunction "1_1") (pintype "passive"))
      (node (ref "R46") (pin "1") (pinfunction "1_1") (pintype "passive"))
      (node (ref "R53") (pin "1") (pinfunction "1_1") (pintype "passive"))
      (node (ref "R60") (pin "1") (pinfunction "1_1") (pintype "passive"))
      (node (ref "U1") (pin "1") (pinfunction "VIN_1") (pintype "power_in"))
      (node (ref "U2") (pin "1") (pinfunction "VIN_1") (pintype "power_in"))
      (node (ref "U3") (pin "1") (pinfunction "VIN_1") (pintype "power_in"))
      (node (ref "U4") (pin "1") (pinfunction "VIN_1") (pintype "power_in"))
      (node (ref "U5") (pin "1") (pinfunction "VIN_1") (pintype "power_in"))
    )
    (net (code "37") (name "Net-(M1-G)") (class "Default")
      (node (ref "M1") (pin "4") (pinfunction "G_4") (pintype "passive"))
      (node (ref "M1_2") (pin "4") (pinfunction "G_4") (pintype "passive"))
      (node (ref "U1") (pin "19") (pinfunction "HO_19") (pintype "output"))
    )
    (net (code "38") (name "Net-(M1_3-G)") (class "Default")
      (node (ref "M1_3") (pin "4") (pinfunction "G_4") (pintype "passive"))
      (node (ref "U2") (pin "19") (pinfunction "HO_19") (pintype "output"))
    )
    (net (code "39") (name "Net-(M1_4-D)") (class "Default")
      (node (ref "C30") (pin "1") (pinfunction "1_1") (pintype "passive"))
      (node (ref "L1_2") (pin "2") (pinfunction "2_2") (pintype "passive"))
      (node (ref "M1_3") (pin "1") (pinfunction "S_1") (pintype "passive"))
      (node (ref "M1_3") (pin "2") (pinfunction "S_2") (pintype "passive"))
      (node (ref "M1_3") (pin "3") (pinfunction "S_3") (pintype "passive"))
      (node (ref "M1_4") (pin "5-6-7-8") (pinfunction "D_5-6-7-8") (pintype "passive"))
      (node (ref "U2") (pin "20") (pinfunction "SW_20") (pintype "power_in"))
    )
    (net (code "40") (name "Net-(M1_4-G)") (class "Default")
      (node (ref "M1_4") (pin "4") (pinfunction "G_4") (pintype "passive"))
      (node (ref "U2") (pin "15") (pinfunction "LO_15") (pintype "output"))
    )
    (net (code "41") (name "Net-(M2-Gate)") (class "Default")
      (node (ref "M2") (pin "4") (pinfunction "Gate_4") (pintype "passive"))
      (node (ref "U1") (pin "15") (pinfunction "LO_15") (pintype "output"))
    )
    (net (code "42") (name "Net-(MCM-Pad1)") (class "Default")
      (node (ref "MCM") (pin "1") (pinfunction "1_1") (pintype "passive"))
      (node (ref "MCM_F") (pin "2") (pinfunction "2_2") (pintype "passive"))
      (node (ref "R20") (pin "1") (pinfunction "1_1") (pintype "passive"))
    )
    (net (code "43") (name "Net-(MCM_L-A)") (class "Default")
      (node (ref "MCM_L") (pin "2") (pinfunction "A_2") (pintype "passive"))
      (node (ref "RL4") (pin "2") (pinfunction "2_2") (pintype "passive"))
    )
    (net (code "44") (name "Net-(MD2_F-Pad2)") (class "Default")
      (node (ref "MD2_F") (pin "2") (pinfunction "2_2") (pintype "passive"))
      (node (ref "MD_2") (pin "11") (pinfunction "11_11") (pintype "passive"))
      (node (ref "MD_2") (pin "12") (pinfunction "12_12") (pintype "passive"))
      (node (ref "RM3") (pin "1") (pinfunction "1_1") (pintype "passive"))
    )
    (net (code "45") (name "Net-(MD_1-Pad11)") (class "Default")
      (node (ref "MD_1") (pin "11") (pinfunction "11_11") (pintype "passive"))
      (node (ref "MD_1") (pin "12") (pinfunction "12_12") (pintype "passive"))
      (node (ref "MD_F") (pin "2") (pinfunction "2_2") (pintype "passive"))
      (node (ref "RM") (pin "1") (pinfunction "1_1") (pintype "passive"))
    )
    (net (code "46") (name "Net-(MD_L-A)") (class "Default")
      (node (ref "MD_L") (pin "2") (pinfunction "A_2") (pintype "passive"))
      (node (ref "RL9") (pin "2") (pinfunction "2_2") (pintype "passive"))
    )
    (net (code "47") (name "Net-(Motor-A)") (class "Default")
      (node (ref "Motor") (pin "2") (pinfunction "A_2") (pintype "passive"))
      (node (ref "RL8") (pin "2") (pinfunction "2_2") (pintype "passive"))
    )
    (net (code "48") (name "Net-(Q1-G)") (class "Default")
      (node (ref "Q1") (pin "4") (pinfunction "G_4") (pintype "passive"))
      (node (ref "U3") (pin "19") (pinfunction "HO_19") (pintype "output"))
    )
    (net (code "49") (name "Net-(Q2-D)") (class "Default")
      (node (ref "C68") (pin "1") (pinfunction "1_1") (pintype "passive"))
      (node (ref "L1_3") (pin "2") (pinfunction "2_2") (pintype "passive"))
      (node (ref "Q1") (pin "1") (pinfunction "S_1") (pintype "passive"))
      (node (ref "Q1") (pin "2") (pinfunction "S_2") (pintype "passive"))
      (node (ref "Q1") (pin "3") (pinfunction "S_3") (pintype "passive"))
      (node (ref "Q2") (pin "5-6-7-8") (pinfunction "D_5-6-7-8") (pintype "passive"))
      (node (ref "U3") (pin "20") (pinfunction "SW_20") (pintype "power_in"))
    )
    (net (code "50") (name "Net-(Q2-G)") (class "Default")
      (node (ref "Q2") (pin "4") (pinfunction "G_4") (pintype "passive"))
      (node (ref "U3") (pin "15") (pinfunction "LO_15") (pintype "output"))
    )
    (net (code "51") (name "Net-(Q3-G)") (class "Default")
      (node (ref "Q3") (pin "4") (pinfunction "G_4") (pintype "passive"))
      (node (ref "U4") (pin "19") (pinfunction "HO_19") (pintype "output"))
    )
    (net (code "52") (name "Net-(Q4-D)") (class "Default")
      (node (ref "C76") (pin "1") (pinfunction "1_1") (pintype "passive"))
      (node (ref "L1_4") (pin "2") (pinfunction "2_2") (pintype "passive"))
      (node (ref "Q3") (pin "1") (pinfunction "S_1") (pintype "passive"))
      (node (ref "Q3") (pin "2") (pinfunction "S_2") (pintype "passive"))
      (node (ref "Q3") (pin "3") (pinfunction "S_3") (pintype "passive"))
      (node (ref "Q4") (pin "5-6-7-8") (pinfunction "D_5-6-7-8") (pintype "passive"))
      (node (ref "U4") (pin "20") (pinfunction "SW_20") (pintype "power_in"))
    )
    (net (code "53") (name "Net-(Q4-G)") (class "Default")
      (node (ref "Q4") (pin "4") (pinfunction "G_4") (pintype "passive"))
      (node (ref "U4") (pin "15") (pinfunction "LO_15") (pintype "output"))
    )
    (net (code "54") (name "Net-(Q5-G)") (class "Default")
      (node (ref "Q5") (pin "4") (pinfunction "G_4") (pintype "passive"))
      (node (ref "U5") (pin "19") (pinfunction "HO_19") (pintype "output"))
    )
    (net (code "55") (name "Net-(Q6-D)") (class "Default")
      (node (ref "C85") (pin "1") (pinfunction "1_1") (pintype "passive"))
      (node (ref "L1_5") (pin "1") (pinfunction "1_1") (pintype "passive"))
      (node (ref "Q5") (pin "1") (pinfunction "S_1") (pintype "passive"))
      (node (ref "Q5") (pin "2") (pinfunction "S_2") (pintype "passive"))
      (node (ref "Q5") (pin "3") (pinfunction "S_3") (pintype "passive"))
      (node (ref "Q6") (pin "5-6-7-8") (pinfunction "D_5-6-7-8") (pintype "passive"))
      (node (ref "U5") (pin "20") (pinfunction "SW_20") (pintype "power_in"))
    )
    (net (code "56") (name "Net-(Q6-G)") (class "Default")
      (node (ref "Q6") (pin "4") (pinfunction "G_4") (pintype "passive"))
      (node (ref "U5") (pin "15") (pinfunction "LO_15") (pintype "output"))
    )
    (net (code "57") (name "Net-(R9-Pad1)") (class "Default")
      (node (ref "R9") (pin "1") (pinfunction "1_1") (pintype "passive"))
      (node (ref "servo") (pin "1") (pinfunction "1_1") (pintype "passive"))
      (node (ref "servo_F") (pin "2") (pinfunction "2_2") (pintype "passive"))
    )
    (net (code "58") (name "Net-(U1-COMP)") (class "Default")
      (node (ref "C18") (pin "2") (pinfunction "2_2") (pintype "passive"))
      (node (ref "C19") (pin "1") (pinfunction "1_1") (pintype "passive"))
      (node (ref "U1") (pin "9") (pinfunction "COMP_9") (pintype "output"))
    )
    (net (code "59") (name "Net-(U1-CS)") (class "Default")
      (node (ref "M2") (pin "1") (pinfunction "Source_1") (pintype "passive"))
      (node (ref "M2") (pin "2") (pinfunction "Source_2") (pintype "passive"))
      (node (ref "M2") (pin "3") (pinfunction "Source_3") (pintype "passive"))
      (node (ref "R6") (pin "2") (pinfunction "2_2") (pintype "passive"))
      (node (ref "U1") (pin "12") (pinfunction "CS_12") (pintype "input"))
    )
    (net (code "60") (name "Net-(U1-EN)") (class "Default")
      (node (ref "R1") (pin "2") (pinfunction "2_2") (pintype "passive"))
      (node (ref "U1") (pin "4") (pinfunction "EN_4") (pintype "input"))
    )
    (net (code "61") (name "Net-(U1-FB)") (class "Default")
      (node (ref "C19") (pin "2") (pinfunction "2_2") (pintype "passive"))
      (node (ref "J2") (pin "1") (pinfunction "1_1") (pintype "passive"))
      (node (ref "R5") (pin "1") (pinfunction "1_1") (pintype "passive"))
      (node (ref "R7") (pin "2") (pinfunction "2_2") (pintype "passive"))
      (node (ref "R8") (pin "2") (pinfunction "2_2") (pintype "passive"))
      (node (ref "U1") (pin "8") (pinfunction "FB_8") (pintype "input"))
    )
    (net (code "62") (name "Net-(U1-HB)") (class "Default")
      (node (ref "C20") (pin "2") (pinfunction "2_2") (pintype "passive"))
      (node (ref "D1") (pin "1") (pinfunction "1_1") (pintype "passive"))
      (node (ref "U1") (pin "18") (pinfunction "HB_18") (pintype "passive"))
    )
    (net (code "63") (name "Net-(U1-RAMP)") (class "Default")
      (node (ref "C16") (pin "2") (pinfunction "2_2") (pintype "passive"))
      (node (ref "U1") (pin "5") (pinfunction "RAMP_5") (pintype "input"))
    )
    (net (code "64") (name "Net-(U1-RT{slash}SYNC)") (class "Default")
      (node (ref "R4") (pin "1") (pinfunction "1_1") (pintype "passive"))
      (node (ref "U1") (pin "3") (pinfunction "RT/SYNC_3") (pintype "input"))
    )
    (net (code "65") (name "Net-(U1-SS)") (class "Default")
      (node (ref "C17") (pin "1") (pinfunction "1_1") (pintype "passive"))
      (node (ref "U1") (pin "7") (pinfunction "SS_7") (pintype "input"))
    )
    (net (code "66") (name "Net-(U1-SW)") (class "Default")
      (node (ref "C20") (pin "1") (pinfunction "1_1") (pintype "passive"))
      (node (ref "L1") (pin "2") (pinfunction "2_2") (pintype "passive"))
      (node (ref "M1") (pin "1") (pinfunction "S_1") (pintype "passive"))
      (node (ref "M1") (pin "2") (pinfunction "S_2") (pintype "passive"))
      (node (ref "M1") (pin "3") (pinfunction "S_3") (pintype "passive"))
      (node (ref "M1_2") (pin "1") (pinfunction "S_1") (pintype "passive"))
      (node (ref "M1_2") (pin "2") (pinfunction "S_2") (pintype "passive"))
      (node (ref "M1_2") (pin "3") (pinfunction "S_3") (pintype "passive"))
      (node (ref "M2") (pin "5") (pinfunction "Drain_5") (pintype "passive"))
      (node (ref "M2") (pin "6") (pinfunction "Drain_6") (pintype "passive"))
      (node (ref "M2") (pin "7") (pinfunction "Drain_7") (pintype "passive"))
      (node (ref "M2") (pin "8") (pinfunction "Drain_8") (pintype "passive"))
      (node (ref "M2") (pin "9") (pinfunction "Drain_9") (pintype "passive"))
      (node (ref "U1") (pin "20") (pinfunction "SW_20") (pintype "power_in"))
    )
    (net (code "67") (name "Net-(U1-ULVO)") (class "Default")
      (node (ref "R2") (pin "2") (pinfunction "2_2") (pintype "passive"))
      (node (ref "R3") (pin "2") (pinfunction "2_2") (pintype "passive"))
      (node (ref "U1") (pin "2") (pinfunction "ULVO_2") (pintype "input"))
    )
    (net (code "68") (name "Net-(U1-VCC)") (class "Default")
      (node (ref "C21") (pin "2") (pinfunction "2_2") (pintype "passive"))
      (node (ref "D1") (pin "2") (pinfunction "2_2") (pintype "passive"))
      (node (ref "U1") (pin "16") (pinfunction "VCC_16") (pintype "power_in"))
    )
    (net (code "69") (name "Net-(U1-VOUT)") (class "Default")
      (node (ref "C22") (pin "1") (pinfunction "1_1") (pintype "passive"))
      (node (ref "C23") (pin "1") (pinfunction "1_1") (pintype "passive"))
      (node (ref "C24") (pin "1") (pinfunction "1_1") (pintype "passive"))
      (node (ref "L1") (pin "1") (pinfunction "1_1") (pintype "passive"))
      (node (ref "R7") (pin "1") (pinfunction "1_1") (pintype "passive"))
      (node (ref "U1") (pin "10") (pinfunction "VOUT_10") (pintype "input"))
      (node (ref "servo_F") (pin "1") (pinfunction "1_1") (pintype "passive"))
    )
    (net (code "70") (name "Net-(U2-COMP)") (class "Default")
      (node (ref "C27") (pin "1") (pinfunction "1_1") (pintype "passive"))
      (node (ref "C28") (pin "2") (pinfunction "2_2") (pintype "passive"))
      (node (ref "U2") (pin "9") (pinfunction "COMP_9") (pintype "output"))
    )
    (net (code "71") (name "Net-(U2-CS)") (class "Default")
      (node (ref "M1_4") (pin "1") (pinfunction "S_1") (pintype "passive"))
      (node (ref "M1_4") (pin "2") (pinfunction "S_2") (pintype "passive"))
      (node (ref "M1_4") (pin "3") (pinfunction "S_3") (pintype "passive"))
      (node (ref "R17") (pin "1") (pinfunction "1_1") (pintype "passive"))
      (node (ref "U2") (pin "12") (pinfunction "CS_12") (pintype "input"))
    )
    (net (code "72") (name "Net-(U2-EN)") (class "Default")
      (node (ref "R16") (pin "2") (pinfunction "2_2") (pintype "passive"))
      (node (ref "U2") (pin "4") (pinfunction "EN_4") (pintype "input"))
    )
    (net (code "73") (name "Net-(U2-FB)") (class "Default")
      (node (ref "C27") (pin "2") (pinfunction "2_2") (pintype "passive"))
      (node (ref "R15") (pin "1") (pinfunction "1_1") (pintype "passive"))
      (node (ref "R18") (pin "2") (pinfunction "2_2") (pintype "passive"))
      (node (ref "R19") (pin "2") (pinfunction "2_2") (pintype "passive"))
      (node (ref "U2") (pin "8") (pinfunction "FB_8") (pintype "input"))
    )
    (net (code "74") (name "Net-(U2-HB)") (class "Default")
      (node (ref "C30") (pin "2") (pinfunction "2_2") (pintype "passive"))
      (node (ref "D2") (pin "1") (pinfunction "1_1") (pintype "passive"))
      (node (ref "U2") (pin "18") (pinfunction "HB_18") (pintype "passive"))
    )
    (net (code "75") (name "Net-(U2-RAMP)") (class "Default")
      (node (ref "C25") (pin "1") (pinfunction "1_1") (pintype "passive"))
      (node (ref "U2") (pin "5") (pinfunction "RAMP_5") (pintype "input"))
    )
    (net (code "76") (name "Net-(U2-RT{slash}SYNC)") (class "Default")
      (node (ref "R14") (pin "1") (pinfunction "1_1") (pintype "passive"))
      (node (ref "U2") (pin "3") (pinfunction "RT/SYNC_3") (pintype "input"))
    )
    (net (code "77") (name "Net-(U2-SS)") (class "Default")
      (node (ref "C26") (pin "2") (pinfunction "2_2") (pintype "passive"))
      (node (ref "U2") (pin "7") (pinfunction "SS_7") (pintype "input"))
    )
    (net (code "78") (name "Net-(U2-ULVO)") (class "Default")
      (node (ref "R12") (pin "2") (pinfunction "2_2") (pintype "passive"))
      (node (ref "R13") (pin "2") (pinfunction "2_2") (pintype "passive"))
      (node (ref "U2") (pin "2") (pinfunction "ULVO_2") (pintype "input"))
    )
    (net (code "79") (name "Net-(U2-VCC)") (class "Default")
      (node (ref "C31") (pin "2") (pinfunction "2_2") (pintype "passive"))
      (node (ref "D2") (pin "2") (pinfunction "2_2") (pintype "passive"))
      (node (ref "U2") (pin "16") (pinfunction "VCC_16") (pintype "power_in"))
    )
    (net (code "80") (name "Net-(U2AS-IN-)") (class "Default")
      (node (ref "RL7") (pin "1") (pinfunction "1_1") (pintype "passive"))
      (node (ref "U2AS") (pin "1") (pinfunction "OUT_1") (pintype "output"))
      (node (ref "U2AS") (pin "4") (pinfunction "IN-_4") (pintype "input"))
    )
    (net (code "81") (name "Net-(U2_5.5-IN-)") (class "Default")
      (node (ref "RL2") (pin "1") (pinfunction "1_1") (pintype "passive"))
      (node (ref "U2_5.5") (pin "1") (pinfunction "OUT_1") (pintype "output"))
      (node (ref "U2_5.5") (pin "4") (pinfunction "IN-_4") (pintype "input"))
    )
    (net (code "82") (name "Net-(U2_MD-IN-)") (class "Default")
      (node (ref "RL9") (pin "1") (pinfunction "1_1") (pintype "passive"))
      (node (ref "U2_MD") (pin "1") (pinfunction "OUT_1") (pintype "output"))
      (node (ref "U2_MD") (pin "4") (pinfunction "IN-_4") (pintype "input"))
    )
    (net (code "83") (name "Net-(U2_fans-IN-)") (class "Default")
      (node (ref "RL3") (pin "1") (pinfunction "1_1") (pintype "passive"))
      (node (ref "U2_fans") (pin "1") (pinfunction "OUT_1") (pintype "output"))
      (node (ref "U2_fans") (pin "4") (pinfunction "IN-_4") (pintype "input"))
    )
    (net (code "84") (name "Net-(U2_mcm-IN-)") (class "Default")
      (node (ref "RL4") (pin "1") (pinfunction "1_1") (pintype "passive"))
      (node (ref "U2_mcm") (pin "1") (pinfunction "OUT_1") (pintype "output"))
      (node (ref "U2_mcm") (pin "4") (pinfunction "IN-_4") (pintype "input"))
    )
    (net (code "85") (name "Net-(U2_servo-IN-)") (class "Default")
      (node (ref "RL5") (pin "1") (pinfunction "1_1") (pintype "passive"))
      (node (ref "U2_servo") (pin "1") (pinfunction "OUT_1") (pintype "output"))
      (node (ref "U2_servo") (pin "4") (pinfunction "IN-_4") (pintype "input"))
    )
    (net (code "86") (name "Net-(U3-COMP)") (class "Default")
      (node (ref "C65") (pin "2") (pinfunction "2_2") (pintype "passive"))
      (node (ref "C66") (pin "1") (pinfunction "1_1") (pintype "passive"))
      (node (ref "U3") (pin "9") (pinfunction "COMP_9") (pintype "output"))
    )
    (net (code "87") (name "Net-(U3-CS)") (class "Default")
      (node (ref "Q2") (pin "1") (pinfunction "S_1") (pintype "passive"))
      (node (ref "Q2") (pin "2") (pinfunction "S_2") (pintype "passive"))
      (node (ref "Q2") (pin "3") (pinfunction "S_3") (pintype "passive"))
      (node (ref "R27") (pin "1") (pinfunction "1_1") (pintype "passive"))
      (node (ref "U3") (pin "12") (pinfunction "CS_12") (pintype "input"))
    )
    (net (code "88") (name "Net-(U3-EN)") (class "Default")
      (node (ref "R26") (pin "2") (pinfunction "2_2") (pintype "passive"))
      (node (ref "U3") (pin "4") (pinfunction "EN_4") (pintype "input"))
    )
    (net (code "89") (name "Net-(U3-FB)") (class "Default")
      (node (ref "C66") (pin "2") (pinfunction "2_2") (pintype "passive"))
      (node (ref "R25") (pin "1") (pinfunction "1_1") (pintype "passive"))
      (node (ref "R28") (pin "2") (pinfunction "2_2") (pintype "passive"))
      (node (ref "R29") (pin "2") (pinfunction "2_2") (pintype "passive"))
      (node (ref "U3") (pin "8") (pinfunction "FB_8") (pintype "input"))
    )
    (net (code "90") (name "Net-(U3-HB)") (class "Default")
      (node (ref "C68") (pin "2") (pinfunction "2_2") (pintype "passive"))
      (node (ref "D3") (pin "1") (pinfunction "1_1") (pintype "passive"))
      (node (ref "U3") (pin "18") (pinfunction "HB_18") (pintype "passive"))
    )
    (net (code "91") (name "Net-(U3-RAMP)") (class "Default")
      (node (ref "C63") (pin "1") (pinfunction "1_1") (pintype "passive"))
      (node (ref "U3") (pin "5") (pinfunction "RAMP_5") (pintype "input"))
    )
    (net (code "92") (name "Net-(U3-RT{slash}SYNC)") (class "Default")
      (node (ref "R24") (pin "1") (pinfunction "1_1") (pintype "passive"))
      (node (ref "U3") (pin "3") (pinfunction "RT/SYNC_3") (pintype "input"))
    )
    (net (code "93") (name "Net-(U3-SS)") (class "Default")
      (node (ref "C64") (pin "2") (pinfunction "2_2") (pintype "passive"))
      (node (ref "U3") (pin "7") (pinfunction "SS_7") (pintype "input"))
    )
    (net (code "94") (name "Net-(U3-ULVO)") (class "Default")
      (node (ref "R22") (pin "2") (pinfunction "2_2") (pintype "passive"))
      (node (ref "R23") (pin "2") (pinfunction "2_2") (pintype "passive"))
      (node (ref "U3") (pin "2") (pinfunction "ULVO_2") (pintype "input"))
    )
    (net (code "95") (name "Net-(U3-VCC)") (class "Default")
      (node (ref "C67") (pin "2") (pinfunction "2_2") (pintype "passive"))
      (node (ref "D3") (pin "2") (pinfunction "2_2") (pintype "passive"))
      (node (ref "U3") (pin "16") (pinfunction "VCC_16") (pintype "power_in"))
    )
    (net (code "96") (name "Net-(U3.3-IN+)") (class "Default")
      (node (ref "3.3V_F") (pin "2") (pinfunction "2_2") (pintype "passive"))
      (node (ref "3.3_E") (pin "1") (pinfunction "1_1") (pintype "passive"))
      (node (ref "3.3_LG") (pin "1") (pinfunction "1_1") (pintype "passive"))
      (node (ref "U3.3") (pin "3") (pinfunction "IN+_3") (pintype "input"))
    )
    (net (code "97") (name "Net-(U3.3_2-IN-)") (class "Default")
      (node (ref "RL1") (pin "1") (pinfunction "1_1") (pintype "passive"))
      (node (ref "U3.3_2") (pin "1") (pinfunction "OUT_1") (pintype "output"))
      (node (ref "U3.3_2") (pin "4") (pinfunction "IN-_4") (pintype "input"))
    )
    (net (code "98") (name "Net-(U3AS-IN-)") (class "Default")
      (node (ref "RL6") (pin "1") (pinfunction "1_1") (pintype "passive"))
      (node (ref "U3AS") (pin "1") (pinfunction "OUT_1") (pintype "output"))
      (node (ref "U3AS") (pin "4") (pinfunction "IN-_4") (pintype "input"))
    )
    (net (code "99") (name "Net-(U3_MD-IN-)") (class "Default")
      (node (ref "RL8") (pin "1") (pinfunction "1_1") (pintype "passive"))
      (node (ref "U3_MD") (pin "1") (pinfunction "OUT_1") (pintype "output"))
      (node (ref "U3_MD") (pin "4") (pinfunction "IN-_4") (pintype "input"))
    )
    (net (code "100") (name "Net-(U4-COMP)") (class "Default")
      (node (ref "C73") (pin "2") (pinfunction "2_2") (pintype "passive"))
      (node (ref "C74") (pin "2") (pinfunction "2_2") (pintype "passive"))
      (node (ref "U4") (pin "9") (pinfunction "COMP_9") (pintype "output"))
    )
    (net (code "101") (name "Net-(U4-CS)") (class "Default")
      (node (ref "Q4") (pin "1") (pinfunction "S_1") (pintype "passive"))
      (node (ref "Q4") (pin "2") (pinfunction "S_2") (pintype "passive"))
      (node (ref "Q4") (pin "3") (pinfunction "S_3") (pintype "passive"))
      (node (ref "R47") (pin "1") (pinfunction "1_1") (pintype "passive"))
      (node (ref "U4") (pin "12") (pinfunction "CS_12") (pintype "input"))
    )
    (net (code "102") (name "Net-(U4-EN)") (class "Default")
      (node (ref "R46") (pin "2") (pinfunction "2_2") (pintype "passive"))
      (node (ref "U4") (pin "4") (pinfunction "EN_4") (pintype "input"))
    )
    (net (code "103") (name "Net-(U4-FB)") (class "Default")
      (node (ref "C73") (pin "1") (pinfunction "1_1") (pintype "passive"))
      (node (ref "R45") (pin "1") (pinfunction "1_1") (pintype "passive"))
      (node (ref "R48") (pin "1") (pinfunction "1_1") (pintype "passive"))
      (node (ref "R49") (pin "2") (pinfunction "2_2") (pintype "passive"))
      (node (ref "U4") (pin "8") (pinfunction "FB_8") (pintype "input"))
    )
    (net (code "104") (name "Net-(U4-HB)") (class "Default")
      (node (ref "C76") (pin "2") (pinfunction "2_2") (pintype "passive"))
      (node (ref "D4") (pin "1") (pinfunction "1_1") (pintype "passive"))
      (node (ref "U4") (pin "18") (pinfunction "HB_18") (pintype "passive"))
    )
    (net (code "105") (name "Net-(U4-RAMP)") (class "Default")
      (node (ref "C71") (pin "2") (pinfunction "2_2") (pintype "passive"))
      (node (ref "U4") (pin "5") (pinfunction "RAMP_5") (pintype "input"))
    )
    (net (code "106") (name "Net-(U4-RT{slash}SYNC)") (class "Default")
      (node (ref "R44") (pin "1") (pinfunction "1_1") (pintype "passive"))
      (node (ref "U4") (pin "3") (pinfunction "RT/SYNC_3") (pintype "input"))
    )
    (net (code "107") (name "Net-(U4-SS)") (class "Default")
      (node (ref "C72") (pin "2") (pinfunction "2_2") (pintype "passive"))
      (node (ref "U4") (pin "7") (pinfunction "SS_7") (pintype "input"))
    )
    (net (code "108") (name "Net-(U4-ULVO)") (class "Default")
      (node (ref "R42") (pin "2") (pinfunction "2_2") (pintype "passive"))
      (node (ref "R43") (pin "2") (pinfunction "2_2") (pintype "passive"))
      (node (ref "U4") (pin "2") (pinfunction "ULVO_2") (pintype "input"))
    )
    (net (code "109") (name "Net-(U4-VCC)") (class "Default")
      (node (ref "C75") (pin "2") (pinfunction "2_2") (pintype "passive"))
      (node (ref "D4") (pin "2") (pinfunction "2_2") (pintype "passive"))
      (node (ref "U4") (pin "16") (pinfunction "VCC_16") (pintype "power_in"))
    )
    (net (code "110") (name "Net-(U4-VOUT)") (class "Default")
      (node (ref "5V_F") (pin "1") (pinfunction "1_1") (pintype "passive"))
      (node (ref "C77") (pin "1") (pinfunction "1_1") (pintype "passive"))
      (node (ref "L1_4") (pin "1") (pinfunction "1_1") (pintype "passive"))
      (node (ref "R48") (pin "2") (pinfunction "2_2") (pintype "passive"))
      (node (ref "U4") (pin "10") (pinfunction "VOUT_10") (pintype "input"))
    )
    (net (code "111") (name "Net-(U5-COMP)") (class "Default")
      (node (ref "C82") (pin "2") (pinfunction "2_2") (pintype "passive"))
      (node (ref "C83") (pin "2") (pinfunction "2_2") (pintype "passive"))
      (node (ref "U5") (pin "9") (pinfunction "COMP_9") (pintype "output"))
    )
    (net (code "112") (name "Net-(U5-CS)") (class "Default")
      (node (ref "Q6") (pin "1") (pinfunction "S_1") (pintype "passive"))
      (node (ref "Q6") (pin "2") (pinfunction "S_2") (pintype "passive"))
      (node (ref "Q6") (pin "3") (pinfunction "S_3") (pintype "passive"))
      (node (ref "R57") (pin "1") (pinfunction "1_1") (pintype "passive"))
      (node (ref "U5") (pin "12") (pinfunction "CS_12") (pintype "input"))
    )
    (net (code "113") (name "Net-(U5-EN)") (class "Default")
      (node (ref "R60") (pin "2") (pinfunction "2_2") (pintype "passive"))
      (node (ref "U5") (pin "4") (pinfunction "EN_4") (pintype "input"))
    )
    (net (code "114") (name "Net-(U5-FB)") (class "Default")
      (node (ref "C83") (pin "1") (pinfunction "1_1") (pintype "passive"))
      (node (ref "R56") (pin "1") (pinfunction "1_1") (pintype "passive"))
      (node (ref "R58") (pin "1") (pinfunction "1_1") (pintype "passive"))
      (node (ref "R59") (pin "2") (pinfunction "2_2") (pintype "passive"))
      (node (ref "U5") (pin "8") (pinfunction "FB_8") (pintype "input"))
    )
    (net (code "115") (name "Net-(U5-HB)") (class "Default")
      (node (ref "C85") (pin "2") (pinfunction "2_2") (pintype "passive"))
      (node (ref "D5") (pin "1") (pinfunction "1_1") (pintype "passive"))
      (node (ref "U5") (pin "18") (pinfunction "HB_18") (pintype "passive"))
    )
    (net (code "116") (name "Net-(U5-RAMP)") (class "Default")
      (node (ref "C80") (pin "1") (pinfunction "1_1") (pintype "passive"))
      (node (ref "U5") (pin "5") (pinfunction "RAMP_5") (pintype "input"))
    )
    (net (code "117") (name "Net-(U5-RT{slash}SYNC)") (class "Default")
      (node (ref "R55") (pin "1") (pinfunction "1_1") (pintype "passive"))
      (node (ref "U5") (pin "3") (pinfunction "RT/SYNC_3") (pintype "input"))
    )
    (net (code "118") (name "Net-(U5-SS)") (class "Default")
      (node (ref "C81") (pin "2") (pinfunction "2_2") (pintype "passive"))
      (node (ref "U5") (pin "7") (pinfunction "SS_7") (pintype "input"))
    )
    (net (code "119") (name "Net-(U5-ULVO)") (class "Default")
      (node (ref "R53") (pin "2") (pinfunction "2_2") (pintype "passive"))
      (node (ref "R54") (pin "2") (pinfunction "2_2") (pintype "passive"))
      (node (ref "U5") (pin "2") (pinfunction "ULVO_2") (pintype "input"))
    )
    (net (code "120") (name "Net-(U5-VCC)") (class "Default")
      (node (ref "C84") (pin "2") (pinfunction "2_2") (pintype "passive"))
      (node (ref "D5") (pin "2") (pinfunction "2_2") (pintype "passive"))
      (node (ref "U5") (pin "16") (pinfunction "VCC_16") (pintype "power_in"))
    )
    (net (code "121") (name "Net-(U5-VOUT)") (class "Default")
      (node (ref "3.3V_F") (pin "1") (pinfunction "1_1") (pintype "passive"))
      (node (ref "C86") (pin "1") (pinfunction "1_1") (pintype "passive"))
      (node (ref "L1_5") (pin "2") (pinfunction "2_2") (pintype "passive"))
      (node (ref "R58") (pin "2") (pinfunction "2_2") (pintype "passive"))
      (node (ref "U5") (pin "10") (pinfunction "VOUT_10") (pintype "input"))
    )
    (net (code "122") (name "Net-(U5.5-IN+)") (class "Default")
      (node (ref "R51") (pin "1") (pinfunction "1_1") (pintype "passive"))
      (node (ref "R52") (pin "2") (pinfunction "2_2") (pintype "passive"))
      (node (ref "U5.5") (pin "3") (pinfunction "IN+_3") (pintype "input"))
    )
    (net (code "123") (name "Net-(UA-B)") (class "Default")
      (node (ref "RF_LINK") (pin "1") (pinfunction "1_1") (pintype "passive"))
      (node (ref "UA") (pin "2") (pinfunction "B_2") (pintype "input"))
    )
    (net (code "124") (name "Net-(UAS_1-IN+)") (class "Default")
      (node (ref "RAS") (pin "2") (pinfunction "2_2") (pintype "passive"))
      (node (ref "RAS2") (pin "2") (pinfunction "2_2") (pintype "passive"))
      (node (ref "UAS_1") (pin "3") (pinfunction "IN+_3") (pintype "input"))
    )
    (net (code "125") (name "Net-(UAS_2-IN+)") (class "Default")
      (node (ref "RAS3") (pin "2") (pinfunction "2_2") (pintype "passive"))
      (node (ref "RAS4") (pin "2") (pinfunction "2_2") (pintype "passive"))
      (node (ref "UAS_2") (pin "3") (pinfunction "IN+_3") (pintype "input"))
    )
    (net (code "126") (name "Net-(UMD_1-IN+)") (class "Default")
      (node (ref "RM") (pin "2") (pinfunction "2_2") (pintype "passive"))
      (node (ref "RM2") (pin "2") (pinfunction "2_2") (pintype "passive"))
      (node (ref "UMD_1") (pin "3") (pinfunction "IN+_3") (pintype "input"))
    )
    (net (code "127") (name "Net-(UMD_2-IN+)") (class "Default")
      (node (ref "RM3") (pin "2") (pinfunction "2_2") (pintype "passive"))
      (node (ref "RM4") (pin "2") (pinfunction "2_2") (pintype "passive"))
      (node (ref "UMD_2") (pin "3") (pinfunction "IN+_3") (pintype "input"))
    )
    (net (code "128") (name "Net-(Ufans-IN+)") (class "Default")
      (node (ref "R40") (pin "2") (pinfunction "2_2") (pintype "passive"))
      (node (ref "R41") (pin "1") (pinfunction "1_1") (pintype "passive"))
      (node (ref "Ufans") (pin "3") (pinfunction "IN+_3") (pintype "input"))
    )
    (net (code "129") (name "Net-(Umcm-IN+)") (class "Default")
      (node (ref "R20") (pin "2") (pinfunction "2_2") (pintype "passive"))
      (node (ref "R21") (pin "1") (pinfunction "1_1") (pintype "passive"))
      (node (ref "Umcm") (pin "3") (pinfunction "IN+_3") (pintype "input"))
    )
    (net (code "130") (name "Net-(Uservo-IN+)") (class "Default")
      (node (ref "R11") (pin "1") (pinfunction "1_1") (pintype "passive"))
      (node (ref "R9") (pin "2") (pinfunction "2_2") (pintype "passive"))
      (node (ref "Uservo") (pin "3") (pinfunction "IN+_3") (pintype "input"))
    )
    (net (code "131") (name "Net-(servo_L-A)") (class "Default")
      (node (ref "RL5") (pin "2") (pinfunction "2_2") (pintype "passive"))
      (node (ref "servo_L") (pin "2") (pinfunction "A_2") (pintype "passive"))
    )
    (net (code "132") (name "System+") (class "Default")
      (node (ref "CR15") (pin "1") (pinfunction "1_1") (pintype "passive"))
      (node (ref "K1") (pin "1") (pinfunction "1_1") (pintype "passive"))
      (node (ref "K2") (pin "1") (pinfunction "1_1") (pintype "passive"))
      (node (ref "MP+") (pin "1") (pinfunction "1_1") (pintype "passive"))
    )
    (net (code "133") (name "unconnected-(MP1-Pad1)") (class "Default")
      (node (ref "MP1") (pin "1") (pinfunction "1_1") (pintype "passive"))
    )
    (net (code "134") (name "unconnected-(MP2-Pad1)") (class "Default")
      (node (ref "MP2") (pin "1") (pinfunction "1_1") (pintype "passive"))
    )
    (net (code "135") (name "unconnected-(MP3-Pad1)") (class "Default")
      (node (ref "MP3") (pin "1") (pinfunction "1_1") (pintype "passive"))
    )
    (net (code "136") (name "unconnected-(MP4-Pad1)") (class "Default")
      (node (ref "MP4") (pin "1") (pinfunction "1_1") (pintype "passive"))
    )
    (net (code "137") (name "unconnected-(R8-Pad1)") (class "Default")
      (node (ref "R8") (pin "1") (pinfunction "1_1") (pintype "passive"))
    )
  )
)
